# DL0WH_BiTuner_Ctrl_1V1.net
KiCad netlist of a schematic drawn in EAGLE
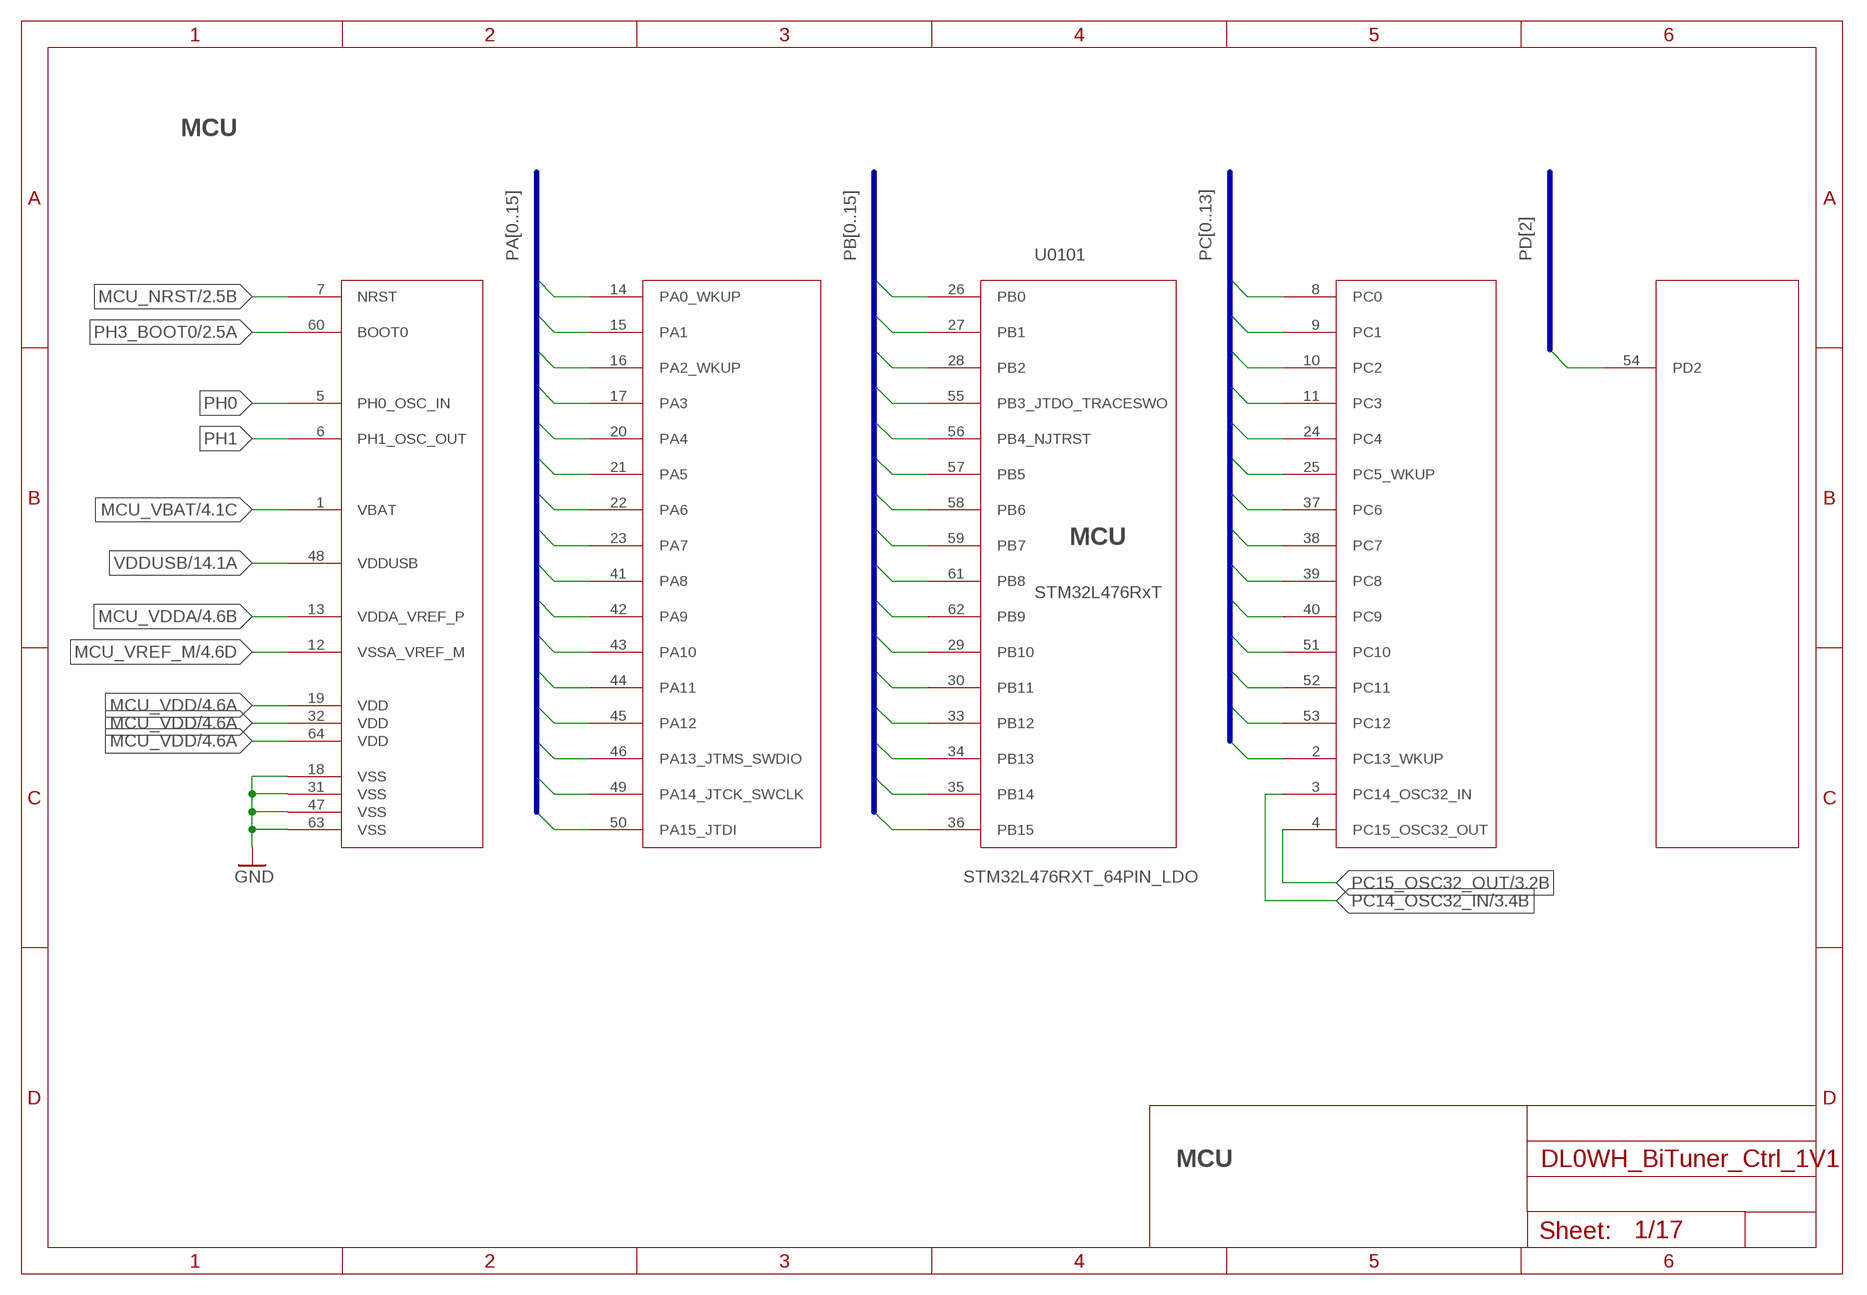
[diagram p0: schematic, sheet 1]
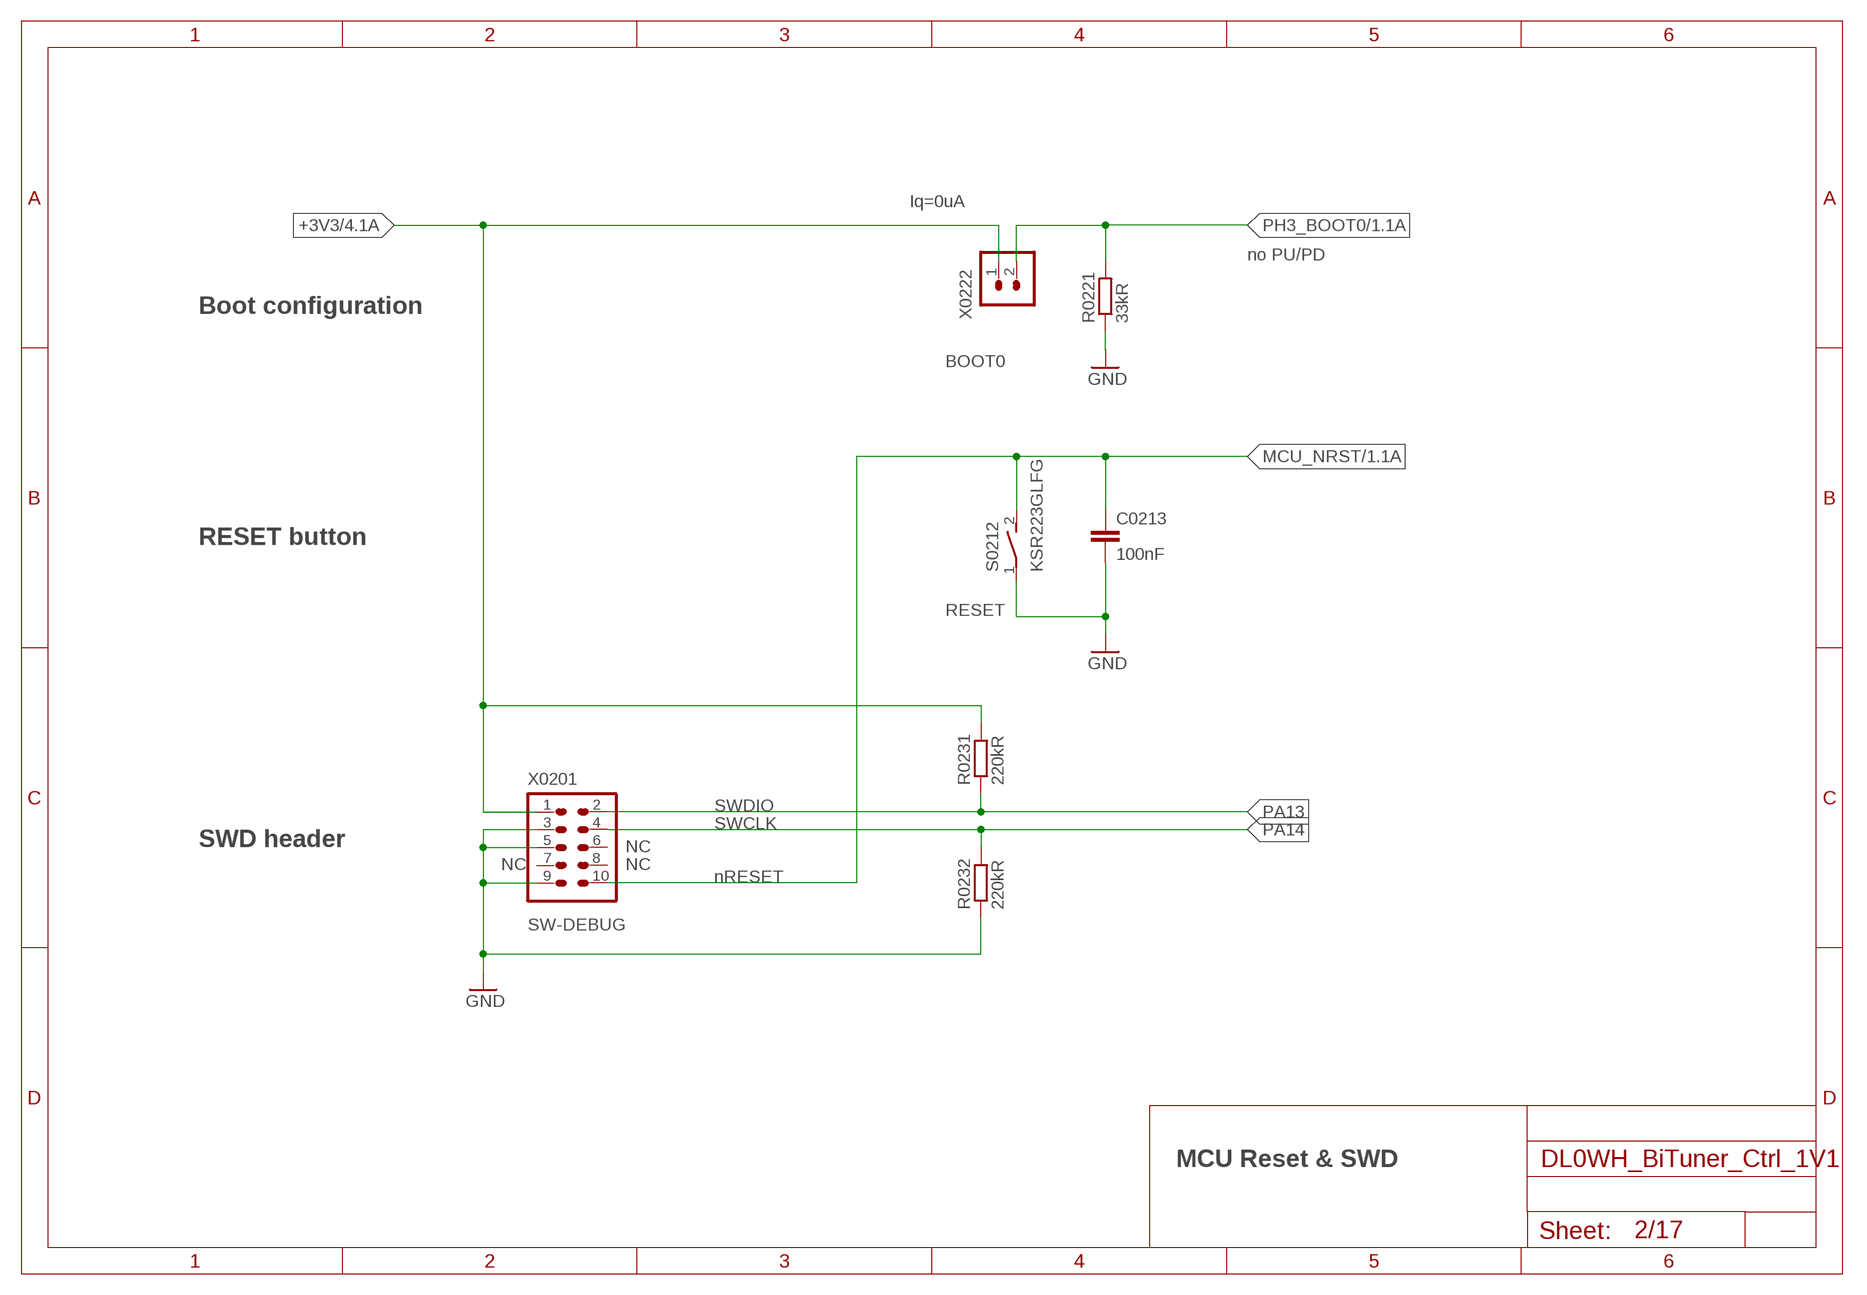
[diagram p1: schematic, sheet 2]
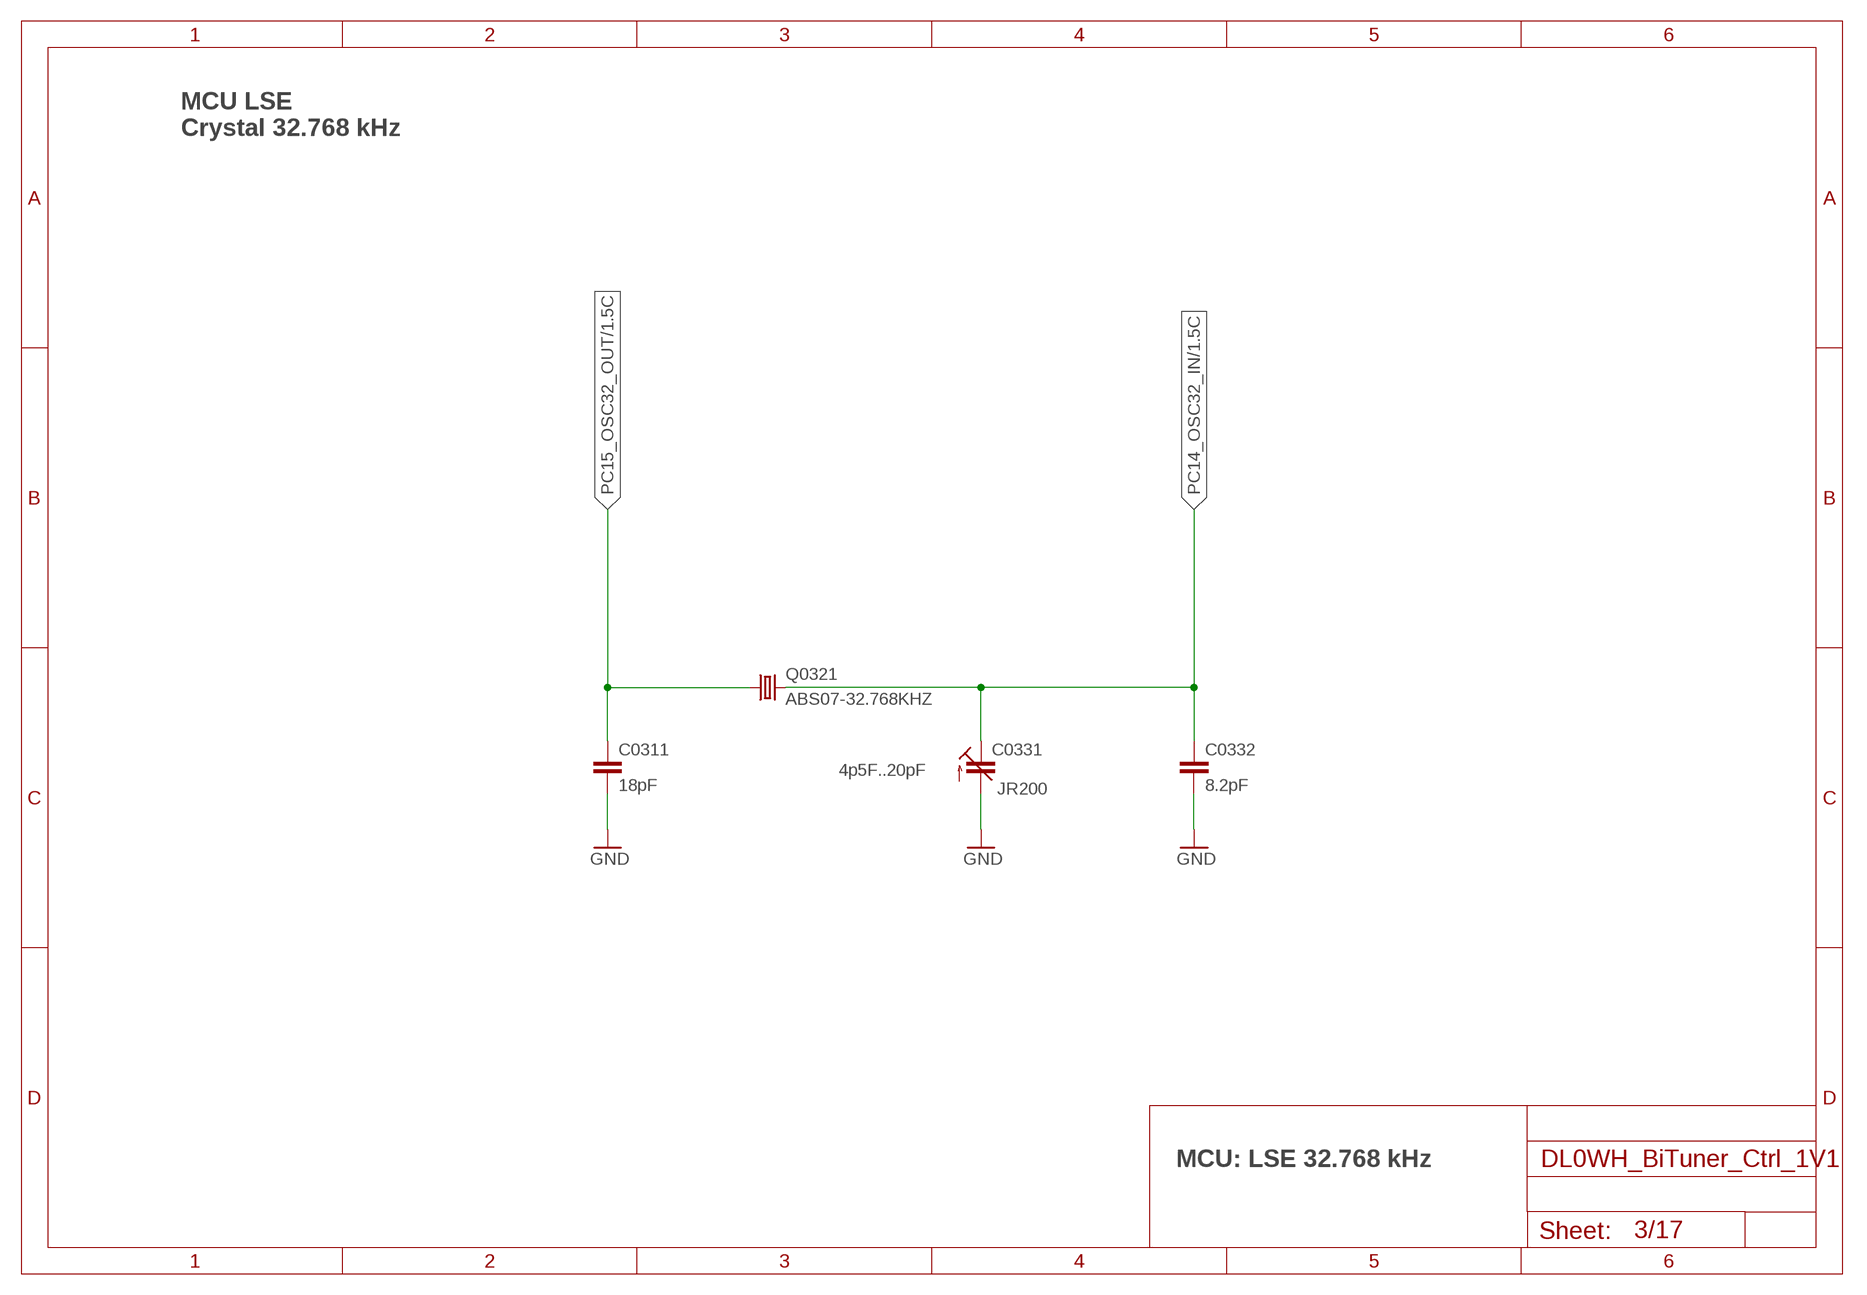
[diagram p2: schematic, sheet 3]
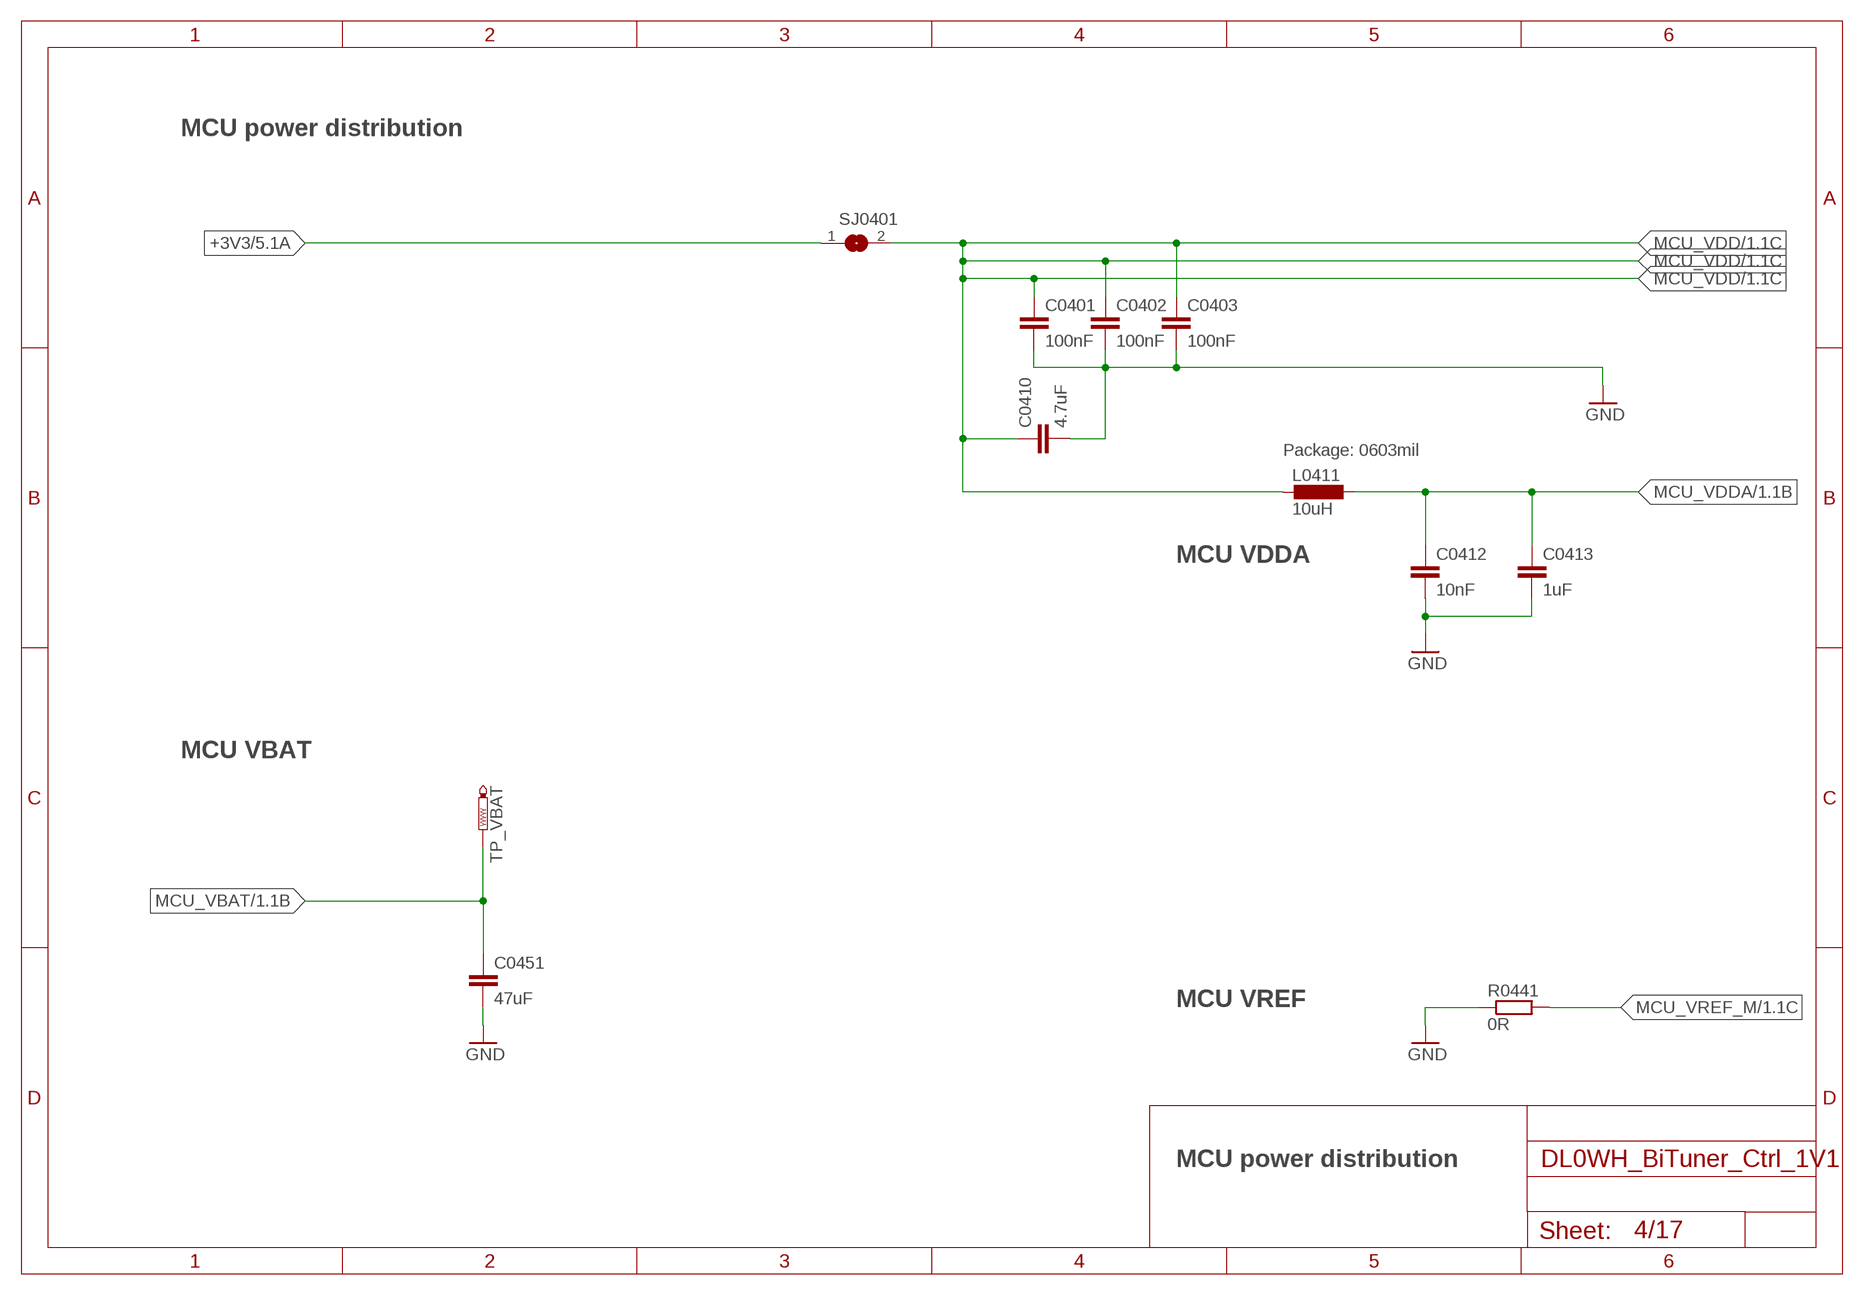
[diagram p3: schematic, sheet 4]
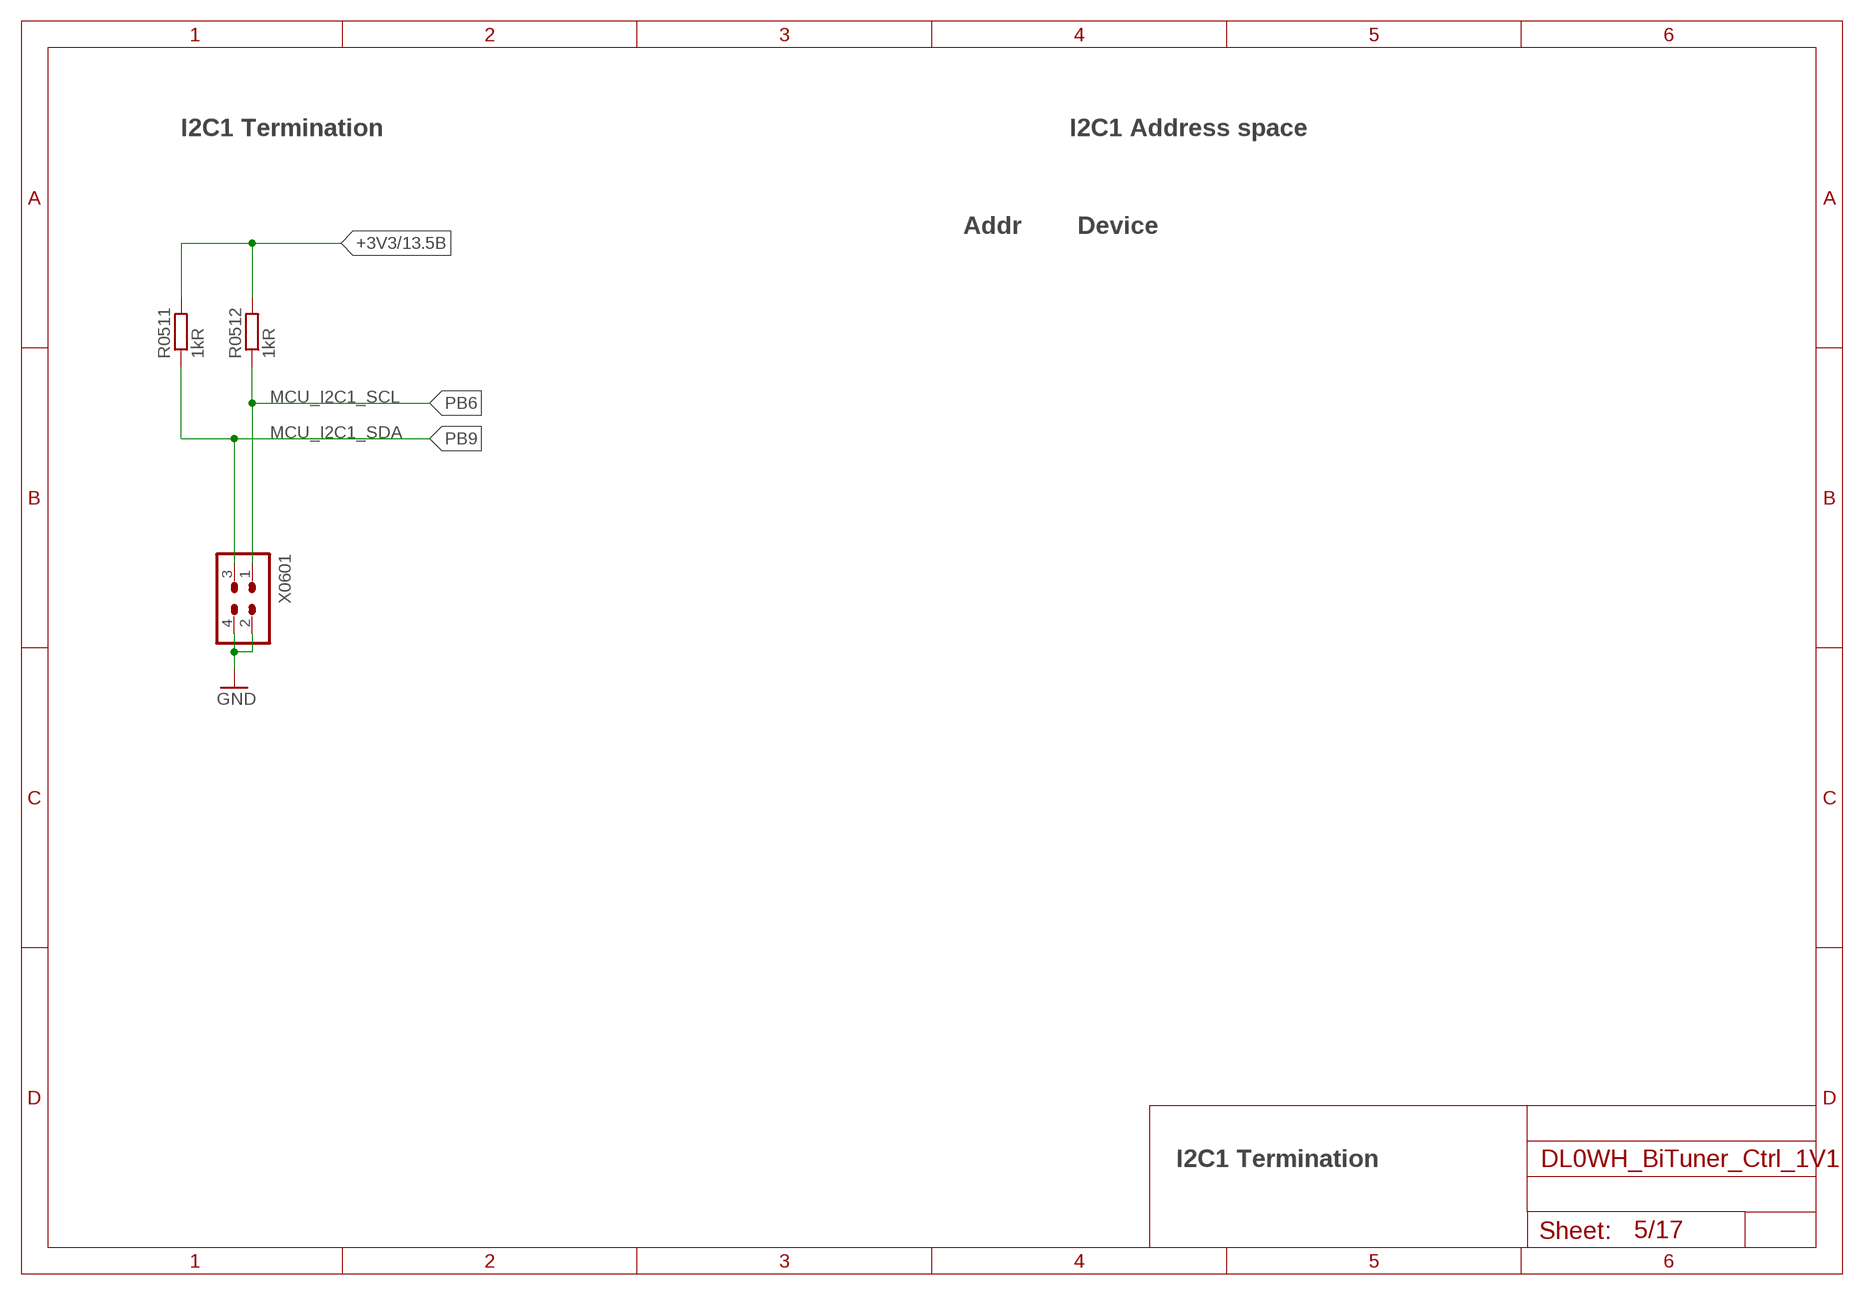
[diagram p4: schematic, sheet 5]
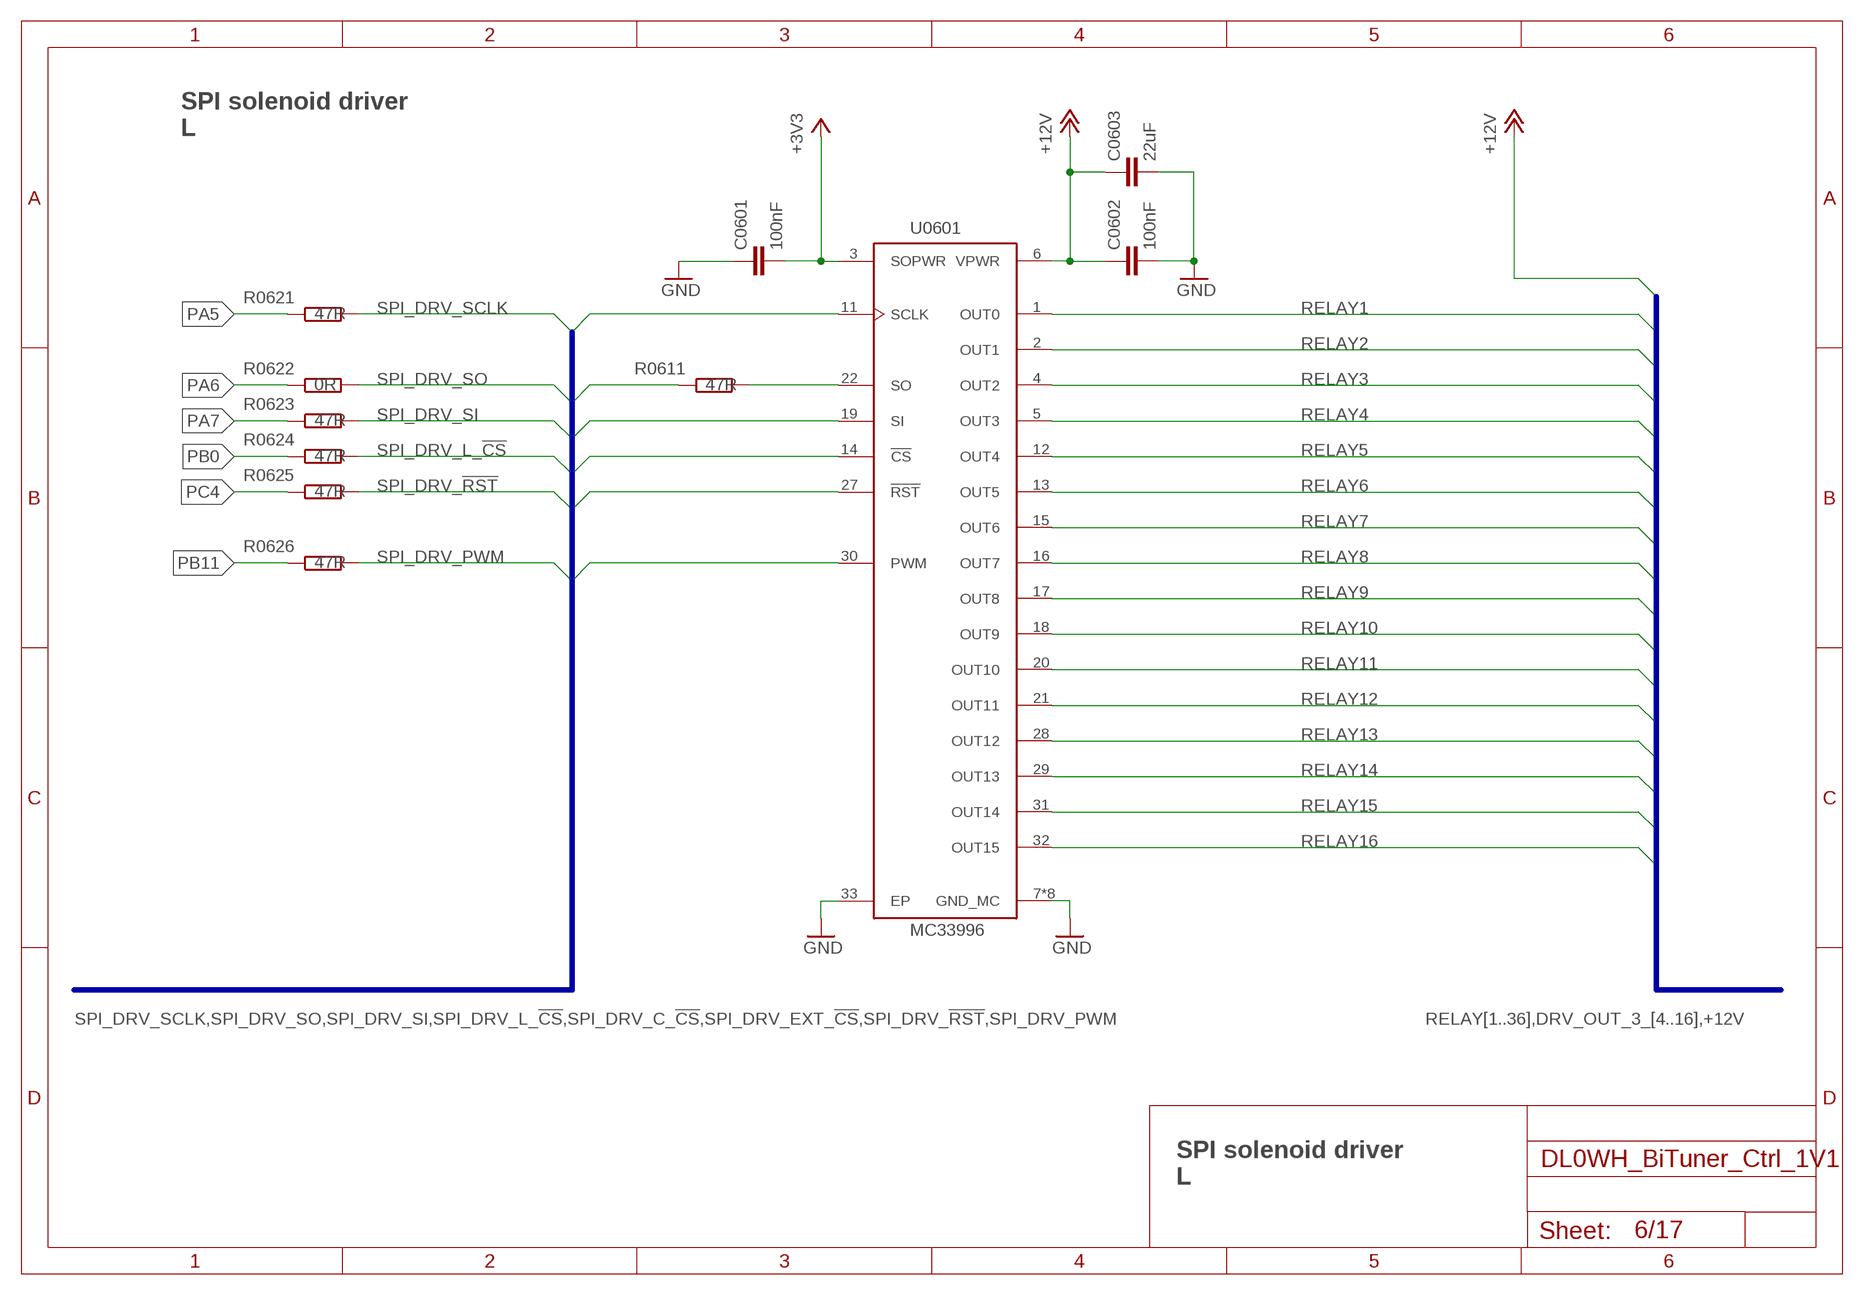
[diagram p5: schematic, sheet 6]
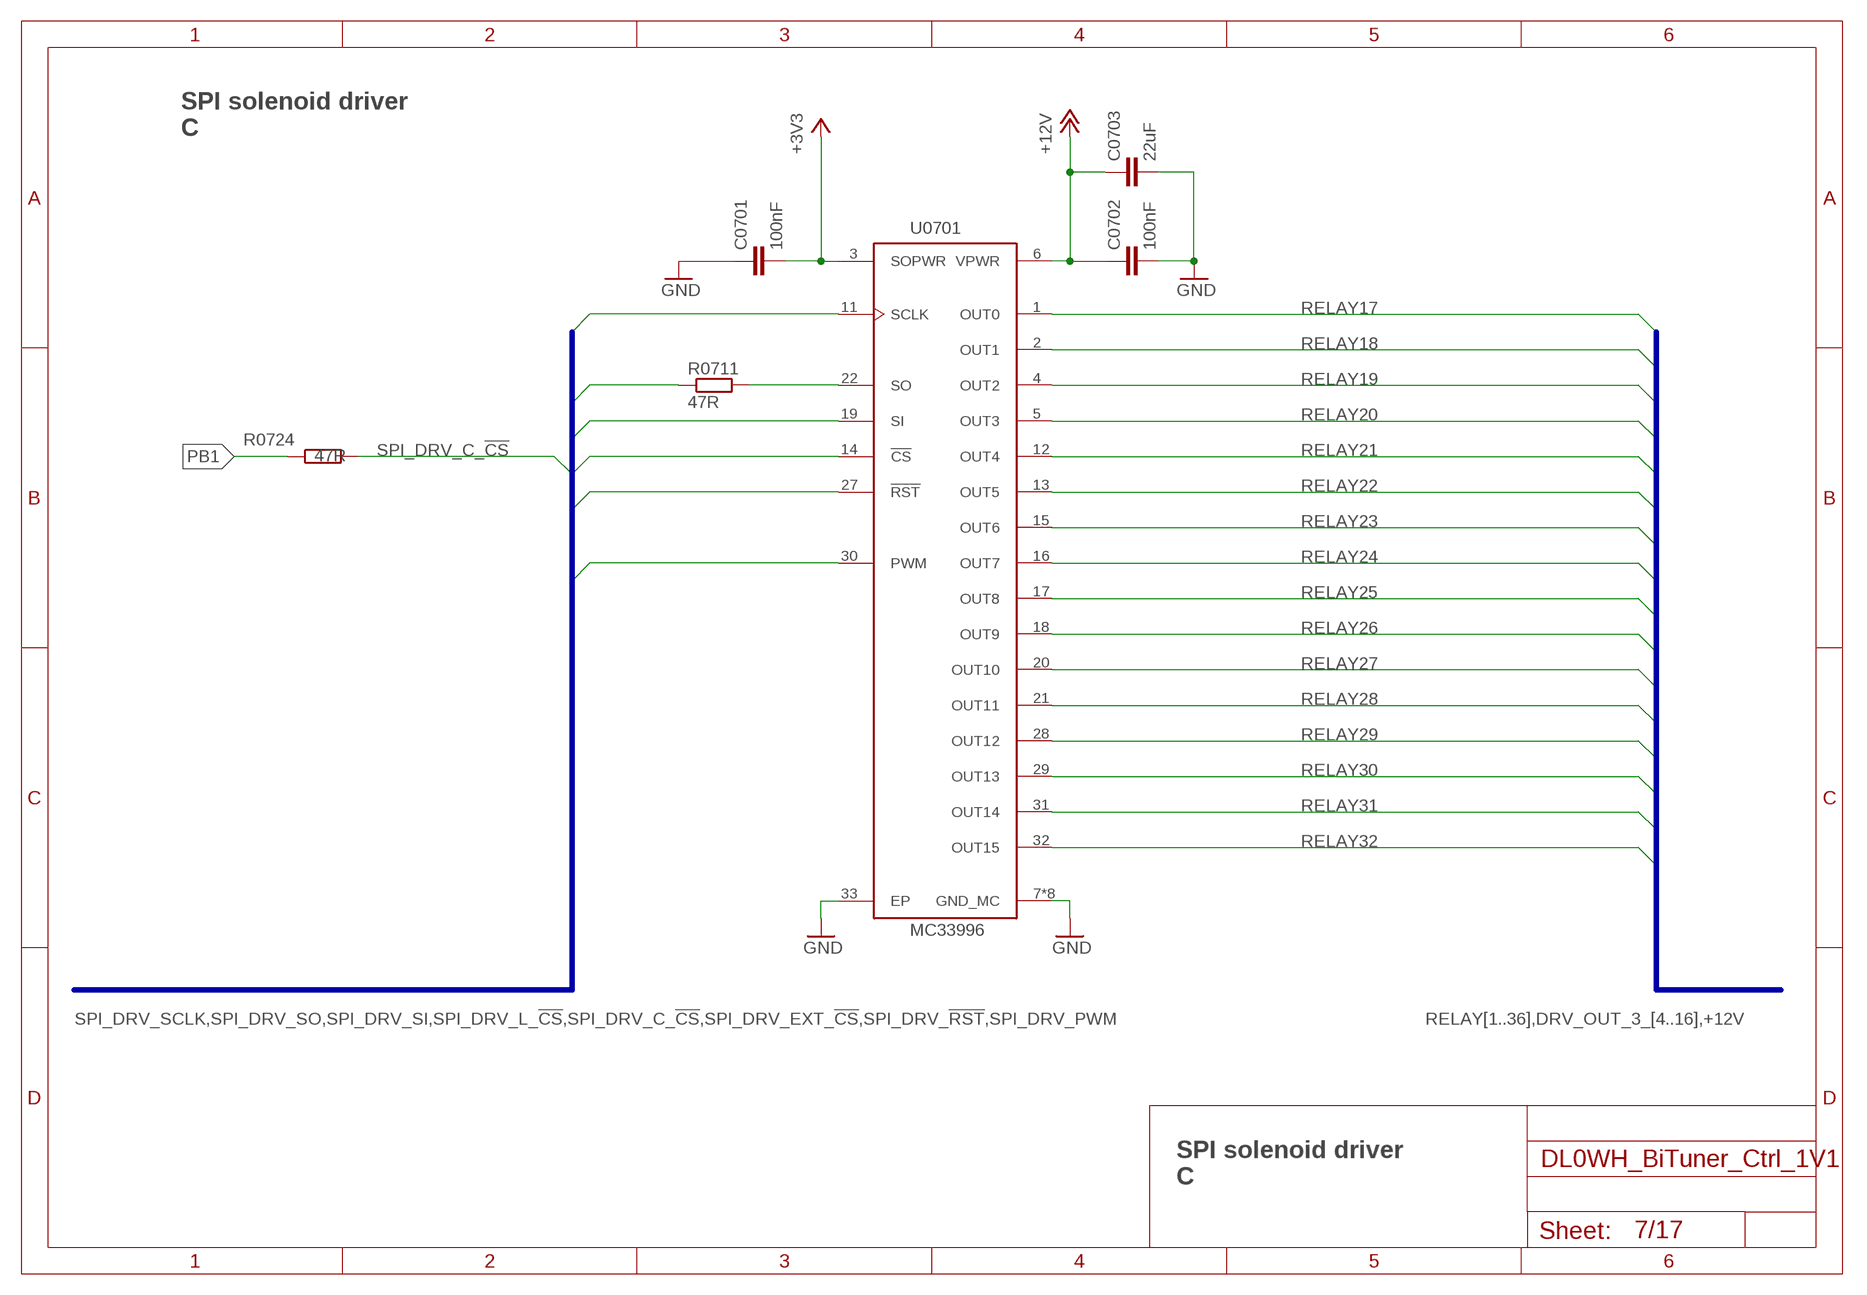
[diagram p6: schematic, sheet 7]
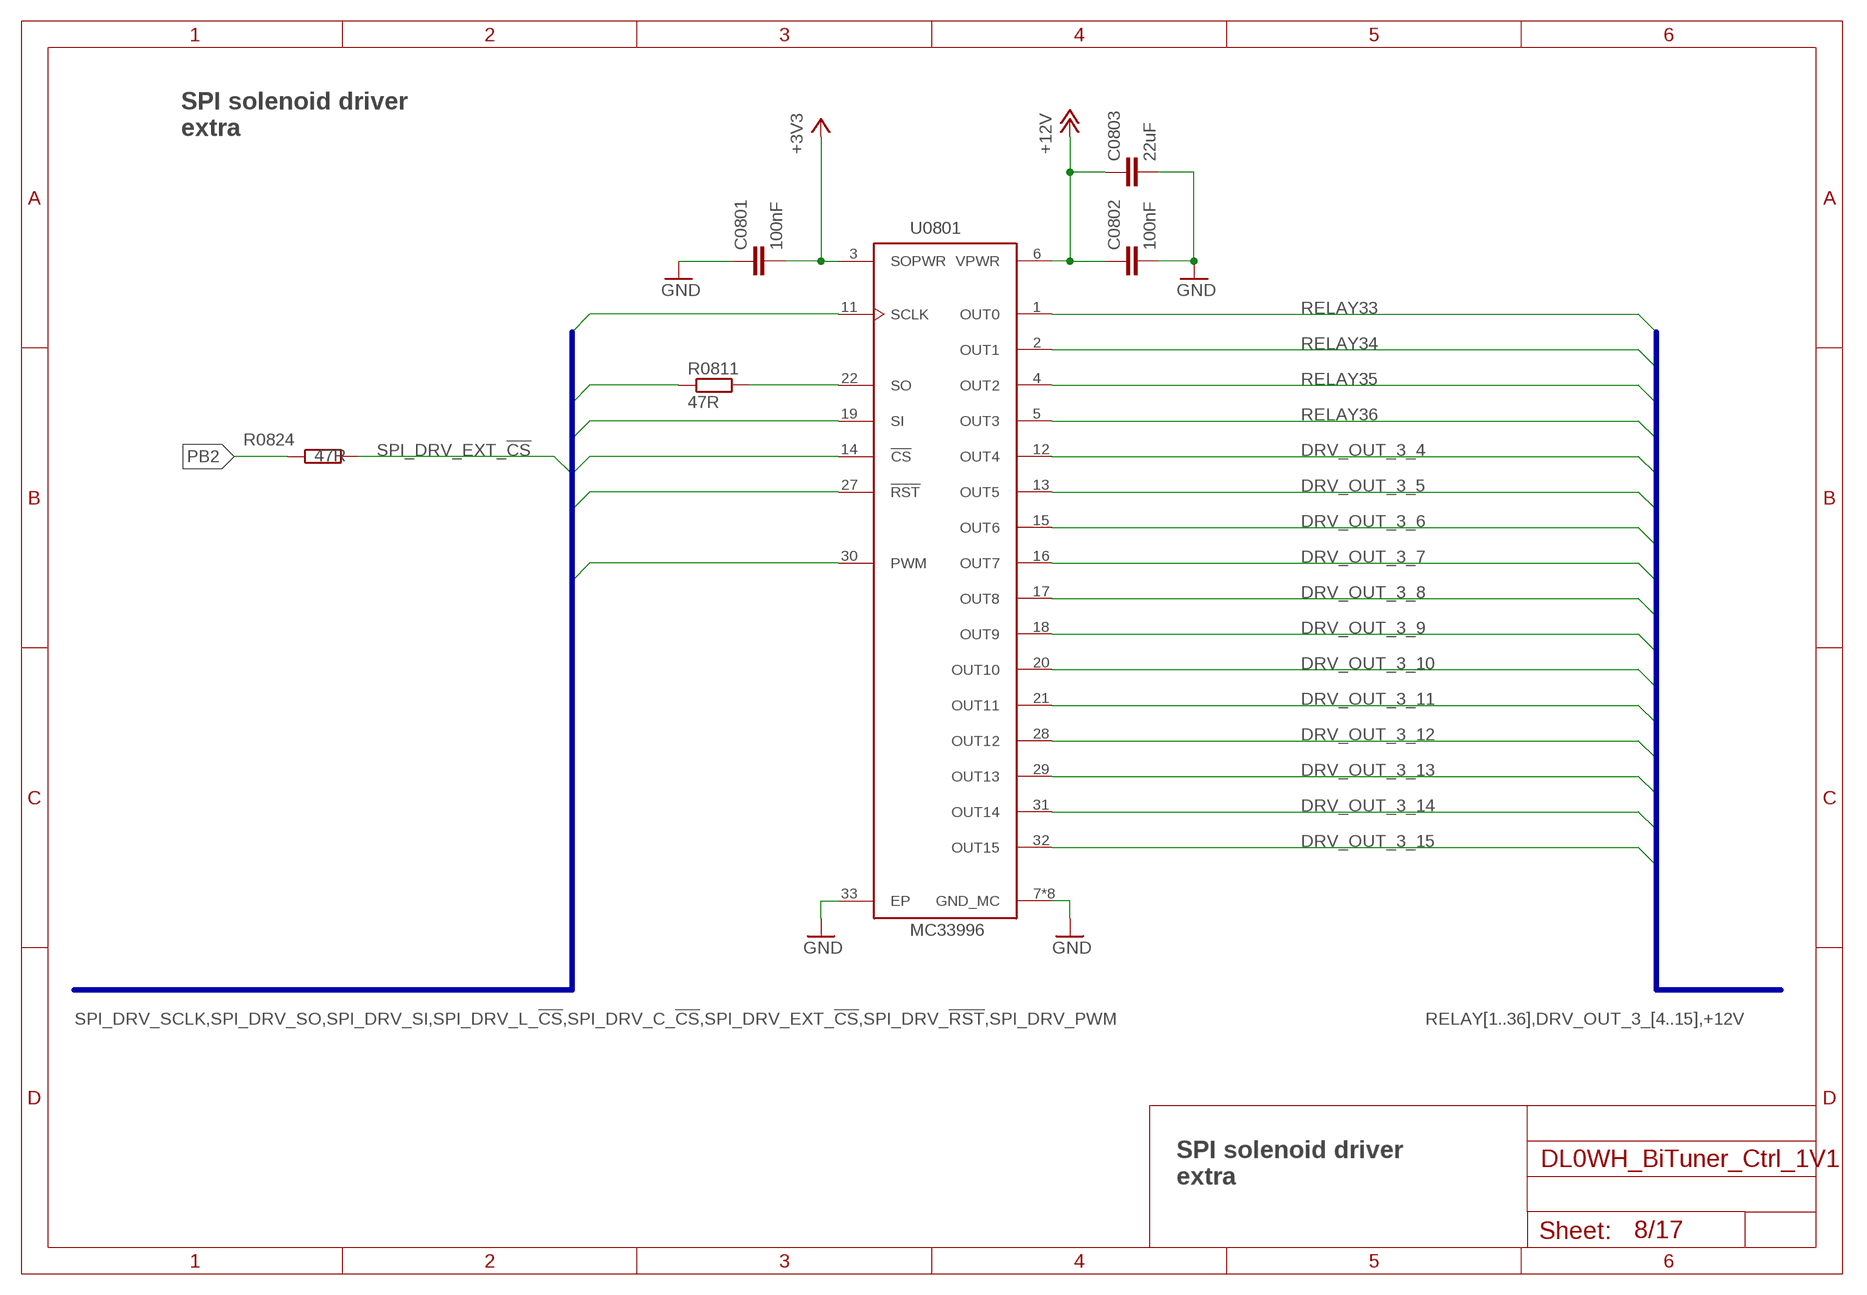
[diagram p7: schematic, sheet 8]
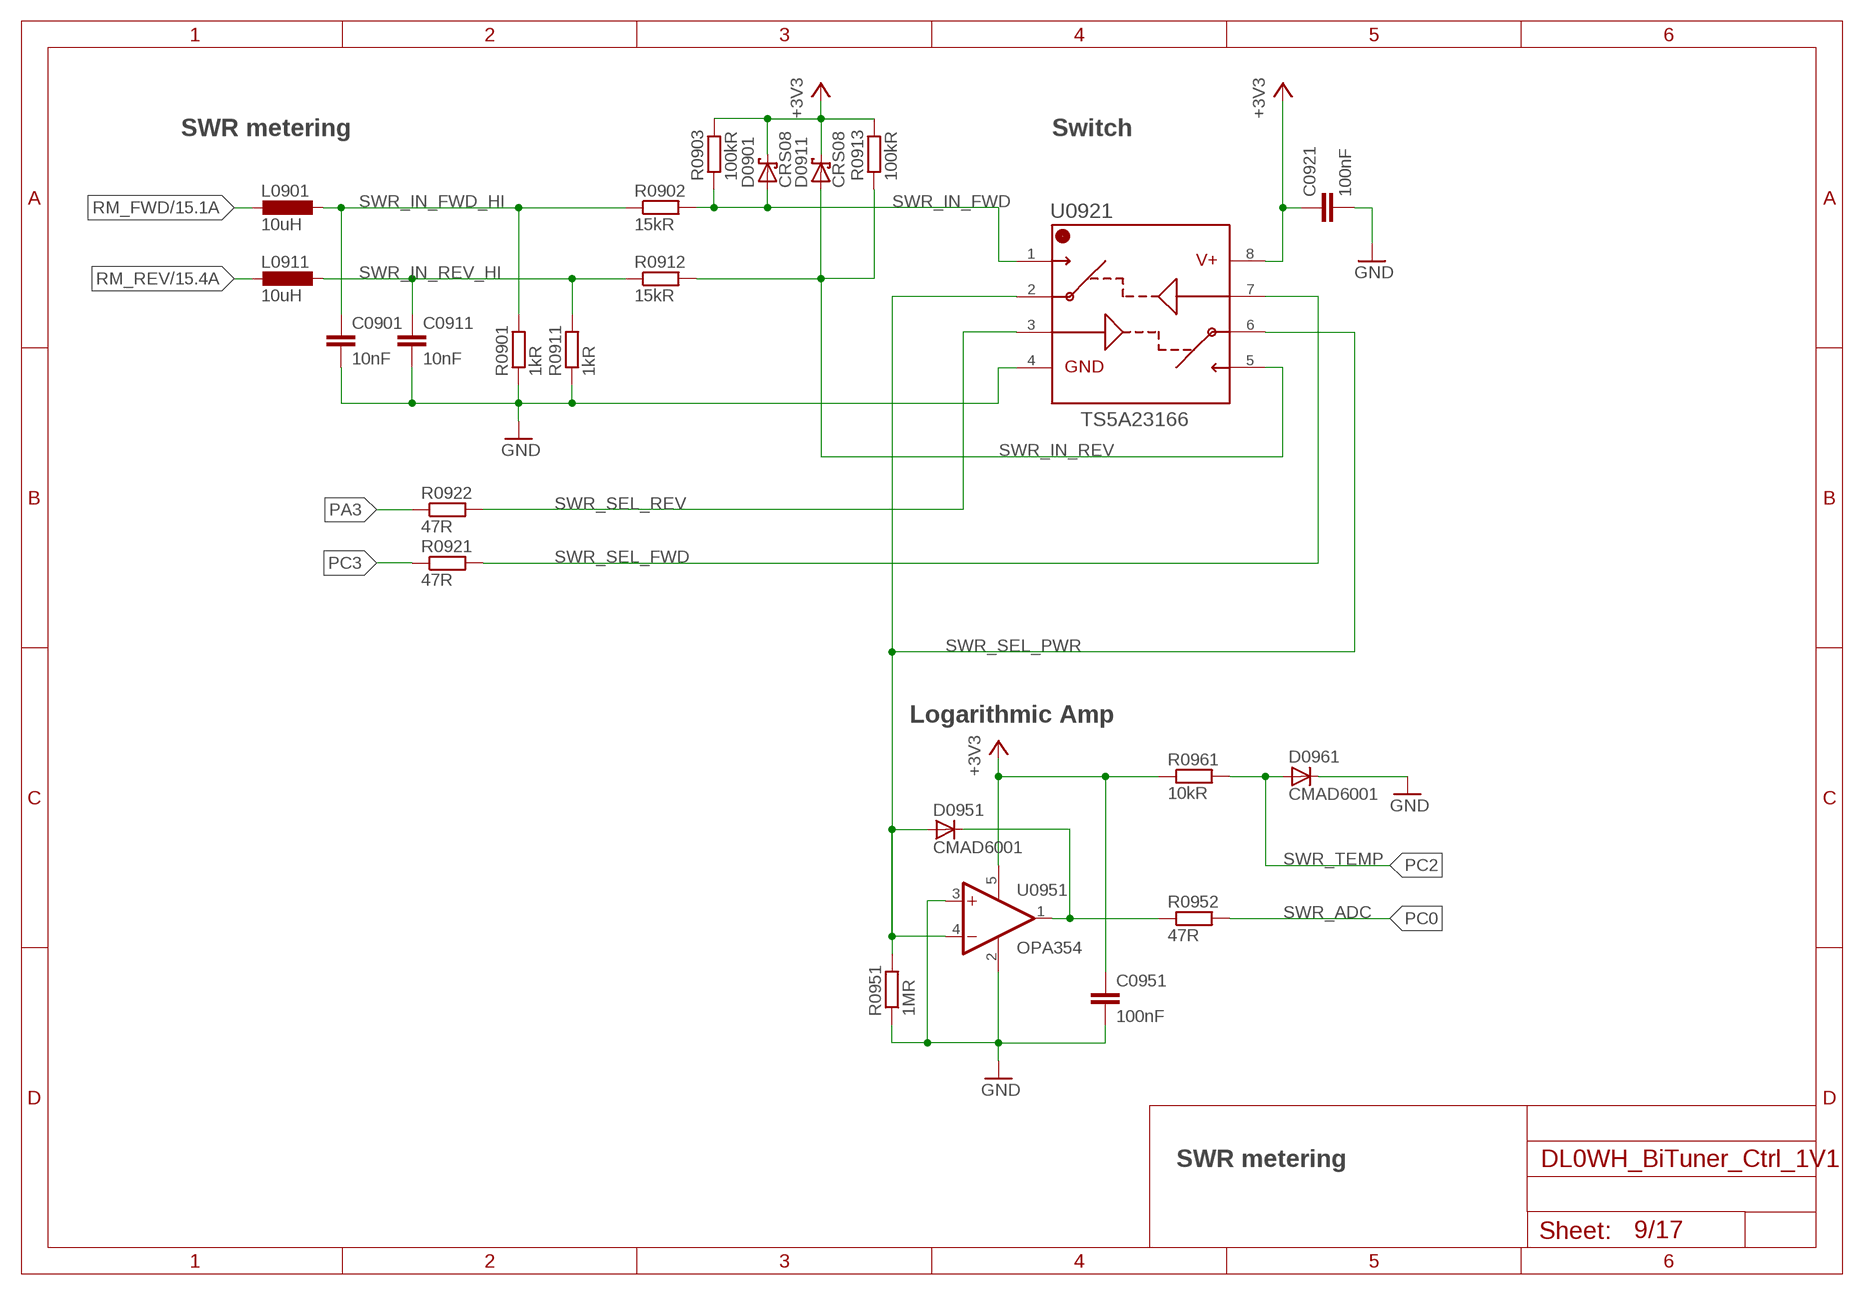
[diagram p8: schematic, sheet 9]
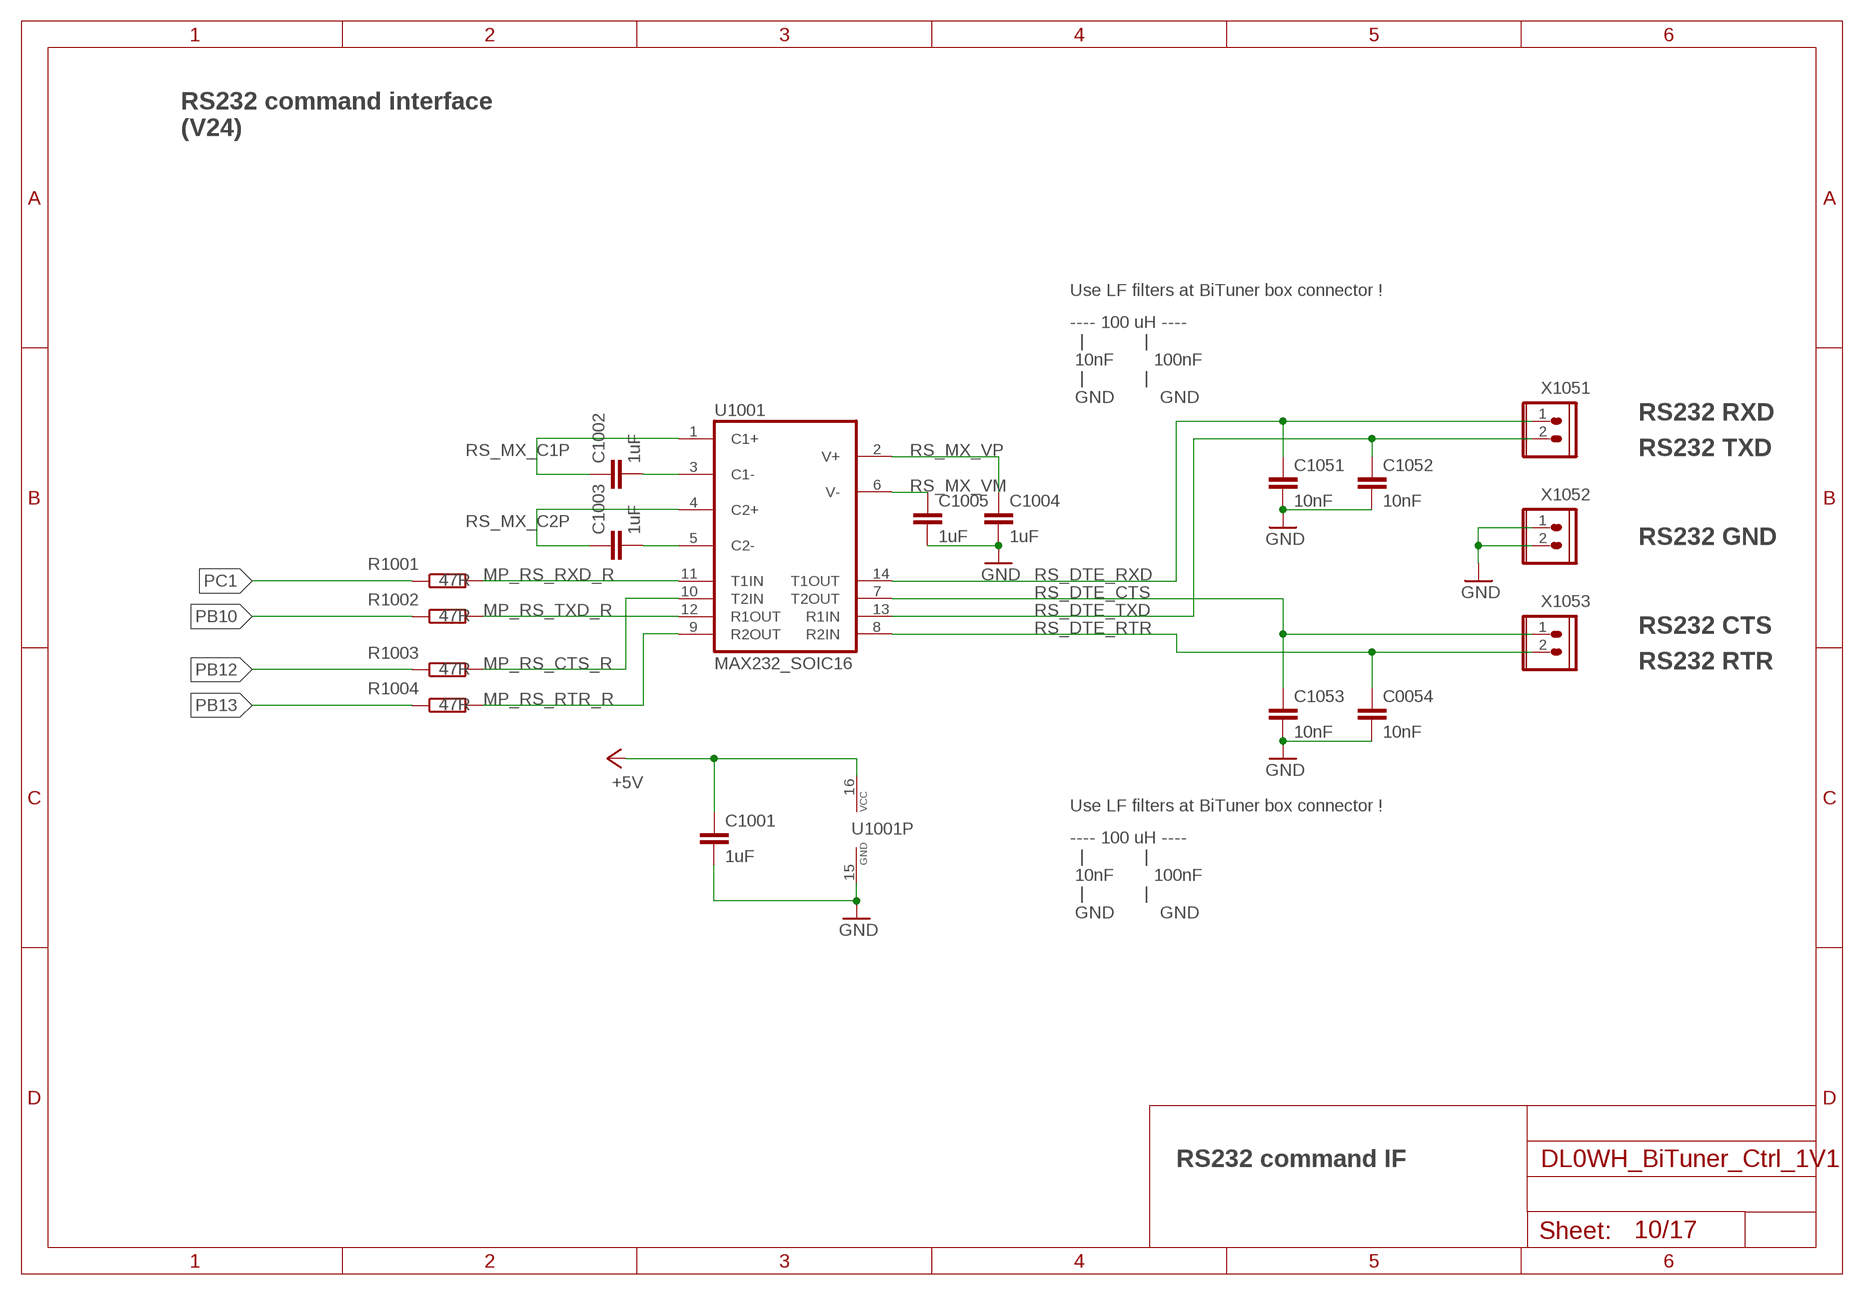
[diagram p9: schematic, sheet 10]
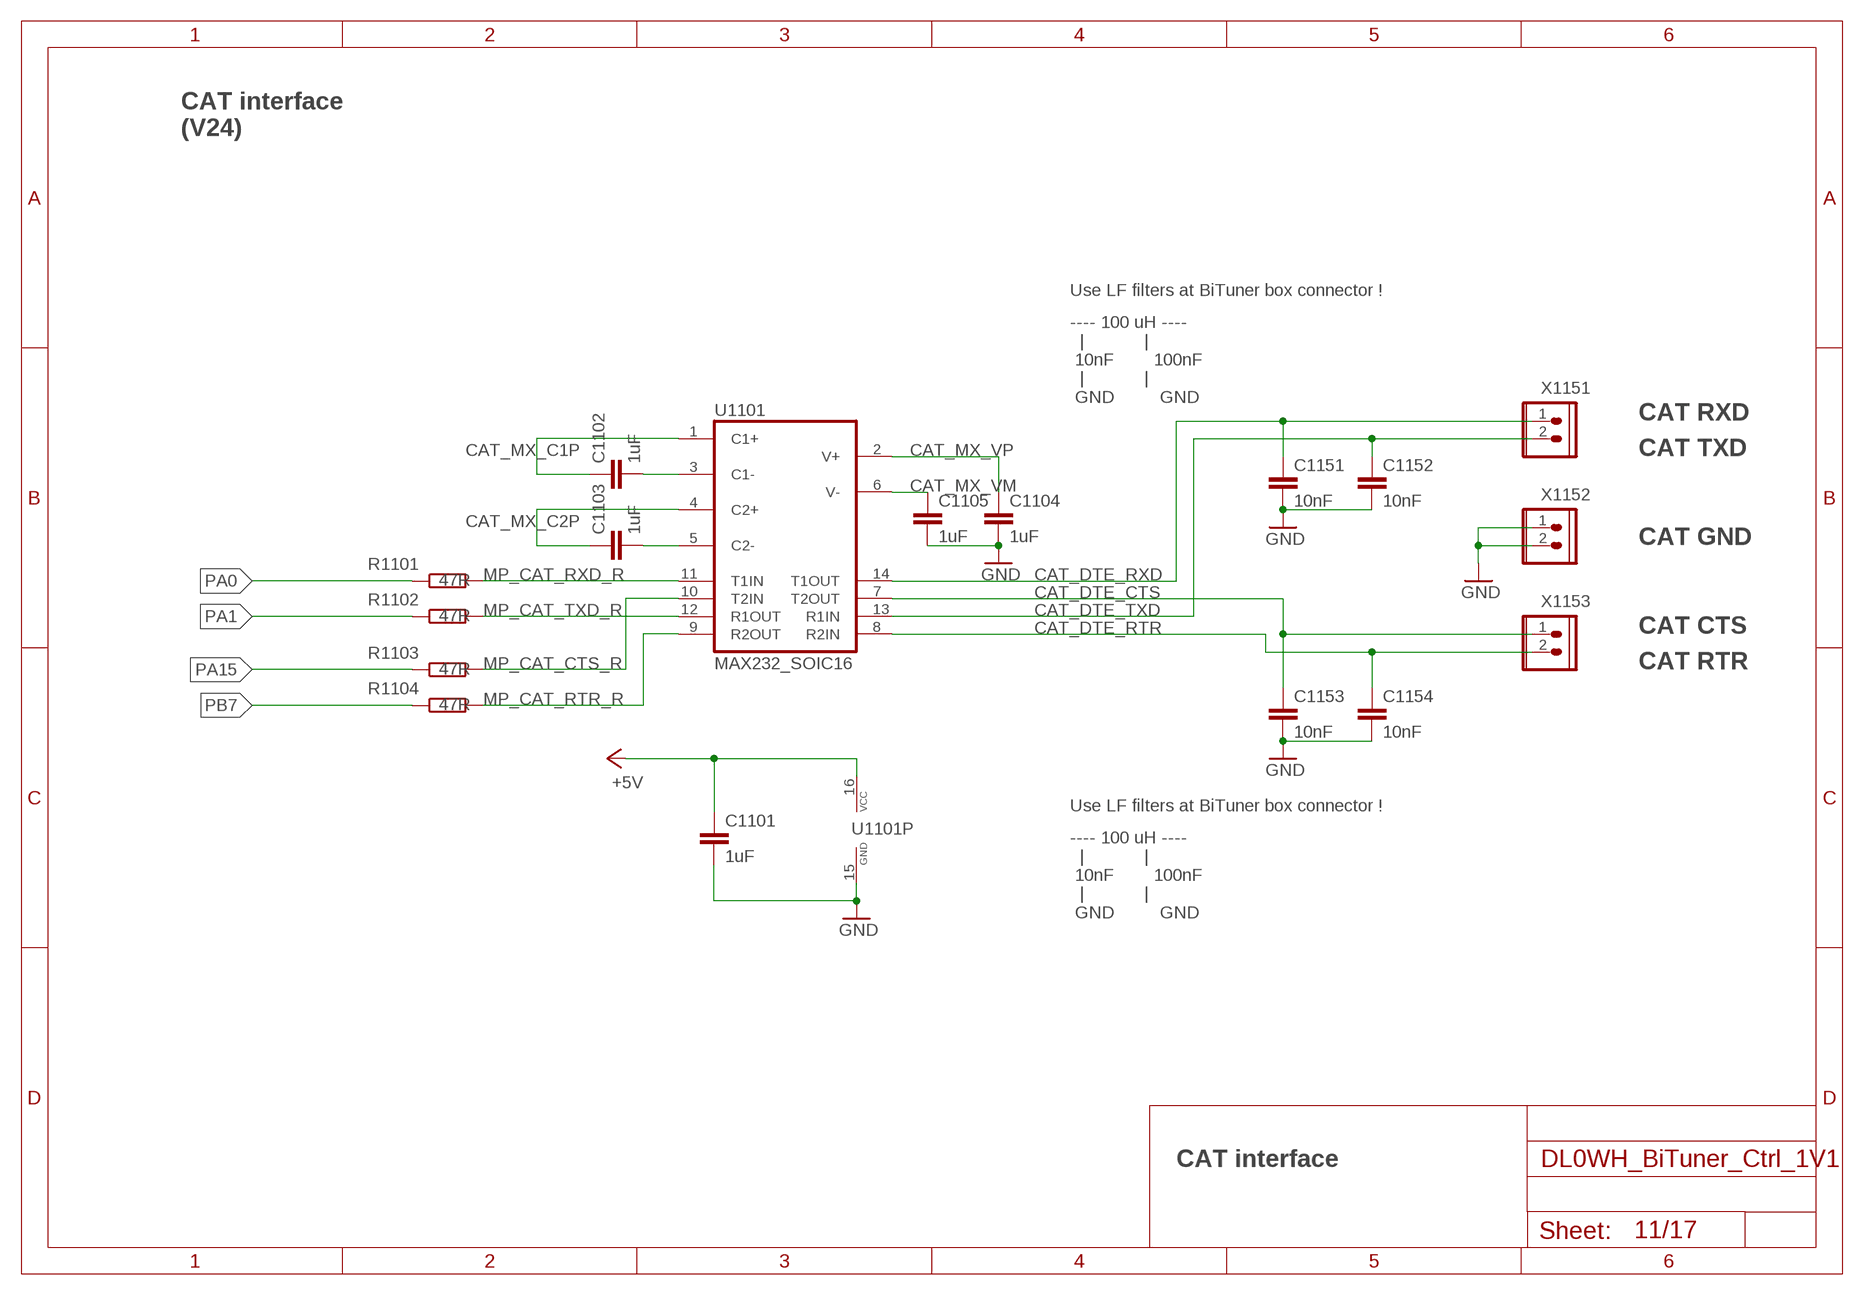
[diagram p10: schematic, sheet 11]
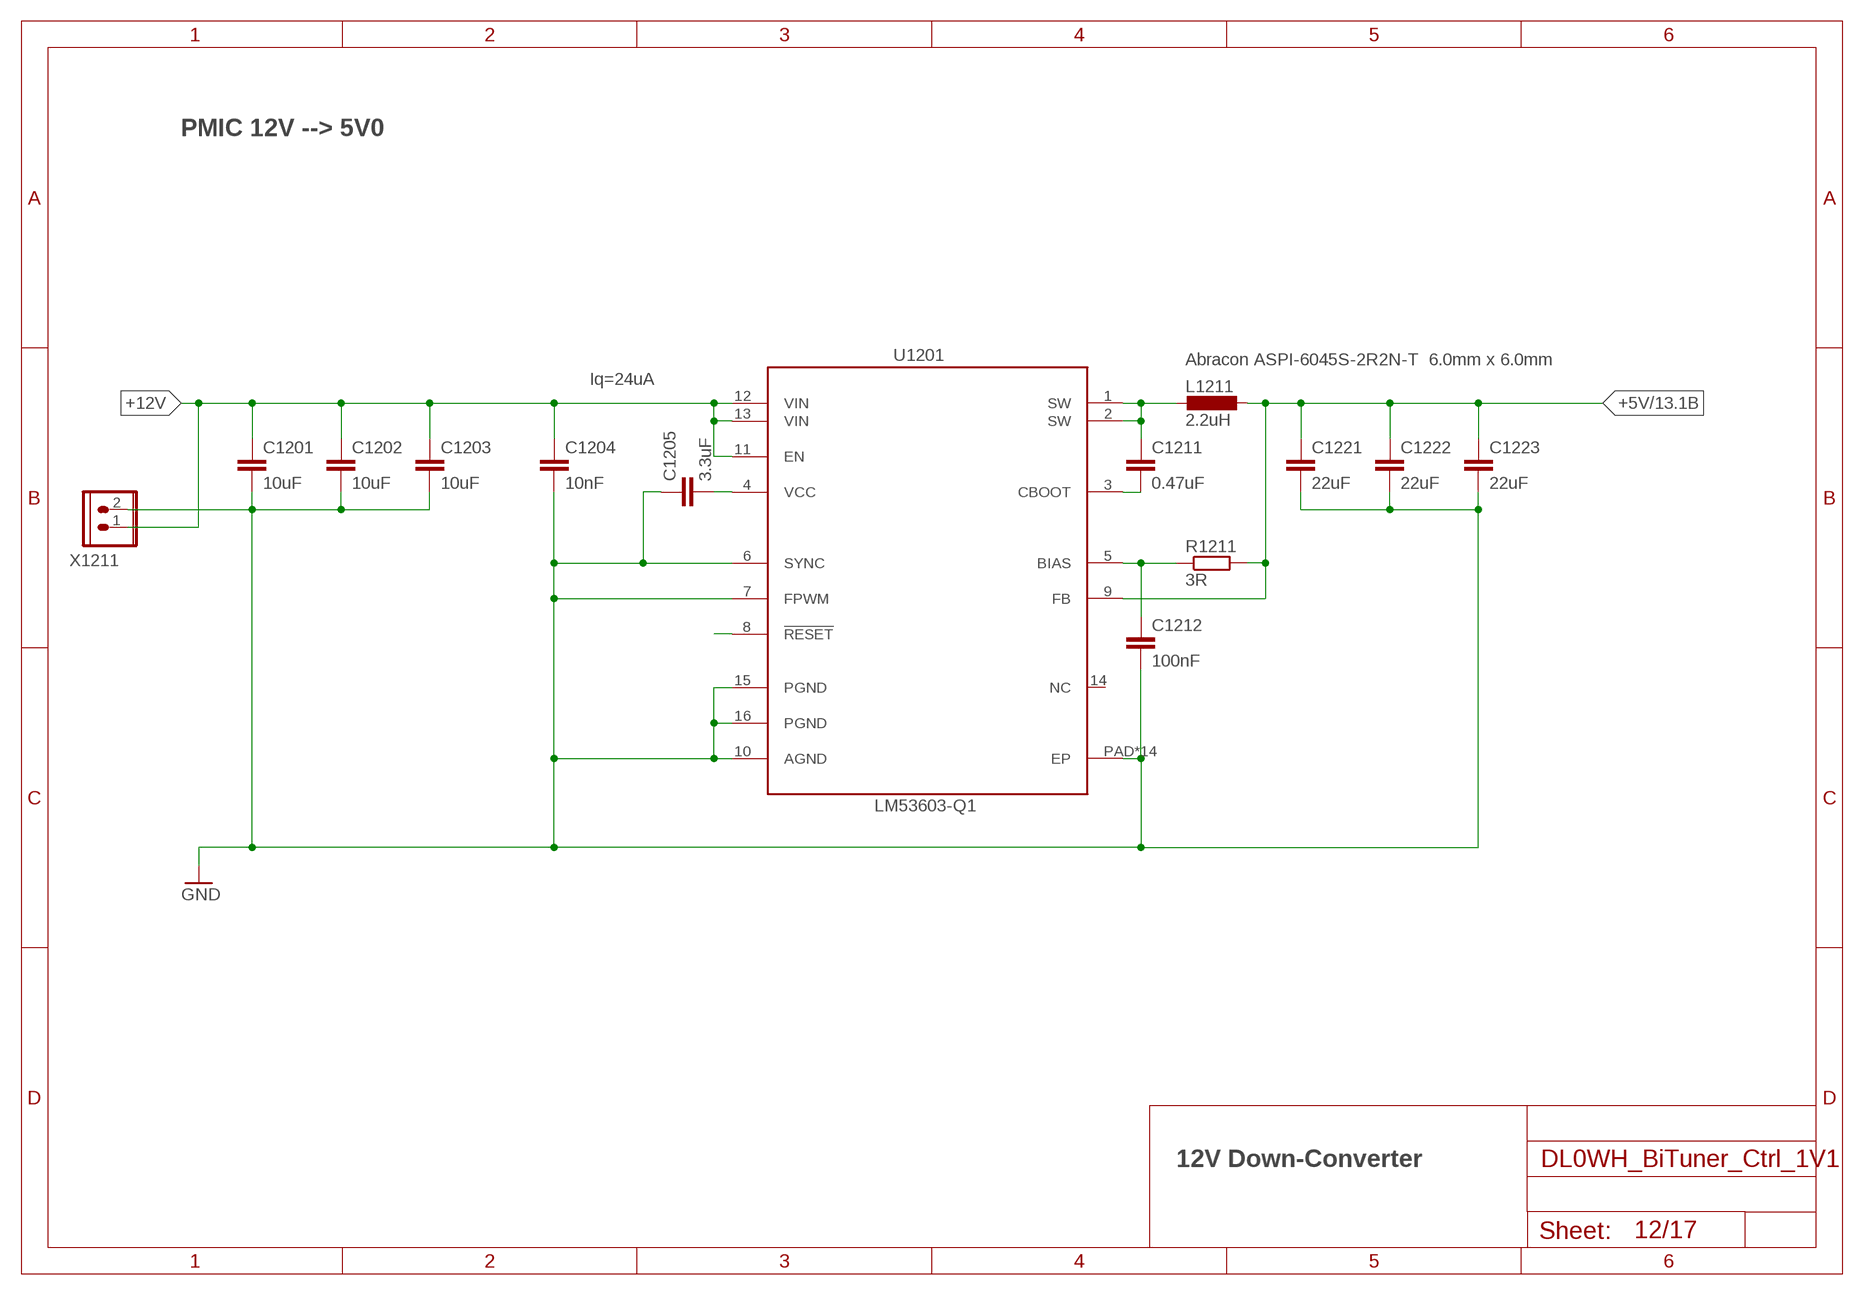
[diagram p11: schematic, sheet 12]
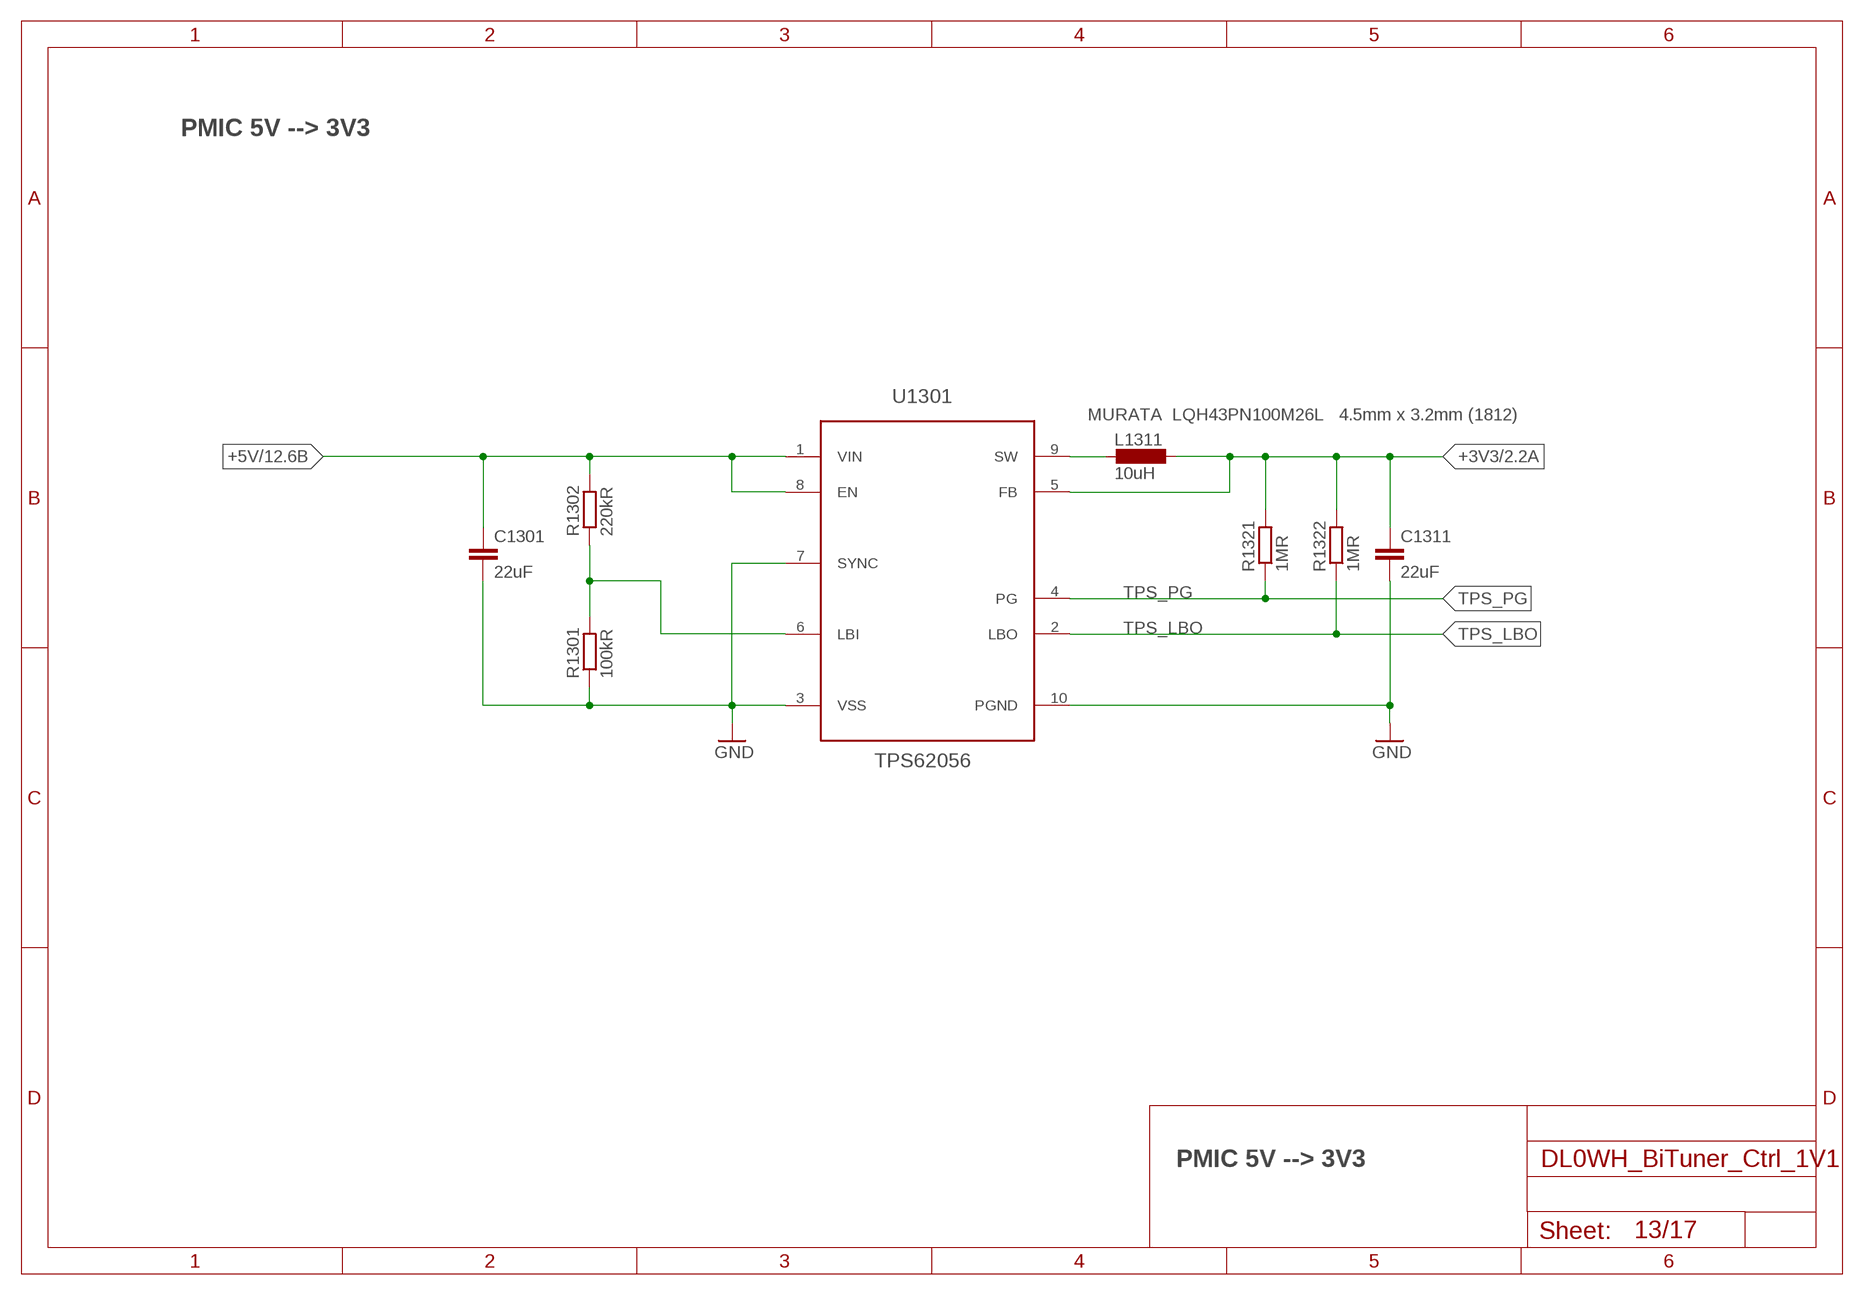
[diagram p12: schematic, sheet 13]
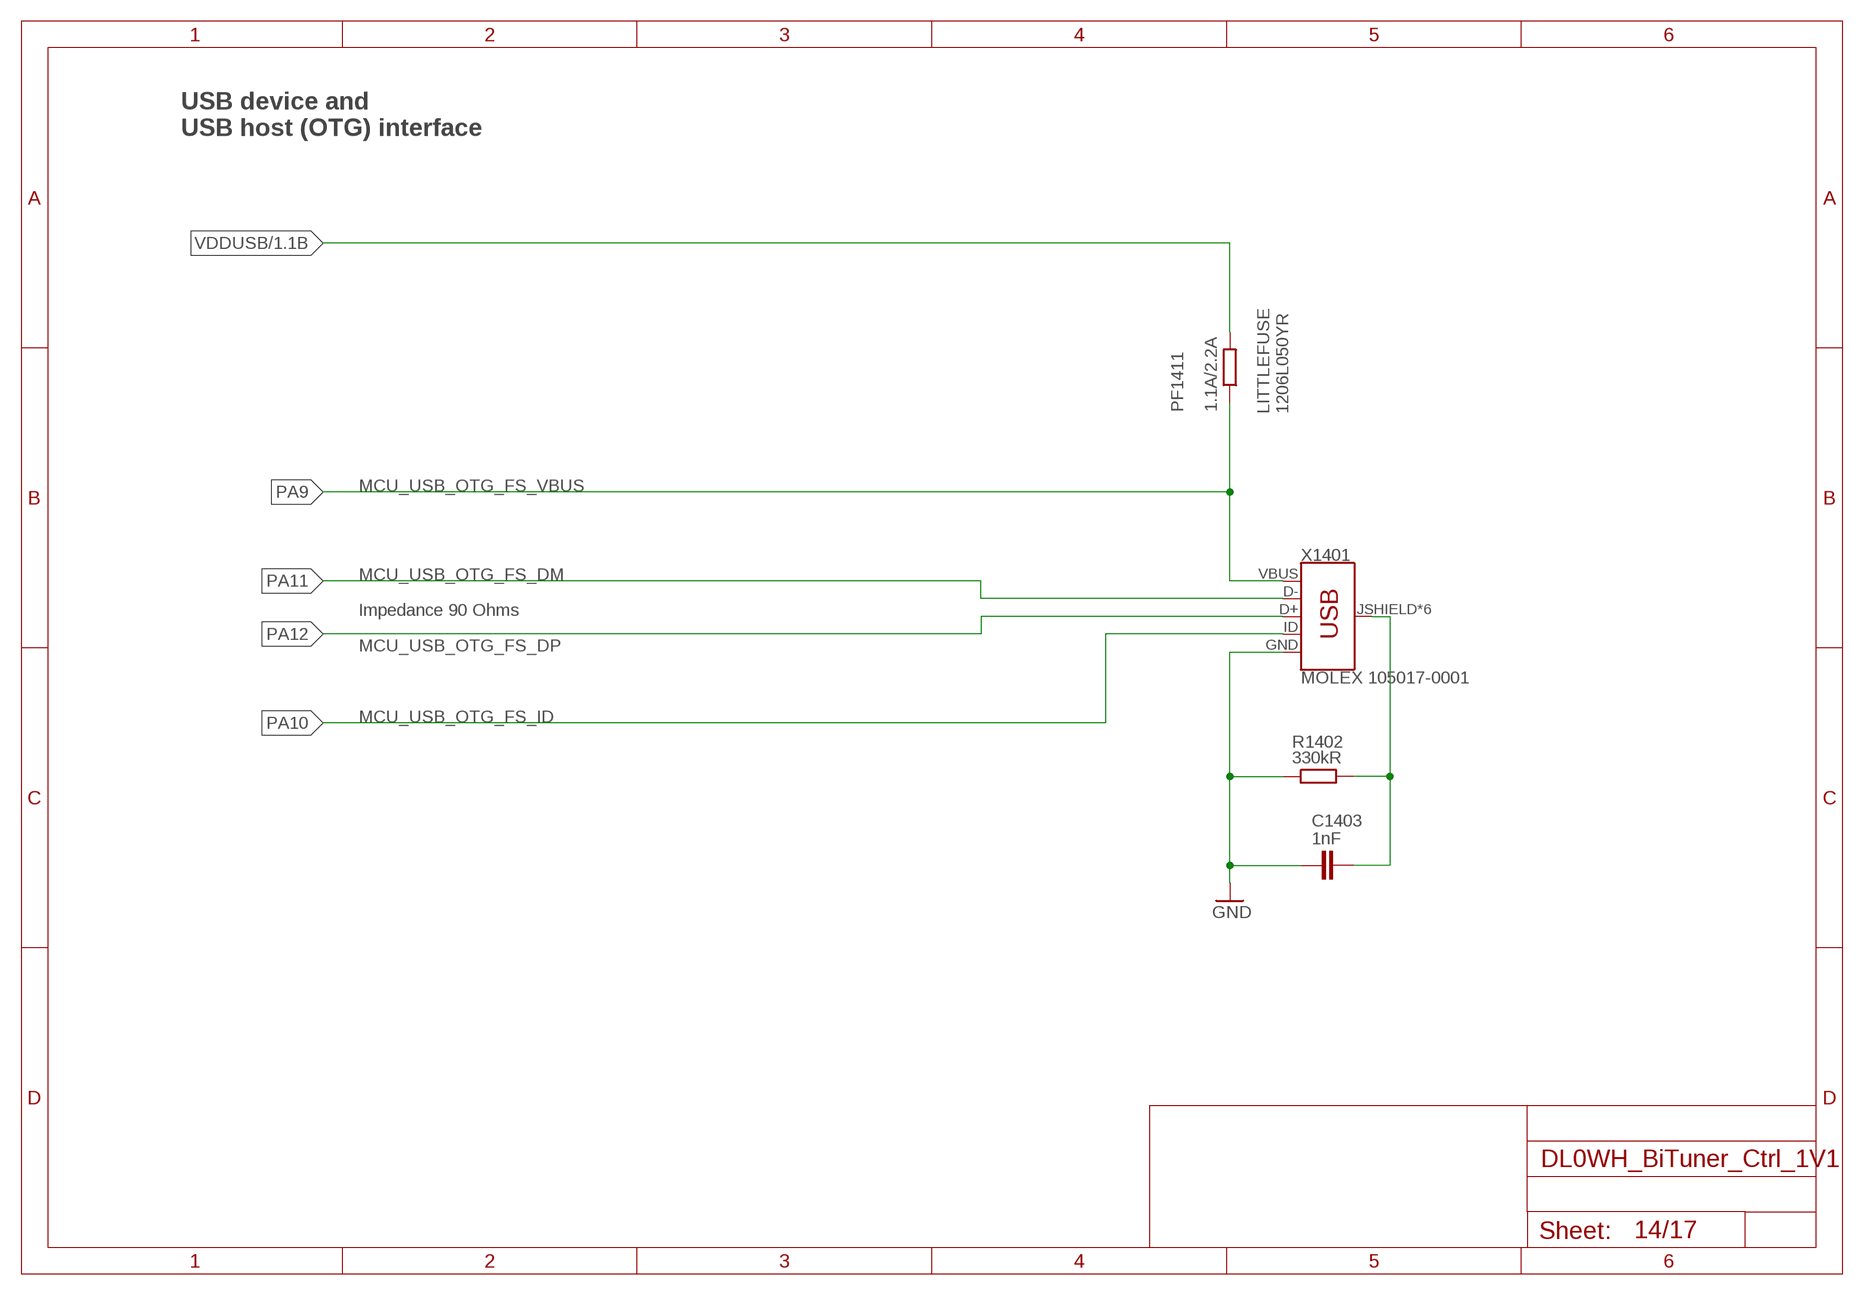
[diagram p13: schematic, sheet 14]
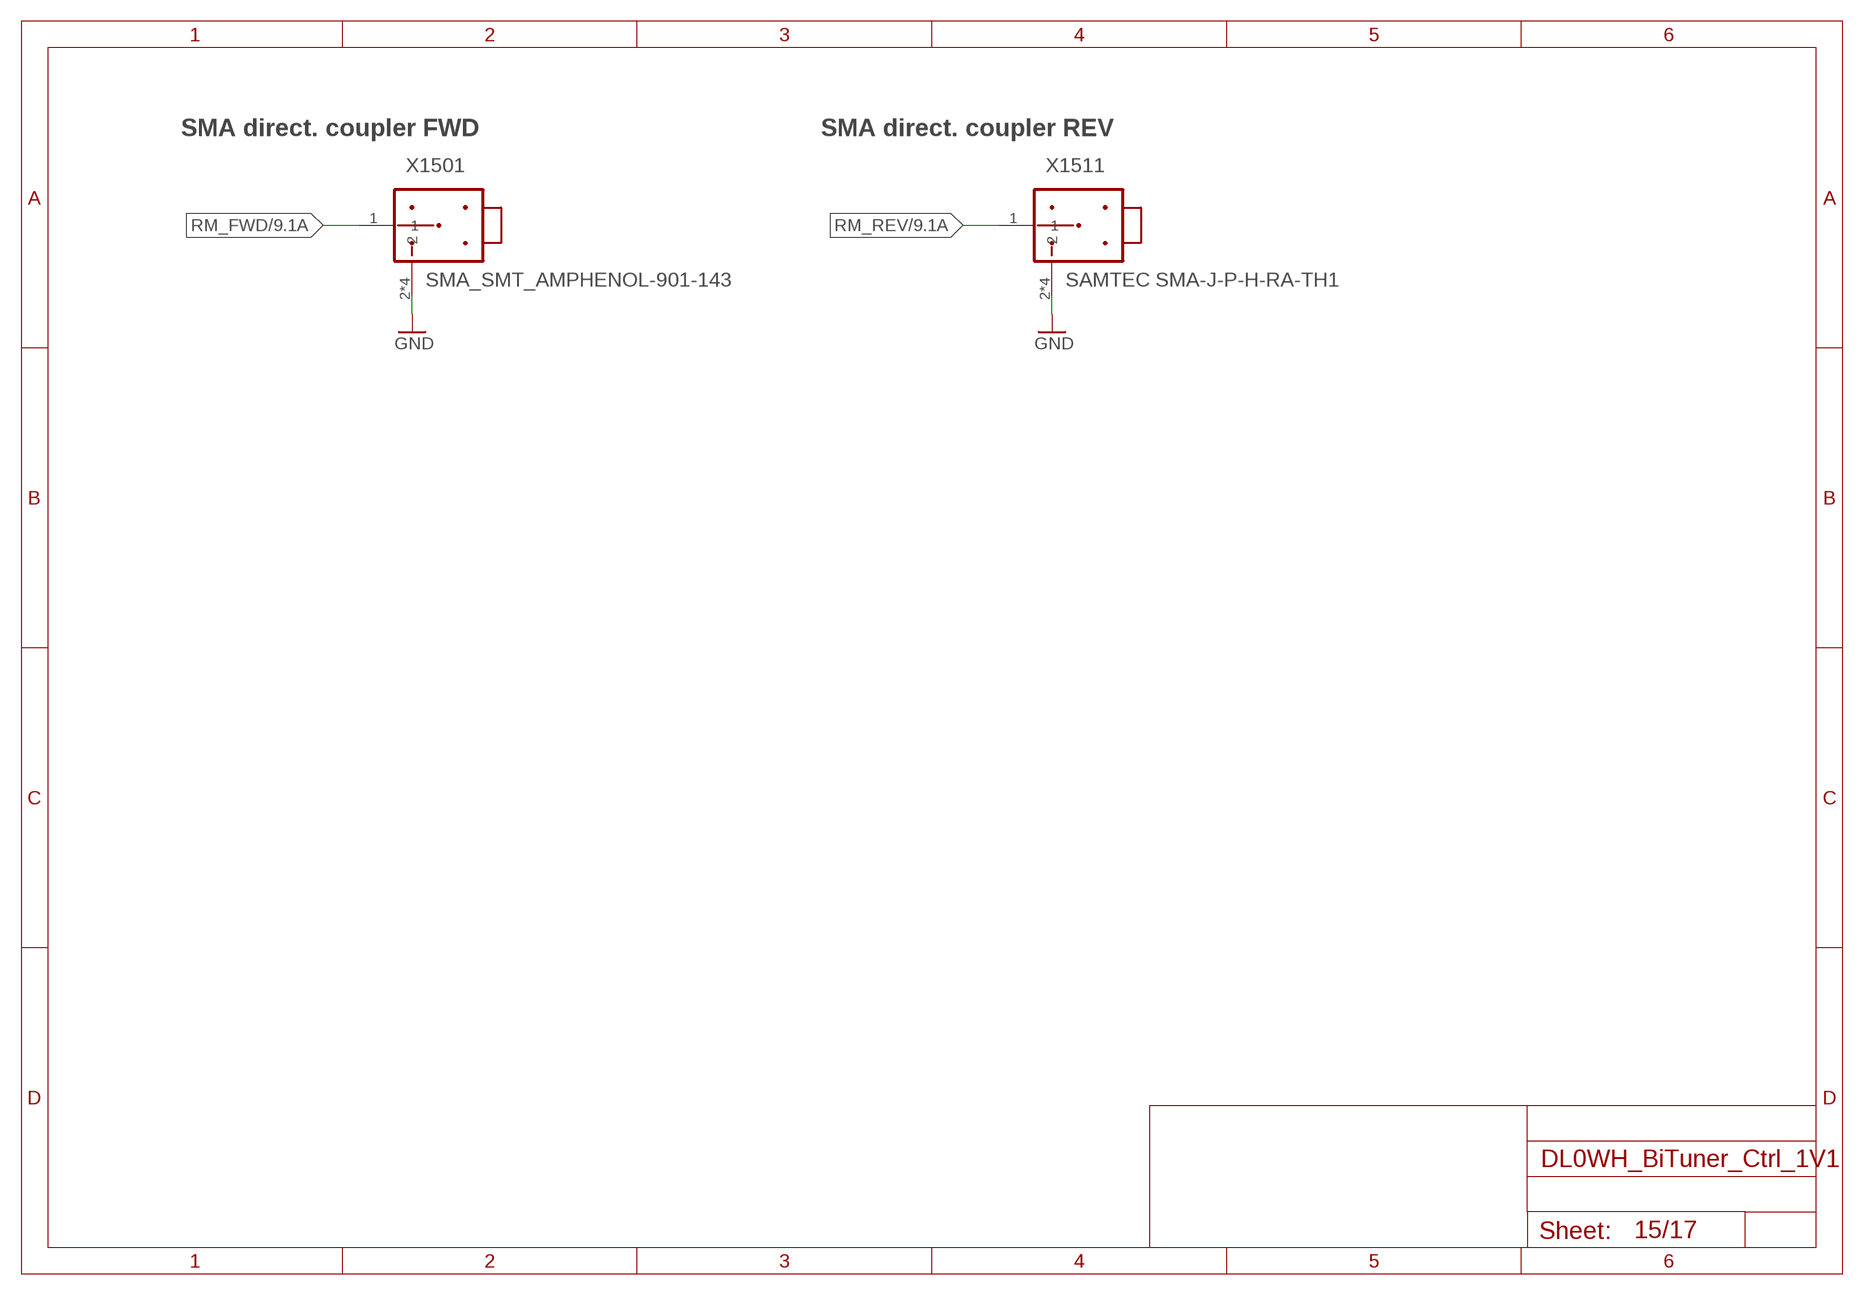
[diagram p14: schematic, sheet 15]
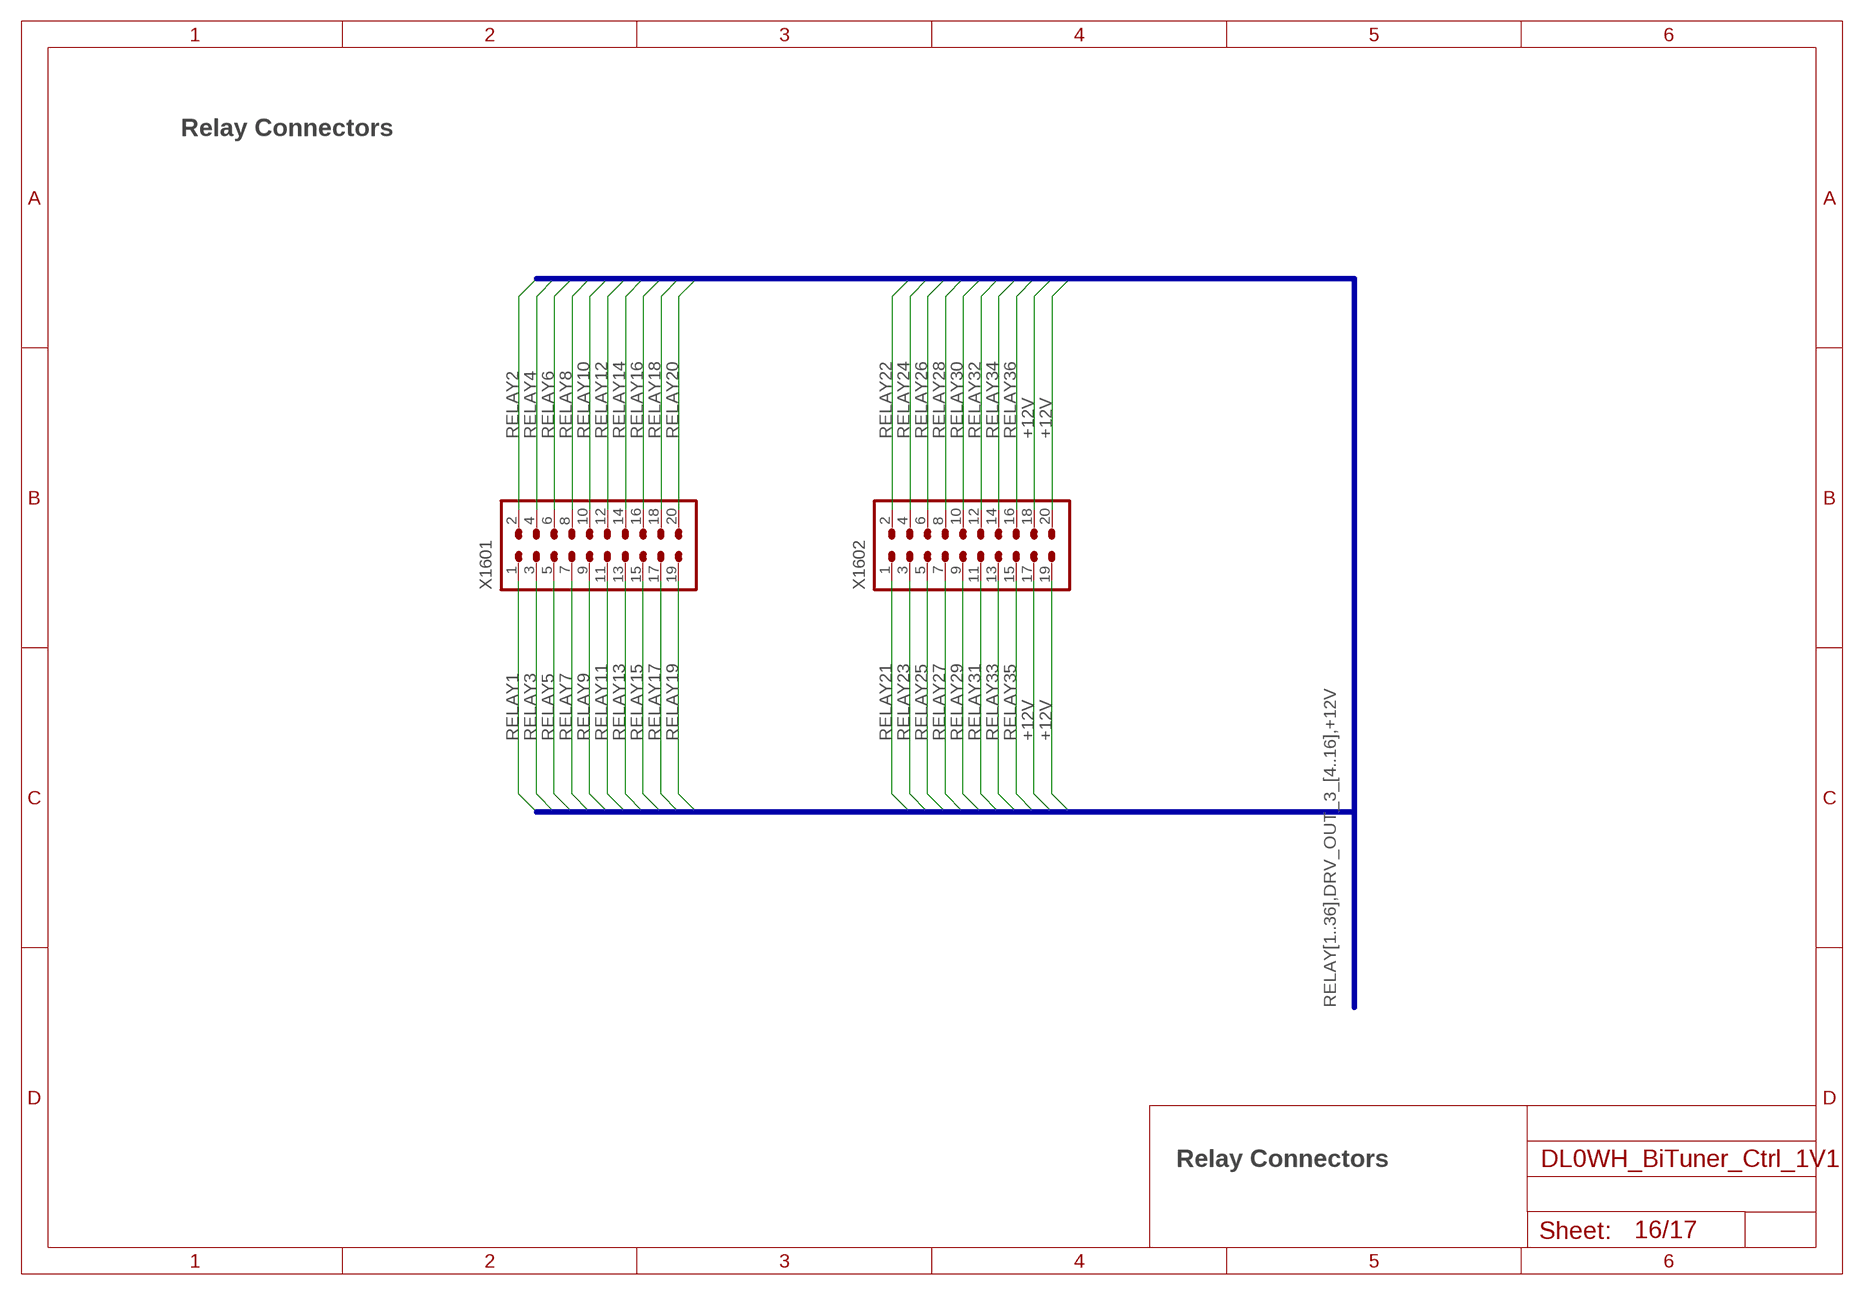
[diagram p15: schematic, sheet 16]
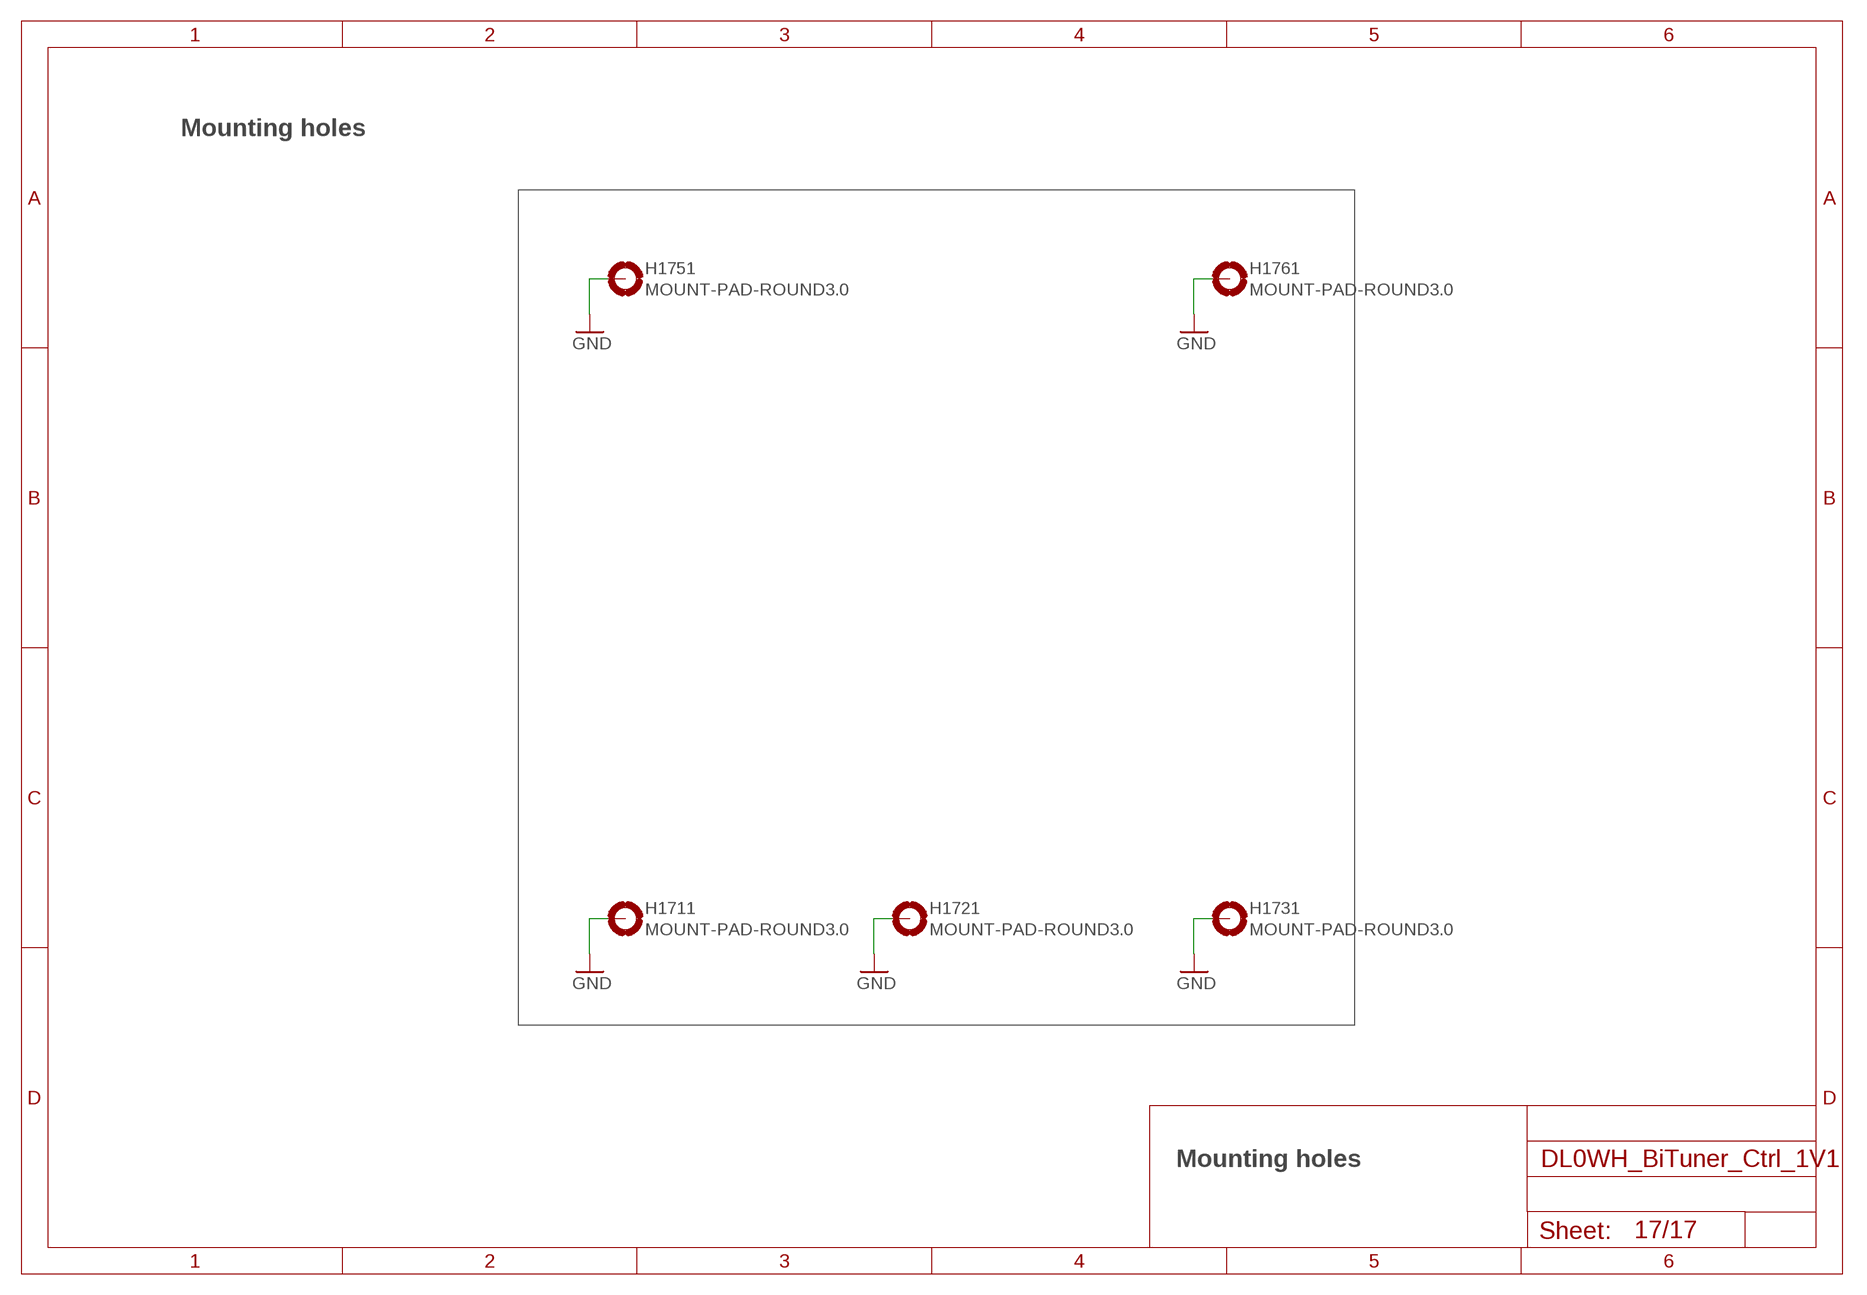
[diagram p16: schematic, sheet 17]

(export (version "E")
  (design (tool "Eeschema 10.0.6"))
  (components
    (comp (ref "U0101")
      (value "STM32L476RXT_64PIN_LDO")
      (footprint "eagle-import:LQFP64")
      (libsource (lib "eagle-import") (part "STM32L476RXT_64PIN_LDO"))
    )
    (comp (ref "C0601")
      (value "100nF")
      (footprint "eagle-import:C0402")
      (libsource (lib "eagle-import") (part "C-EUC0402"))
    )
    (comp (ref "C0602")
      (value "100nF")
      (footprint "eagle-import:C0402")
      (libsource (lib "eagle-import") (part "C-EUC0402"))
    )
    (comp (ref "C0603")
      (value "22uF")
      (footprint "eagle-import:C0603")
      (libsource (lib "eagle-import") (part "C-EUC0603"))
    )
    (comp (ref "R0611")
      (value "47R")
      (footprint "eagle-import:R0402")
      (libsource (lib "eagle-import") (part "R-EU_R0402"))
    )
    (comp (ref "R0621")
      (value "47R")
      (footprint "eagle-import:R0402")
      (libsource (lib "eagle-import") (part "R-EU_R0402"))
    )
    (comp (ref "R0622")
      (value "0R")
      (footprint "eagle-import:R0402")
      (libsource (lib "eagle-import") (part "R-EU_R0402"))
    )
    (comp (ref "R0623")
      (value "47R")
      (footprint "eagle-import:R0402")
      (libsource (lib "eagle-import") (part "R-EU_R0402"))
    )
    (comp (ref "R0624")
      (value "47R")
      (footprint "eagle-import:R0402")
      (libsource (lib "eagle-import") (part "R-EU_R0402"))
    )
    (comp (ref "R0625")
      (value "47R")
      (footprint "eagle-import:R0402")
      (libsource (lib "eagle-import") (part "R-EU_R0402"))
    )
    (comp (ref "R0626")
      (value "47R")
      (footprint "eagle-import:R0402")
      (libsource (lib "eagle-import") (part "R-EU_R0402"))
    )
    (comp (ref "U0601")
      (value "MC33996")
      (footprint "eagle-import:SOICW32")
      (libsource (lib "eagle-import") (part "MC33996"))
    )
    (comp (ref "C0701")
      (value "100nF")
      (footprint "eagle-import:C0402")
      (libsource (lib "eagle-import") (part "C-EUC0402"))
    )
    (comp (ref "C0702")
      (value "100nF")
      (footprint "eagle-import:C0402")
      (libsource (lib "eagle-import") (part "C-EUC0402"))
    )
    (comp (ref "C0703")
      (value "22uF")
      (footprint "eagle-import:C0603")
      (libsource (lib "eagle-import") (part "C-EUC0603"))
    )
    (comp (ref "R0711")
      (value "47R")
      (footprint "eagle-import:R0402")
      (libsource (lib "eagle-import") (part "R-EU_R0402"))
    )
    (comp (ref "R0724")
      (value "47R")
      (footprint "eagle-import:R0402")
      (libsource (lib "eagle-import") (part "R-EU_R0402"))
    )
    (comp (ref "U0701")
      (value "MC33996")
      (footprint "eagle-import:SOICW32")
      (libsource (lib "eagle-import") (part "MC33996"))
    )
    (comp (ref "C0054")
      (value "10nF")
      (footprint "eagle-import:C0603")
      (libsource (lib "eagle-import") (part "C-EUC0603"))
    )
    (comp (ref "C1001")
      (value "1uF")
      (footprint "eagle-import:C0402")
      (libsource (lib "eagle-import") (part "C-EUC0402"))
    )
    (comp (ref "C1002")
      (value "1uF")
      (footprint "eagle-import:C0402")
      (libsource (lib "eagle-import") (part "C-EUC0402"))
    )
    (comp (ref "C1003")
      (value "1uF")
      (footprint "eagle-import:C0402")
      (libsource (lib "eagle-import") (part "C-EUC0402"))
    )
    (comp (ref "C1004")
      (value "1uF")
      (footprint "eagle-import:C0402")
      (libsource (lib "eagle-import") (part "C-EUC0402"))
    )
    (comp (ref "C1005")
      (value "1uF")
      (footprint "eagle-import:C0402")
      (libsource (lib "eagle-import") (part "C-EUC0402"))
    )
    (comp (ref "C1051")
      (value "10nF")
      (footprint "eagle-import:C0603")
      (libsource (lib "eagle-import") (part "C-EUC0603"))
    )
    (comp (ref "C1052")
      (value "10nF")
      (footprint "eagle-import:C0603")
      (libsource (lib "eagle-import") (part "C-EUC0603"))
    )
    (comp (ref "C1053")
      (value "10nF")
      (footprint "eagle-import:C0603")
      (libsource (lib "eagle-import") (part "C-EUC0603"))
    )
    (comp (ref "R1001")
      (value "47R")
      (footprint "eagle-import:R0402")
      (libsource (lib "eagle-import") (part "R-EU_R0402"))
    )
    (comp (ref "R1002")
      (value "47R")
      (footprint "eagle-import:R0402")
      (libsource (lib "eagle-import") (part "R-EU_R0402"))
    )
    (comp (ref "R1003")
      (value "47R")
      (footprint "eagle-import:R0402")
      (libsource (lib "eagle-import") (part "R-EU_R0402"))
    )
    (comp (ref "R1004")
      (value "47R")
      (footprint "eagle-import:R0402")
      (libsource (lib "eagle-import") (part "R-EU_R0402"))
    )
    (comp (ref "U1001")
      (value "MAX232_SOIC16")
      (footprint "eagle-import:SOIC16N")
      (fields (field (name "MF") "MAXIM") (field (name "MPN") "MAX232ECDR"))
      (libsource (lib "eagle-import") (part "MAX232_SOIC16"))
    )
    (comp (ref "X1051")
      (value "WIRE-TO-BOARD_5MM08_1X02")
      (footprint "eagle-import:WIRE-TO-BOARD_5MM08_1X02")
      (libsource (lib "eagle-import") (part "WIRE-TO-BOARD_5MM08_1X02"))
    )
    (comp (ref "X1052")
      (value "WIRE-TO-BOARD_5MM08_1X02")
      (footprint "eagle-import:WIRE-TO-BOARD_5MM08_1X02")
      (libsource (lib "eagle-import") (part "WIRE-TO-BOARD_5MM08_1X02"))
    )
    (comp (ref "X1053")
      (value "WIRE-TO-BOARD_5MM08_1X02")
      (footprint "eagle-import:WIRE-TO-BOARD_5MM08_1X02")
      (libsource (lib "eagle-import") (part "WIRE-TO-BOARD_5MM08_1X02"))
    )
    (comp (ref "C0801")
      (value "100nF")
      (footprint "eagle-import:C0402")
      (libsource (lib "eagle-import") (part "C-EUC0402"))
    )
    (comp (ref "C0802")
      (value "100nF")
      (footprint "eagle-import:C0402")
      (libsource (lib "eagle-import") (part "C-EUC0402"))
    )
    (comp (ref "C0803")
      (value "22uF")
      (footprint "eagle-import:C0603")
      (libsource (lib "eagle-import") (part "C-EUC0603"))
    )
    (comp (ref "R0811")
      (value "47R")
      (footprint "eagle-import:R0402")
      (libsource (lib "eagle-import") (part "R-EU_R0402"))
    )
    (comp (ref "R0824")
      (value "47R")
      (footprint "eagle-import:R0402")
      (libsource (lib "eagle-import") (part "R-EU_R0402"))
    )
    (comp (ref "U0801")
      (value "MC33996")
      (footprint "eagle-import:SOICW32")
      (libsource (lib "eagle-import") (part "MC33996"))
    )
    (comp (ref "C1201")
      (value "10uF")
      (footprint "eagle-import:C0603")
      (libsource (lib "eagle-import") (part "C-EUC0603"))
    )
    (comp (ref "C1202")
      (value "10uF")
      (footprint "eagle-import:C0603")
      (libsource (lib "eagle-import") (part "C-EUC0603"))
    )
    (comp (ref "C1203")
      (value "10uF")
      (footprint "eagle-import:C0603")
      (libsource (lib "eagle-import") (part "C-EUC0603"))
    )
    (comp (ref "C1204")
      (value "10nF")
      (footprint "eagle-import:C0402")
      (libsource (lib "eagle-import") (part "C-EUC0402"))
    )
    (comp (ref "C1205")
      (value "3.3uF")
      (footprint "eagle-import:C0603")
      (libsource (lib "eagle-import") (part "C-EUC0603"))
    )
    (comp (ref "C1211")
      (value "0.47uF")
      (footprint "eagle-import:C0402")
      (libsource (lib "eagle-import") (part "C-EUC0402"))
    )
    (comp (ref "C1212")
      (value "100nF")
      (footprint "eagle-import:C0402")
      (libsource (lib "eagle-import") (part "C-EUC0402"))
    )
    (comp (ref "C1221")
      (value "22uF")
      (footprint "eagle-import:C0603")
      (libsource (lib "eagle-import") (part "C-EUC0603"))
    )
    (comp (ref "C1222")
      (value "22uF")
      (footprint "eagle-import:C0603")
      (libsource (lib "eagle-import") (part "C-EUC0603"))
    )
    (comp (ref "C1223")
      (value "22uF")
      (footprint "eagle-import:C0603")
      (libsource (lib "eagle-import") (part "C-EUC0603"))
    )
    (comp (ref "L1211")
      (value "2.2uH")
      (footprint "eagle-import:L_6.00MM_X_6.00MM")
      (libsource (lib "eagle-import") (part "L-EU6.00X6.00MM"))
    )
    (comp (ref "R1211")
      (value "3R")
      (footprint "eagle-import:R0402")
      (libsource (lib "eagle-import") (part "R-EU_R0402"))
    )
    (comp (ref "U1201")
      (value "LM53603-Q1")
      (footprint "eagle-import:HTSSOP16")
      (libsource (lib "eagle-import") (part "LM53603-Q1"))
    )
    (comp (ref "X1211")
      (value "WIRE-TO-BOARD_5MM08_1X02")
      (footprint "eagle-import:WIRE-TO-BOARD_5MM08_1X02")
      (libsource (lib "eagle-import") (part "WIRE-TO-BOARD_5MM08_1X02"))
    )
    (comp (ref "C1403")
      (value "1nF")
      (footprint "eagle-import:C0402")
      (libsource (lib "eagle-import") (part "C-EUC0402"))
    )
    (comp (ref "PF1411")
      (value "1.1A/2.2A")
      (footprint "eagle-import:M1206")
      (libsource (lib "eagle-import") (part "rcl_R-EU_M1206"))
    )
    (comp (ref "R1402")
      (value "330kR")
      (footprint "eagle-import:R0402")
      (libsource (lib "eagle-import") (part "R-EU_R0402"))
    )
    (comp (ref "X1401")
      (value "MOLEX 105017-0001")
      (footprint "eagle-import:USB-B-MICRO-SMD_MOLEX-105017-0001")
      (libsource (lib "eagle-import") (part "USB_MICRO-B_MOLEX"))
    )
    (comp (ref "H1711")
      (value "MOUNT-PAD-ROUND3.0")
      (footprint "eagle-import:3,0-PAD")
      (libsource (lib "eagle-import") (part "MOUNT-PAD-ROUND3.0"))
    )
    (comp (ref "H1721")
      (value "MOUNT-PAD-ROUND3.0")
      (footprint "eagle-import:3,0-PAD")
      (libsource (lib "eagle-import") (part "MOUNT-PAD-ROUND3.0"))
    )
    (comp (ref "H1731")
      (value "MOUNT-PAD-ROUND3.0")
      (footprint "eagle-import:3,0-PAD")
      (libsource (lib "eagle-import") (part "MOUNT-PAD-ROUND3.0"))
    )
    (comp (ref "H1751")
      (value "MOUNT-PAD-ROUND3.0")
      (footprint "eagle-import:3,0-PAD")
      (libsource (lib "eagle-import") (part "MOUNT-PAD-ROUND3.0"))
    )
    (comp (ref "H1761")
      (value "MOUNT-PAD-ROUND3.0")
      (footprint "eagle-import:3,0-PAD")
      (libsource (lib "eagle-import") (part "MOUNT-PAD-ROUND3.0"))
    )
    (comp (ref "C0311")
      (value "18pF")
      (footprint "eagle-import:C0402")
      (libsource (lib "eagle-import") (part "C-EUC0402"))
    )
    (comp (ref "C0331")
      (value "JR200")
      (footprint "eagle-import:3MM2_X_2MM5")
      (libsource (lib "eagle-import") (part "C-TRIMM3MM2_2MM5"))
    )
    (comp (ref "C0332")
      (value "8.2pF")
      (footprint "eagle-import:C0402")
      (libsource (lib "eagle-import") (part "C-EUC0402"))
    )
    (comp (ref "Q0321")
      (value "ABS07-32.768KHZ")
      (footprint "eagle-import:ABS07")
      (fields (field (name "MANUFACTURER") "ABS07-32.768KHZ-1-T"))
      (libsource (lib "eagle-import") (part "ABS07-32.768KHZ"))
    )
    (comp (ref "C0213")
      (value "100nF")
      (footprint "eagle-import:C0402")
      (libsource (lib "eagle-import") (part "C-EUC0402"))
    )
    (comp (ref "R0221")
      (value "33kR")
      (footprint "eagle-import:R0402")
      (libsource (lib "eagle-import") (part "R-EU_R0402"))
    )
    (comp (ref "R0231")
      (value "220kR")
      (footprint "eagle-import:R0402")
      (libsource (lib "eagle-import") (part "R-EU_R0402"))
    )
    (comp (ref "R0232")
      (value "220kR")
      (footprint "eagle-import:R0402")
      (libsource (lib "eagle-import") (part "R-EU_R0402"))
    )
    (comp (ref "S0212")
      (value "KSR223GLFG")
      (footprint "eagle-import:KSR223G_SMD_1POL")
      (libsource (lib "eagle-import") (part "KSR223G_SMD_1POL"))
    )
    (comp (ref "X0201")
      (value "HEADER-2X5_1MM27CORTEX_10PIN_JTAG-SWD")
      (footprint "eagle-import:2X05_SHROUDED_1MM27")
      (libsource (lib "eagle-import") (part "HEADER-2X5_1MM27CORTEX_10PIN_JTAG-SWD"))
    )
    (comp (ref "X0222")
      (value "HEADER-1X2")
      (footprint "eagle-import:1X02")
      (libsource (lib "eagle-import") (part "HEADER-1X2"))
    )
    (comp (ref "C1301")
      (value "22uF")
      (footprint "eagle-import:C0603")
      (libsource (lib "eagle-import") (part "C-EUC0603"))
    )
    (comp (ref "C1311")
      (value "22uF")
      (footprint "eagle-import:C0603")
      (libsource (lib "eagle-import") (part "C-EUC0603"))
    )
    (comp (ref "L1311")
      (value "10uH")
      (footprint "eagle-import:L_4.50MM_X_3.20MM")
      (libsource (lib "eagle-import") (part "L-EU4.50X3.20MM"))
    )
    (comp (ref "R1301")
      (value "100kR")
      (footprint "eagle-import:R0402")
      (libsource (lib "eagle-import") (part "R-EU_R0402"))
    )
    (comp (ref "R1302")
      (value "220kR")
      (footprint "eagle-import:R0402")
      (libsource (lib "eagle-import") (part "R-EU_R0402"))
    )
    (comp (ref "R1321")
      (value "1MR")
      (footprint "eagle-import:R0402")
      (libsource (lib "eagle-import") (part "R-EU_R0402"))
    )
    (comp (ref "R1322")
      (value "1MR")
      (footprint "eagle-import:R0402")
      (libsource (lib "eagle-import") (part "R-EU_R0402"))
    )
    (comp (ref "U1301")
      (value "TPS62056")
      (footprint "eagle-import:S-PDSO-G10")
      (libsource (lib "eagle-import") (part "TPS62051"))
    )
    (comp (ref "R0511")
      (value "1kR")
      (footprint "eagle-import:R0402")
      (libsource (lib "eagle-import") (part "R-EU_R0402"))
    )
    (comp (ref "R0512")
      (value "1kR")
      (footprint "eagle-import:R0402")
      (libsource (lib "eagle-import") (part "R-EU_R0402"))
    )
    (comp (ref "X0601")
      (value "HEADER-2X2")
      (footprint "eagle-import:2X02")
      (libsource (lib "eagle-import") (part "HEADER-2X2"))
    )
    (comp (ref "C0901")
      (value "10nF")
      (footprint "eagle-import:C0402")
      (libsource (lib "eagle-import") (part "C-EUC0402"))
    )
    (comp (ref "C0911")
      (value "10nF")
      (footprint "eagle-import:C0402")
      (libsource (lib "eagle-import") (part "C-EUC0402"))
    )
    (comp (ref "C0921")
      (value "100nF")
      (footprint "eagle-import:C0402")
      (libsource (lib "eagle-import") (part "C-EUC0402"))
    )
    (comp (ref "C0951")
      (value "100nF")
      (footprint "eagle-import:C0402")
      (libsource (lib "eagle-import") (part "C-EUC0402"))
    )
    (comp (ref "D0901")
      (value "CRS08")
      (footprint "eagle-import:SOD80C")
      (libsource (lib "eagle-import") (part "CRS08"))
    )
    (comp (ref "D0911")
      (value "CRS08")
      (footprint "eagle-import:SOD80C")
      (libsource (lib "eagle-import") (part "CRS08"))
    )
    (comp (ref "D0951")
      (value "CMAD6001")
      (footprint "eagle-import:SOD923")
      (libsource (lib "eagle-import") (part "D_SOD923"))
    )
    (comp (ref "D0961")
      (value "CMAD6001")
      (footprint "eagle-import:SOD923")
      (libsource (lib "eagle-import") (part "D_SOD923"))
    )
    (comp (ref "L0901")
      (value "10uH")
      (footprint "eagle-import:L0603")
      (libsource (lib "eagle-import") (part "L-EUL0603"))
    )
    (comp (ref "L0911")
      (value "10uH")
      (footprint "eagle-import:L0603")
      (libsource (lib "eagle-import") (part "L-EUL0603"))
    )
    (comp (ref "R0901")
      (value "1kR")
      (footprint "eagle-import:R0402")
      (libsource (lib "eagle-import") (part "R-EU_R0402"))
    )
    (comp (ref "R0902")
      (value "15kR")
      (footprint "eagle-import:R0402")
      (libsource (lib "eagle-import") (part "R-EU_R0402"))
    )
    (comp (ref "R0903")
      (value "100kR")
      (footprint "eagle-import:R0402")
      (libsource (lib "eagle-import") (part "R-EU_R0402"))
    )
    (comp (ref "R0911")
      (value "1kR")
      (footprint "eagle-import:R0402")
      (libsource (lib "eagle-import") (part "R-EU_R0402"))
    )
    (comp (ref "R0912")
      (value "15kR")
      (footprint "eagle-import:R0402")
      (libsource (lib "eagle-import") (part "R-EU_R0402"))
    )
    (comp (ref "R0913")
      (value "100kR")
      (footprint "eagle-import:R0402")
      (libsource (lib "eagle-import") (part "R-EU_R0402"))
    )
    (comp (ref "R0921")
      (value "47R")
      (footprint "eagle-import:R0402")
      (libsource (lib "eagle-import") (part "R-EU_R0402"))
    )
    (comp (ref "R0922")
      (value "47R")
      (footprint "eagle-import:R0402")
      (libsource (lib "eagle-import") (part "R-EU_R0402"))
    )
    (comp (ref "R0951")
      (value "1MR")
      (footprint "eagle-import:R0402")
      (libsource (lib "eagle-import") (part "R-EU_R0402"))
    )
    (comp (ref "R0952")
      (value "47R")
      (footprint "eagle-import:R0402")
      (libsource (lib "eagle-import") (part "R-EU_R0402"))
    )
    (comp (ref "R0961")
      (value "10kR")
      (footprint "eagle-import:R0402")
      (libsource (lib "eagle-import") (part "R-EU_R0402"))
    )
    (comp (ref "U0921")
      (value "TS5A23166")
      (footprint "eagle-import:R-PDSO-G8")
      (libsource (lib "eagle-import") (part "TS5A23166"))
    )
    (comp (ref "U0951")
      (value "OPA354")
      (footprint "eagle-import:SOT-23-5")
      (fields (field (name "MPN") "OPA354AIDBVT"))
      (libsource (lib "eagle-import") (part "OPA354"))
    )
    (comp (ref "C1101")
      (value "1uF")
      (footprint "eagle-import:C0402")
      (libsource (lib "eagle-import") (part "C-EUC0402"))
    )
    (comp (ref "C1102")
      (value "1uF")
      (footprint "eagle-import:C0402")
      (libsource (lib "eagle-import") (part "C-EUC0402"))
    )
    (comp (ref "C1103")
      (value "1uF")
      (footprint "eagle-import:C0402")
      (libsource (lib "eagle-import") (part "C-EUC0402"))
    )
    (comp (ref "C1104")
      (value "1uF")
      (footprint "eagle-import:C0402")
      (libsource (lib "eagle-import") (part "C-EUC0402"))
    )
    (comp (ref "C1105")
      (value "1uF")
      (footprint "eagle-import:C0402")
      (libsource (lib "eagle-import") (part "C-EUC0402"))
    )
    (comp (ref "C1151")
      (value "10nF")
      (footprint "eagle-import:C0603")
      (libsource (lib "eagle-import") (part "C-EUC0603"))
    )
    (comp (ref "C1152")
      (value "10nF")
      (footprint "eagle-import:C0603")
      (libsource (lib "eagle-import") (part "C-EUC0603"))
    )
    (comp (ref "C1153")
      (value "10nF")
      (footprint "eagle-import:C0603")
      (libsource (lib "eagle-import") (part "C-EUC0603"))
    )
    (comp (ref "C1154")
      (value "10nF")
      (footprint "eagle-import:C0603")
      (libsource (lib "eagle-import") (part "C-EUC0603"))
    )
    (comp (ref "R1101")
      (value "47R")
      (footprint "eagle-import:R0402")
      (libsource (lib "eagle-import") (part "R-EU_R0402"))
    )
    (comp (ref "R1102")
      (value "47R")
      (footprint "eagle-import:R0402")
      (libsource (lib "eagle-import") (part "R-EU_R0402"))
    )
    (comp (ref "R1103")
      (value "47R")
      (footprint "eagle-import:R0402")
      (libsource (lib "eagle-import") (part "R-EU_R0402"))
    )
    (comp (ref "R1104")
      (value "47R")
      (footprint "eagle-import:R0402")
      (libsource (lib "eagle-import") (part "R-EU_R0402"))
    )
    (comp (ref "U1101")
      (value "MAX232_SOIC16")
      (footprint "eagle-import:SOIC16N")
      (fields (field (name "MF") "MAXIM") (field (name "MPN") "MAX232ECDR"))
      (libsource (lib "eagle-import") (part "MAX232_SOIC16"))
    )
    (comp (ref "X1151")
      (value "WIRE-TO-BOARD_5MM08_1X02")
      (footprint "eagle-import:WIRE-TO-BOARD_5MM08_1X02")
      (libsource (lib "eagle-import") (part "WIRE-TO-BOARD_5MM08_1X02"))
    )
    (comp (ref "X1152")
      (value "WIRE-TO-BOARD_5MM08_1X02")
      (footprint "eagle-import:WIRE-TO-BOARD_5MM08_1X02")
      (libsource (lib "eagle-import") (part "WIRE-TO-BOARD_5MM08_1X02"))
    )
    (comp (ref "X1153")
      (value "WIRE-TO-BOARD_5MM08_1X02")
      (footprint "eagle-import:WIRE-TO-BOARD_5MM08_1X02")
      (libsource (lib "eagle-import") (part "WIRE-TO-BOARD_5MM08_1X02"))
    )
    (comp (ref "X1601")
      (value "2X10_2MM56_SOCKET")
      (footprint "eagle-import:2X10")
      (libsource (lib "eagle-import") (part "2X10_2MM56_SOCKET"))
    )
    (comp (ref "X1602")
      (value "2X10_2MM56_SOCKET")
      (footprint "eagle-import:2X10")
      (libsource (lib "eagle-import") (part "2X10_2MM56_SOCKET"))
    )
    (comp (ref "X1501")
      (value "SMA_SMT_AMPHENOL-901-143")
      (footprint "eagle-import:SMA_SMT_AMPHENOL_901-143")
      (fields (field (name "MPN") "901-143"))
      (libsource (lib "eagle-import") (part "SMA_SMT_AMPHENOL-901-143"))
    )
    (comp (ref "X1511")
      (value "SAMTEC SMA-J-P-H-RA-TH1")
      (footprint "eagle-import:SMA_SMT_AMPHENOL_901-143")
      (fields (field (name "MPN") "901-143"))
      (libsource (lib "eagle-import") (part "SMA_SMT_AMPHENOL-901-143"))
    )
    (comp (ref "C0401")
      (value "100nF")
      (footprint "eagle-import:C0402")
      (libsource (lib "eagle-import") (part "C-EUC0402"))
    )
    (comp (ref "C0402")
      (value "100nF")
      (footprint "eagle-import:C0402")
      (libsource (lib "eagle-import") (part "C-EUC0402"))
    )
    (comp (ref "C0403")
      (value "100nF")
      (footprint "eagle-import:C0402")
      (libsource (lib "eagle-import") (part "C-EUC0402"))
    )
    (comp (ref "C0410")
      (value "4.7uF")
      (footprint "eagle-import:C0603")
      (libsource (lib "eagle-import") (part "C-EUC0603"))
    )
    (comp (ref "C0412")
      (value "10nF")
      (footprint "eagle-import:C0402")
      (libsource (lib "eagle-import") (part "C-EUC0402"))
    )
    (comp (ref "C0413")
      (value "1uF")
      (footprint "eagle-import:C0402")
      (libsource (lib "eagle-import") (part "C-EUC0402"))
    )
    (comp (ref "C0451")
      (value "47uF")
      (footprint "eagle-import:C0805")
      (libsource (lib "eagle-import") (part "C-EUC0805"))
    )
    (comp (ref "L0411")
      (value "10uH")
      (footprint "eagle-import:L0603")
      (libsource (lib "eagle-import") (part "L-EUL0603"))
    )
    (comp (ref "R0441")
      (value "0R")
      (footprint "eagle-import:R0402")
      (libsource (lib "eagle-import") (part "R-EU_R0402"))
    )
    (comp (ref "SJ0401")
      (value "SJ")
      (footprint "eagle-import:SJ")
      (libsource (lib "eagle-import") (part "SJ"))
    )
    (comp (ref "TP_VBAT")
      (value "PTR1B1,27")
      (footprint "eagle-import:B1,27")
      (libsource (lib "eagle-import") (part "PTR1B1,27"))
    )
  )
  (nets
    (net (code "26") (name "+3V3") (class "Default")
      (node (ref "C0601") (pin "2") (pinfunction "2_2") (pintype "passive"))
      (node (ref "C0701") (pin "2") (pinfunction "2_2") (pintype "passive"))
      (node (ref "C0801") (pin "2") (pinfunction "2_2") (pintype "passive"))
      (node (ref "C0921") (pin "1") (pinfunction "1_1") (pintype "passive"))
      (node (ref "C0951") (pin "1") (pinfunction "1_1") (pintype "passive"))
      (node (ref "C1311") (pin "1") (pinfunction "1_1") (pintype "passive"))
      (node (ref "D0901") (pin "C") (pinfunction "C_C") (pintype "passive"))
      (node (ref "D0911") (pin "C") (pinfunction "C_C") (pintype "passive"))
      (node (ref "L1311") (pin "1") (pinfunction "1_1") (pintype "passive"))
      (node (ref "L1311") (pin "3") (pinfunction "1_3") (pintype "passive"))
      (node (ref "R0231") (pin "2") (pinfunction "2_2") (pintype "passive"))
      (node (ref "R0511") (pin "2") (pinfunction "2_2") (pintype "passive"))
      (node (ref "R0512") (pin "2") (pinfunction "2_2") (pintype "passive"))
      (node (ref "R0903") (pin "2") (pinfunction "2_2") (pintype "passive"))
      (node (ref "R0913") (pin "2") (pinfunction "2_2") (pintype "passive"))
      (node (ref "R0961") (pin "1") (pinfunction "1_1") (pintype "passive"))
      (node (ref "R1321") (pin "2") (pinfunction "2_2") (pintype "passive"))
      (node (ref "R1322") (pin "2") (pinfunction "2_2") (pintype "passive"))
      (node (ref "SJ0401") (pin "1") (pinfunction "1_1") (pintype "passive"))
      (node (ref "U0601") (pin "3") (pinfunction "SOPWR_3") (pintype "power_in"))
      (node (ref "U0701") (pin "3") (pinfunction "SOPWR_3") (pintype "power_in"))
      (node (ref "U0801") (pin "3") (pinfunction "SOPWR_3") (pintype "power_in"))
      (node (ref "U0921") (pin "8") (pinfunction "8_8") (pintype "power_in"))
      (node (ref "U0951") (pin "5") (pinfunction "V+_5") (pintype "power_in"))
      (node (ref "U1301") (pin "5") (pinfunction "FB_5") (pintype "passive"))
      (node (ref "X0201") (pin "1") (pinfunction "1_1") (pintype "passive"))
      (node (ref "X0222") (pin "1") (pinfunction "1_1") (pintype "passive"))
    )
    (net (code "27") (name "+5V") (class "Default")
      (node (ref "C1001") (pin "1") (pinfunction "1_1") (pintype "passive"))
      (node (ref "C1101") (pin "1") (pinfunction "1_1") (pintype "passive"))
      (node (ref "C1221") (pin "1") (pinfunction "1_1") (pintype "passive"))
      (node (ref "C1222") (pin "1") (pinfunction "1_1") (pintype "passive"))
      (node (ref "C1223") (pin "1") (pinfunction "1_1") (pintype "passive"))
      (node (ref "C1301") (pin "1") (pinfunction "1_1") (pintype "passive"))
      (node (ref "L1211") (pin "1") (pinfunction "1_1") (pintype "passive"))
      (node (ref "R1211") (pin "2") (pinfunction "2_2") (pintype "passive"))
      (node (ref "R1302") (pin "2") (pinfunction "2_2") (pintype "passive"))
      (node (ref "U1001") (pin "16") (pinfunction "VCC_16") (pintype "power_in"))
      (node (ref "U1101") (pin "16") (pinfunction "VCC_16") (pintype "power_in"))
      (node (ref "U1201") (pin "9") (pinfunction "FB_9") (pintype "passive"))
      (node (ref "U1301") (pin "1") (pinfunction "VIN_1") (pintype "power_in"))
      (node (ref "U1301") (pin "8") (pinfunction "EN_8") (pintype "input"))
    )
    (net (code "28") (name "+12V") (class "Default")
      (node (ref "C0602") (pin "1") (pinfunction "1_1") (pintype "passive"))
      (node (ref "C0603") (pin "1") (pinfunction "1_1") (pintype "passive"))
      (node (ref "C0702") (pin "1") (pinfunction "1_1") (pintype "passive"))
      (node (ref "C0703") (pin "1") (pinfunction "1_1") (pintype "passive"))
      (node (ref "C0802") (pin "1") (pinfunction "1_1") (pintype "passive"))
      (node (ref "C0803") (pin "1") (pinfunction "1_1") (pintype "passive"))
      (node (ref "C1201") (pin "1") (pinfunction "1_1") (pintype "passive"))
      (node (ref "C1202") (pin "1") (pinfunction "1_1") (pintype "passive"))
      (node (ref "C1203") (pin "1") (pinfunction "1_1") (pintype "passive"))
      (node (ref "C1204") (pin "1") (pinfunction "1_1") (pintype "passive"))
      (node (ref "U0601") (pin "6") (pinfunction "VPWR_6") (pintype "power_in"))
      (node (ref "U0701") (pin "6") (pinfunction "VPWR_6") (pintype "power_in"))
      (node (ref "U0801") (pin "6") (pinfunction "VPWR_6") (pintype "power_in"))
      (node (ref "U1201") (pin "11") (pinfunction "EN_11") (pintype "input"))
      (node (ref "U1201") (pin "12") (pinfunction "VIN_12") (pintype "power_in"))
      (node (ref "U1201") (pin "13") (pinfunction "VIN_13") (pintype "power_in"))
      (node (ref "X1211") (pin "1") (pinfunction "1_1") (pintype "passive"))
      (node (ref "X1602") (pin "17") (pinfunction "17_17") (pintype "passive"))
      (node (ref "X1602") (pin "18") (pinfunction "18_18") (pintype "passive"))
      (node (ref "X1602") (pin "19") (pinfunction "19_19") (pintype "passive"))
      (node (ref "X1602") (pin "20") (pinfunction "20_20") (pintype "passive"))
    )
    (net (code "40") (name "CAT_DTE_CTS") (class "Default")
      (node (ref "C1153") (pin "1") (pinfunction "1_1") (pintype "passive"))
      (node (ref "U1101") (pin "7") (pinfunction "T2OUT_7") (pintype "output"))
      (node (ref "X1153") (pin "1") (pinfunction "1_1") (pintype "passive"))
    )
    (net (code "41") (name "CAT_DTE_RTR") (class "Default")
      (node (ref "C1154") (pin "1") (pinfunction "1_1") (pintype "passive"))
      (node (ref "U1101") (pin "8") (pinfunction "R2IN_8") (pintype "input"))
      (node (ref "X1153") (pin "2") (pinfunction "2_2") (pintype "passive"))
    )
    (net (code "42") (name "CAT_DTE_RXD") (class "Default")
      (node (ref "C1151") (pin "1") (pinfunction "1_1") (pintype "passive"))
      (node (ref "U1101") (pin "14") (pinfunction "T1OUT_14") (pintype "output"))
      (node (ref "X1151") (pin "1") (pinfunction "1_1") (pintype "passive"))
    )
    (net (code "43") (name "CAT_DTE_TXD") (class "Default")
      (node (ref "C1152") (pin "1") (pinfunction "1_1") (pintype "passive"))
      (node (ref "U1101") (pin "13") (pinfunction "R1IN_13") (pintype "input"))
      (node (ref "X1151") (pin "2") (pinfunction "2_2") (pintype "passive"))
    )
    (net (code "44") (name "CAT_MX_C1P") (class "Default")
      (node (ref "C1102") (pin "1") (pinfunction "1_1") (pintype "passive"))
      (node (ref "U1101") (pin "1") (pinfunction "C1+_1") (pintype "bidirectional"))
    )
    (net (code "45") (name "CAT_MX_C2P") (class "Default")
      (node (ref "C1103") (pin "1") (pinfunction "1_1") (pintype "passive"))
      (node (ref "U1101") (pin "4") (pinfunction "C2+_4") (pintype "bidirectional"))
    )
    (net (code "46") (name "CAT_MX_VM") (class "Default")
      (node (ref "C1105") (pin "1") (pinfunction "1_1") (pintype "passive"))
      (node (ref "U1101") (pin "6") (pinfunction "V-_6") (pintype "bidirectional"))
    )
    (net (code "47") (name "CAT_MX_VP") (class "Default")
      (node (ref "C1104") (pin "1") (pinfunction "1_1") (pintype "passive"))
      (node (ref "U1101") (pin "2") (pinfunction "V+_2") (pintype "bidirectional"))
    )
    (net (code "48") (name "DRV_OUT_3_4") (class "Default")
      (node (ref "U0801") (pin "12") (pinfunction "OUT4_12") (pintype "passive"))
    )
    (net (code "49") (name "DRV_OUT_3_5") (class "Default")
      (node (ref "U0801") (pin "13") (pinfunction "OUT5_13") (pintype "passive"))
    )
    (net (code "50") (name "DRV_OUT_3_6") (class "Default")
      (node (ref "U0801") (pin "15") (pinfunction "OUT6_15") (pintype "passive"))
    )
    (net (code "51") (name "DRV_OUT_3_7") (class "Default")
      (node (ref "U0801") (pin "16") (pinfunction "OUT7_16") (pintype "passive"))
    )
    (net (code "52") (name "DRV_OUT_3_8") (class "Default")
      (node (ref "U0801") (pin "17") (pinfunction "OUT8_17") (pintype "passive"))
    )
    (net (code "53") (name "DRV_OUT_3_9") (class "Default")
      (node (ref "U0801") (pin "18") (pinfunction "OUT9_18") (pintype "passive"))
    )
    (net (code "54") (name "DRV_OUT_3_10") (class "Default")
      (node (ref "U0801") (pin "20") (pinfunction "OUT10_20") (pintype "passive"))
    )
    (net (code "55") (name "DRV_OUT_3_11") (class "Default")
      (node (ref "U0801") (pin "21") (pinfunction "OUT11_21") (pintype "passive"))
    )
    (net (code "56") (name "DRV_OUT_3_12") (class "Default")
      (node (ref "U0801") (pin "28") (pinfunction "OUT12_28") (pintype "passive"))
    )
    (net (code "57") (name "DRV_OUT_3_13") (class "Default")
      (node (ref "U0801") (pin "29") (pinfunction "OUT13_29") (pintype "passive"))
    )
    (net (code "58") (name "DRV_OUT_3_14") (class "Default")
      (node (ref "U0801") (pin "31") (pinfunction "OUT14_31") (pintype "passive"))
    )
    (net (code "59") (name "DRV_OUT_3_15") (class "Default")
      (node (ref "U0801") (pin "32") (pinfunction "OUT15_32") (pintype "passive"))
    )
    (net (code "60") (name "GND") (class "Default")
      (node (ref "C0054") (pin "2") (pinfunction "2_2") (pintype "passive"))
      (node (ref "C0213") (pin "2") (pinfunction "2_2") (pintype "passive"))
      (node (ref "C0311") (pin "2") (pinfunction "2_2") (pintype "passive"))
      (node (ref "C0331") (pin "+") (pinfunction "A_+") (pintype "passive"))
      (node (ref "C0332") (pin "2") (pinfunction "2_2") (pintype "passive"))
      (node (ref "C0401") (pin "2") (pinfunction "2_2") (pintype "passive"))
      (node (ref "C0402") (pin "2") (pinfunction "2_2") (pintype "passive"))
      (node (ref "C0403") (pin "2") (pinfunction "2_2") (pintype "passive"))
      (node (ref "C0410") (pin "2") (pinfunction "2_2") (pintype "passive"))
      (node (ref "C0412") (pin "2") (pinfunction "2_2") (pintype "passive"))
      (node (ref "C0413") (pin "2") (pinfunction "2_2") (pintype "passive"))
      (node (ref "C0451") (pin "2") (pinfunction "2_2") (pintype "passive"))
      (node (ref "C0601") (pin "1") (pinfunction "1_1") (pintype "passive"))
      (node (ref "C0602") (pin "2") (pinfunction "2_2") (pintype "passive"))
      (node (ref "C0603") (pin "2") (pinfunction "2_2") (pintype "passive"))
      (node (ref "C0701") (pin "1") (pinfunction "1_1") (pintype "passive"))
      (node (ref "C0702") (pin "2") (pinfunction "2_2") (pintype "passive"))
      (node (ref "C0703") (pin "2") (pinfunction "2_2") (pintype "passive"))
      (node (ref "C0801") (pin "1") (pinfunction "1_1") (pintype "passive"))
      (node (ref "C0802") (pin "2") (pinfunction "2_2") (pintype "passive"))
      (node (ref "C0803") (pin "2") (pinfunction "2_2") (pintype "passive"))
      (node (ref "C0901") (pin "2") (pinfunction "2_2") (pintype "passive"))
      (node (ref "C0911") (pin "2") (pinfunction "2_2") (pintype "passive"))
      (node (ref "C0921") (pin "2") (pinfunction "2_2") (pintype "passive"))
      (node (ref "C0951") (pin "2") (pinfunction "2_2") (pintype "passive"))
      (node (ref "C1001") (pin "2") (pinfunction "2_2") (pintype "passive"))
      (node (ref "C1004") (pin "2") (pinfunction "2_2") (pintype "passive"))
      (node (ref "C1005") (pin "2") (pinfunction "2_2") (pintype "passive"))
      (node (ref "C1051") (pin "2") (pinfunction "2_2") (pintype "passive"))
      (node (ref "C1052") (pin "2") (pinfunction "2_2") (pintype "passive"))
      (node (ref "C1053") (pin "2") (pinfunction "2_2") (pintype "passive"))
      (node (ref "C1101") (pin "2") (pinfunction "2_2") (pintype "passive"))
      (node (ref "C1104") (pin "2") (pinfunction "2_2") (pintype "passive"))
      (node (ref "C1105") (pin "2") (pinfunction "2_2") (pintype "passive"))
      (node (ref "C1151") (pin "2") (pinfunction "2_2") (pintype "passive"))
      (node (ref "C1152") (pin "2") (pinfunction "2_2") (pintype "passive"))
      (node (ref "C1153") (pin "2") (pinfunction "2_2") (pintype "passive"))
      (node (ref "C1154") (pin "2") (pinfunction "2_2") (pintype "passive"))
      (node (ref "C1201") (pin "2") (pinfunction "2_2") (pintype "passive"))
      (node (ref "C1202") (pin "2") (pinfunction "2_2") (pintype "passive"))
      (node (ref "C1203") (pin "2") (pinfunction "2_2") (pintype "passive"))
      (node (ref "C1204") (pin "2") (pinfunction "2_2") (pintype "passive"))
      (node (ref "C1205") (pin "1") (pinfunction "1_1") (pintype "passive"))
      (node (ref "C1212") (pin "2") (pinfunction "2_2") (pintype "passive"))
      (node (ref "C1221") (pin "2") (pinfunction "2_2") (pintype "passive"))
      (node (ref "C1222") (pin "2") (pinfunction "2_2") (pintype "passive"))
      (node (ref "C1223") (pin "2") (pinfunction "2_2") (pintype "passive"))
      (node (ref "C1301") (pin "2") (pinfunction "2_2") (pintype "passive"))
      (node (ref "C1311") (pin "2") (pinfunction "2_2") (pintype "passive"))
      (node (ref "C1403") (pin "1") (pinfunction "1_1") (pintype "passive"))
      (node (ref "D0961") (pin "C") (pinfunction "C_C") (pintype "passive"))
      (node (ref "H1711") (pin "B3,0") (pinfunction "MOUNT_B3,0") (pintype "passive"))
      (node (ref "H1721") (pin "B3,0") (pinfunction "MOUNT_B3,0") (pintype "passive"))
      (node (ref "H1731") (pin "B3,0") (pinfunction "MOUNT_B3,0") (pintype "passive"))
      (node (ref "H1751") (pin "B3,0") (pinfunction "MOUNT_B3,0") (pintype "passive"))
      (node (ref "H1761") (pin "B3,0") (pinfunction "MOUNT_B3,0") (pintype "passive"))
      (node (ref "R0221") (pin "1") (pinfunction "1_1") (pintype "passive"))
      (node (ref "R0232") (pin "1") (pinfunction "1_1") (pintype "passive"))
      (node (ref "R0441") (pin "1") (pinfunction "1_1") (pintype "passive"))
      (node (ref "R0901") (pin "1") (pinfunction "1_1") (pintype "passive"))
      (node (ref "R0911") (pin "1") (pinfunction "1_1") (pintype "passive"))
      (node (ref "R0951") (pin "1") (pinfunction "1_1") (pintype "passive"))
      (node (ref "R1301") (pin "1") (pinfunction "1_1") (pintype "passive"))
      (node (ref "R1402") (pin "1") (pinfunction "1_1") (pintype "passive"))
      (node (ref "S0212") (pin "1") (pinfunction "P_1") (pintype "passive"))
      (node (ref "U0101") (pin "18") (pinfunction "VSS_18") (pintype "passive"))
      (node (ref "U0101") (pin "31") (pinfunction "VSS_31") (pintype "passive"))
      (node (ref "U0101") (pin "47") (pinfunction "VSS_47") (pintype "passive"))
      (node (ref "U0101") (pin "63") (pinfunction "VSS_63") (pintype "passive"))
      (node (ref "U0601") (pin "10") (pinfunction "GND_MC_10") (pintype "passive"))
      (node (ref "U0601") (pin "23") (pinfunction "GND_MC_23") (pintype "passive"))
      (node (ref "U0601") (pin "24") (pinfunction "GND_MC_24") (pintype "passive"))
      (node (ref "U0601") (pin "25") (pinfunction "GND_MC_25") (pintype "passive"))
      (node (ref "U0601") (pin "26") (pinfunction "GND_MC_26") (pintype "passive"))
      (node (ref "U0601") (pin "33") (pinfunction "EP_33") (pintype "passive"))
      (node (ref "U0601") (pin "7") (pinfunction "GND_MC_7") (pintype "passive"))
      (node (ref "U0601") (pin "8") (pinfunction "GND_MC_8") (pintype "passive"))
      (node (ref "U0601") (pin "9") (pinfunction "GND_MC_9") (pintype "passive"))
      (node (ref "U0701") (pin "10") (pinfunction "GND_MC_10") (pintype "passive"))
      (node (ref "U0701") (pin "23") (pinfunction "GND_MC_23") (pintype "passive"))
      (node (ref "U0701") (pin "24") (pinfunction "GND_MC_24") (pintype "passive"))
      (node (ref "U0701") (pin "25") (pinfunction "GND_MC_25") (pintype "passive"))
      (node (ref "U0701") (pin "26") (pinfunction "GND_MC_26") (pintype "passive"))
      (node (ref "U0701") (pin "33") (pinfunction "EP_33") (pintype "passive"))
      (node (ref "U0701") (pin "7") (pinfunction "GND_MC_7") (pintype "passive"))
      (node (ref "U0701") (pin "8") (pinfunction "GND_MC_8") (pintype "passive"))
      (node (ref "U0701") (pin "9") (pinfunction "GND_MC_9") (pintype "passive"))
      (node (ref "U0801") (pin "10") (pinfunction "GND_MC_10") (pintype "passive"))
      (node (ref "U0801") (pin "23") (pinfunction "GND_MC_23") (pintype "passive"))
      (node (ref "U0801") (pin "24") (pinfunction "GND_MC_24") (pintype "passive"))
      (node (ref "U0801") (pin "25") (pinfunction "GND_MC_25") (pintype "passive"))
      (node (ref "U0801") (pin "26") (pinfunction "GND_MC_26") (pintype "passive"))
      (node (ref "U0801") (pin "33") (pinfunction "EP_33") (pintype "passive"))
      (node (ref "U0801") (pin "7") (pinfunction "GND_MC_7") (pintype "passive"))
      (node (ref "U0801") (pin "8") (pinfunction "GND_MC_8") (pintype "passive"))
      (node (ref "U0801") (pin "9") (pinfunction "GND_MC_9") (pintype "passive"))
      (node (ref "U0921") (pin "4") (pinfunction "4_4") (pintype "passive"))
      (node (ref "U0951") (pin "2") (pinfunction "V-_2") (pintype "power_in"))
      (node (ref "U0951") (pin "3") (pinfunction "+IN_3") (pintype "input"))
      (node (ref "U1001") (pin "15") (pinfunction "GND_15") (pintype "power_in"))
      (node (ref "U1101") (pin "15") (pinfunction "GND_15") (pintype "power_in"))
      (node (ref "U1201") (pin "10") (pinfunction "AGND_10") (pintype "passive"))
      (node (ref "U1201") (pin "15") (pinfunction "PGND_15") (pintype "passive"))
      (node (ref "U1201") (pin "16") (pinfunction "PGND_16") (pintype "passive"))
      (node (ref "U1201") (pin "6") (pinfunction "SYNC_6") (pintype "input"))
      (node (ref "U1201") (pin "7") (pinfunction "FPWM_7") (pintype "input"))
      (node (ref "U1201") (pin "PAD") (pinfunction "EP_PAD") (pintype "passive"))
      (node (ref "U1201") (pin "PAD1") (pinfunction "EP_PAD1") (pintype "passive"))
      (node (ref "U1201") (pin "PAD10") (pinfunction "EP_PAD10") (pintype "passive"))
      (node (ref "U1201") (pin "PAD11") (pinfunction "EP_PAD11") (pintype "passive"))
      (node (ref "U1201") (pin "PAD12") (pinfunction "EP_PAD12") (pintype "passive"))
      (node (ref "U1201") (pin "PAD13") (pinfunction "EP_PAD13") (pintype "passive"))
      (node (ref "U1201") (pin "PAD2") (pinfunction "EP_PAD2") (pintype "passive"))
      (node (ref "U1201") (pin "PAD3") (pinfunction "EP_PAD3") (pintype "passive"))
      (node (ref "U1201") (pin "PAD4") (pinfunction "EP_PAD4") (pintype "passive"))
      (node (ref "U1201") (pin "PAD5") (pinfunction "EP_PAD5") (pintype "passive"))
      (node (ref "U1201") (pin "PAD6") (pinfunction "EP_PAD6") (pintype "passive"))
      (node (ref "U1201") (pin "PAD7") (pinfunction "EP_PAD7") (pintype "passive"))
      (node (ref "U1201") (pin "PAD8") (pinfunction "EP_PAD8") (pintype "passive"))
      (node (ref "U1201") (pin "PAD9") (pinfunction "EP_PAD9") (pintype "passive"))
      (node (ref "U1301") (pin "10") (pinfunction "PGND_10") (pintype "passive"))
      (node (ref "U1301") (pin "3") (pinfunction "VSS_3") (pintype "passive"))
      (node (ref "U1301") (pin "7") (pinfunction "SYNC_7") (pintype "input"))
      (node (ref "X0201") (pin "3") (pinfunction "3_3") (pintype "passive"))
      (node (ref "X0201") (pin "5") (pinfunction "5_5") (pintype "passive"))
      (node (ref "X0201") (pin "9") (pinfunction "9_9") (pintype "passive"))
      (node (ref "X0601") (pin "2") (pinfunction "2_2") (pintype "passive"))
      (node (ref "X0601") (pin "4") (pinfunction "4_4") (pintype "passive"))
      (node (ref "X1052") (pin "1") (pinfunction "1_1") (pintype "passive"))
      (node (ref "X1052") (pin "2") (pinfunction "2_2") (pintype "passive"))
      (node (ref "X1152") (pin "1") (pinfunction "1_1") (pintype "passive"))
      (node (ref "X1152") (pin "2") (pinfunction "2_2") (pintype "passive"))
      (node (ref "X1211") (pin "2") (pinfunction "2_2") (pintype "passive"))
      (node (ref "X1401") (pin "GND") (pinfunction "GND_GND") (pintype "passive"))
      (node (ref "X1501") (pin "2") (pinfunction "2_2") (pintype "passive"))
      (node (ref "X1501") (pin "3") (pinfunction "2_3") (pintype "passive"))
      (node (ref "X1501") (pin "4") (pinfunction "2_4") (pintype "passive"))
      (node (ref "X1501") (pin "5") (pinfunction "2_5") (pintype "passive"))
      (node (ref "X1511") (pin "2") (pinfunction "2_2") (pintype "passive"))
      (node (ref "X1511") (pin "3") (pinfunction "2_3") (pintype "passive"))
      (node (ref "X1511") (pin "4") (pinfunction "2_4") (pintype "passive"))
      (node (ref "X1511") (pin "5") (pinfunction "2_5") (pintype "passive"))
    )
    (net (code "61") (name "MCU_NRST") (class "Default")
      (node (ref "C0213") (pin "1") (pinfunction "1_1") (pintype "passive"))
      (node (ref "S0212") (pin "2") (pinfunction "S_2") (pintype "passive"))
      (node (ref "U0101") (pin "7") (pinfunction "NRST_7") (pintype "bidirectional"))
      (node (ref "X0201") (pin "10") (pinfunction "10_10") (pintype "passive"))
    )
    (net (code "62") (name "MCU_VBAT") (class "Default")
      (node (ref "C0451") (pin "1") (pinfunction "1_1") (pintype "passive"))
      (node (ref "TP_VBAT") (pin "TP") (pinfunction "TP_TP") (pintype "input"))
      (node (ref "U0101") (pin "1") (pinfunction "VBAT_1") (pintype "power_in"))
    )
    (net (code "63") (name "MCU_VDD") (class "Default")
      (node (ref "C0401") (pin "1") (pinfunction "1_1") (pintype "passive"))
      (node (ref "C0402") (pin "1") (pinfunction "1_1") (pintype "passive"))
      (node (ref "C0403") (pin "1") (pinfunction "1_1") (pintype "passive"))
      (node (ref "C0410") (pin "1") (pinfunction "1_1") (pintype "passive"))
      (node (ref "L0411") (pin "1") (pinfunction "1_1") (pintype "passive"))
      (node (ref "SJ0401") (pin "2") (pinfunction "2_2") (pintype "passive"))
      (node (ref "U0101") (pin "19") (pinfunction "VDD_19") (pintype "power_in"))
      (node (ref "U0101") (pin "32") (pinfunction "VDD_32") (pintype "power_in"))
      (node (ref "U0101") (pin "64") (pinfunction "VDD_64") (pintype "power_in"))
    )
    (net (code "64") (name "MCU_VDDA") (class "Default")
      (node (ref "C0412") (pin "1") (pinfunction "1_1") (pintype "passive"))
      (node (ref "C0413") (pin "1") (pinfunction "1_1") (pintype "passive"))
      (node (ref "L0411") (pin "2") (pinfunction "2_2") (pintype "passive"))
      (node (ref "U0101") (pin "13") (pinfunction "VDDA_VREF_P_13") (pintype "power_in"))
    )
    (net (code "65") (name "MCU_VREF_M") (class "Default")
      (node (ref "R0441") (pin "2") (pinfunction "2_2") (pintype "passive"))
      (node (ref "U0101") (pin "12") (pinfunction "VSSA_VREF_M_12") (pintype "passive"))
    )
    (net (code "66") (name "MP_CAT_CTS_R") (class "Default")
      (node (ref "R1103") (pin "2") (pinfunction "2_2") (pintype "passive"))
      (node (ref "U1101") (pin "10") (pinfunction "T2IN_10") (pintype "input"))
    )
    (net (code "67") (name "MP_CAT_RTR_R") (class "Default")
      (node (ref "R1104") (pin "2") (pinfunction "2_2") (pintype "passive"))
      (node (ref "U1101") (pin "9") (pinfunction "R2OUT_9") (pintype "output"))
    )
    (net (code "68") (name "MP_CAT_RXD_R") (class "Default")
      (node (ref "R1101") (pin "2") (pinfunction "2_2") (pintype "passive"))
      (node (ref "U1101") (pin "11") (pinfunction "T1IN_11") (pintype "input"))
    )
    (net (code "69") (name "MP_CAT_TXD_R") (class "Default")
      (node (ref "R1102") (pin "2") (pinfunction "2_2") (pintype "passive"))
      (node (ref "U1101") (pin "12") (pinfunction "R1OUT_12") (pintype "output"))
    )
    (net (code "70") (name "MP_RS_CTS_R") (class "Default")
      (node (ref "R1003") (pin "2") (pinfunction "2_2") (pintype "passive"))
      (node (ref "U1001") (pin "10") (pinfunction "T2IN_10") (pintype "input"))
    )
    (net (code "71") (name "MP_RS_RTR_R") (class "Default")
      (node (ref "R1004") (pin "2") (pinfunction "2_2") (pintype "passive"))
      (node (ref "U1001") (pin "9") (pinfunction "R2OUT_9") (pintype "output"))
    )
    (net (code "72") (name "MP_RS_RXD_R") (class "Default")
      (node (ref "R1001") (pin "2") (pinfunction "2_2") (pintype "passive"))
      (node (ref "U1001") (pin "11") (pinfunction "T1IN_11") (pintype "input"))
    )
    (net (code "73") (name "MP_RS_TXD_R") (class "Default")
      (node (ref "R1002") (pin "2") (pinfunction "2_2") (pintype "passive"))
      (node (ref "U1001") (pin "12") (pinfunction "R1OUT_12") (pintype "output"))
    )
    (net (code "74") (name "Net-(C1211-Pad1)") (class "Default")
      (node (ref "C1211") (pin "1") (pinfunction "1_1") (pintype "passive"))
      (node (ref "L1211") (pin "2") (pinfunction "2_2") (pintype "passive"))
      (node (ref "U1201") (pin "1") (pinfunction "SW_1") (pintype "passive"))
      (node (ref "U1201") (pin "2") (pinfunction "SW_2") (pintype "passive"))
    )
    (net (code "75") (name "Net-(C1403-Pad2)") (class "Default")
      (node (ref "C1403") (pin "2") (pinfunction "2_2") (pintype "passive"))
      (node (ref "R1402") (pin "2") (pinfunction "2_2") (pintype "passive"))
      (node (ref "X1401") (pin "JSHIELD") (pinfunction "SHIELD_JSHIELD") (pintype "passive"))
      (node (ref "X1401") (pin "JSHIELD@2") (pinfunction "SHIELD_JSHIELD@2") (pintype "passive"))
      (node (ref "X1401") (pin "JSHIELD@3") (pinfunction "SHIELD_JSHIELD@3") (pintype "passive"))
      (node (ref "X1401") (pin "JSHIELD@4") (pinfunction "SHIELD_JSHIELD@4") (pintype "passive"))
      (node (ref "X1401") (pin "JSHIELD@5") (pinfunction "SHIELD_JSHIELD@5") (pintype "passive"))
      (node (ref "X1401") (pin "JSHIELD@6") (pinfunction "SHIELD_JSHIELD@6") (pintype "passive"))
    )
    (net (code "76") (name "Net-(U0601-SO)") (class "Default")
      (node (ref "R0611") (pin "2") (pinfunction "2_2") (pintype "passive"))
      (node (ref "U0601") (pin "22") (pinfunction "SO_22") (pintype "output"))
    )
    (net (code "77") (name "Net-(U0701-SO)") (class "Default")
      (node (ref "R0711") (pin "2") (pinfunction "2_2") (pintype "passive"))
      (node (ref "U0701") (pin "22") (pinfunction "SO_22") (pintype "output"))
    )
    (net (code "78") (name "Net-(U0801-SO)") (class "Default")
      (node (ref "R0811") (pin "2") (pinfunction "2_2") (pintype "passive"))
      (node (ref "U0801") (pin "22") (pinfunction "SO_22") (pintype "output"))
    )
    (net (code "79") (name "Net-(U0951-OUT)") (class "Default")
      (node (ref "D0951") (pin "C") (pinfunction "C_C") (pintype "passive"))
      (node (ref "R0952") (pin "1") (pinfunction "1_1") (pintype "passive"))
      (node (ref "U0951") (pin "1") (pinfunction "OUT_1") (pintype "output"))
    )
    (net (code "80") (name "Net-(U1001A-C1-)") (class "Default")
      (node (ref "C1002") (pin "2") (pinfunction "2_2") (pintype "passive"))
      (node (ref "U1001") (pin "3") (pinfunction "C1-_3") (pintype "bidirectional"))
    )
    (net (code "81") (name "Net-(U1001A-C2-)") (class "Default")
      (node (ref "C1003") (pin "2") (pinfunction "2_2") (pintype "passive"))
      (node (ref "U1001") (pin "5") (pinfunction "C2-_5") (pintype "bidirectional"))
    )
    (net (code "82") (name "Net-(U1101A-C1-)") (class "Default")
      (node (ref "C1102") (pin "2") (pinfunction "2_2") (pintype "passive"))
      (node (ref "U1101") (pin "3") (pinfunction "C1-_3") (pintype "bidirectional"))
    )
    (net (code "83") (name "Net-(U1101A-C2-)") (class "Default")
      (node (ref "C1103") (pin "2") (pinfunction "2_2") (pintype "passive"))
      (node (ref "U1101") (pin "5") (pinfunction "C2-_5") (pintype "bidirectional"))
    )
    (net (code "84") (name "Net-(U1201-BIAS)") (class "Default")
      (node (ref "C1212") (pin "1") (pinfunction "1_1") (pintype "passive"))
      (node (ref "R1211") (pin "1") (pinfunction "1_1") (pintype "passive"))
      (node (ref "U1201") (pin "5") (pinfunction "BIAS_5") (pintype "power_in"))
    )
    (net (code "85") (name "Net-(U1201-CBOOT)") (class "Default")
      (node (ref "C1211") (pin "2") (pinfunction "2_2") (pintype "passive"))
      (node (ref "U1201") (pin "3") (pinfunction "CBOOT_3") (pintype "passive"))
    )
    (net (code "86") (name "Net-(U1201-VCC)") (class "Default")
      (node (ref "C1205") (pin "2") (pinfunction "2_2") (pintype "passive"))
      (node (ref "U1201") (pin "4") (pinfunction "VCC_4") (pintype "passive"))
    )
    (net (code "87") (name "Net-(U1301-LBI)") (class "Default")
      (node (ref "R1301") (pin "2") (pinfunction "2_2") (pintype "passive"))
      (node (ref "R1302") (pin "1") (pinfunction "1_1") (pintype "passive"))
      (node (ref "U1301") (pin "6") (pinfunction "LBI_6") (pintype "input"))
    )
    (net (code "88") (name "Net-(U1301-SW)") (class "Default")
      (node (ref "L1311") (pin "2") (pinfunction "2_2") (pintype "passive"))
      (node (ref "L1311") (pin "4") (pinfunction "2_4") (pintype "passive"))
      (node (ref "U1301") (pin "9") (pinfunction "SW_9") (pintype "passive"))
    )
    (net (code "89") (name "PA0") (class "Default")
      (node (ref "R1101") (pin "1") (pinfunction "1_1") (pintype "passive"))
      (node (ref "U0101") (pin "14") (pinfunction "PA0_WKUP_14") (pintype "bidirectional"))
    )
    (net (code "90") (name "PA1") (class "Default")
      (node (ref "R1102") (pin "1") (pinfunction "1_1") (pintype "passive"))
      (node (ref "U0101") (pin "15") (pinfunction "PA1_15") (pintype "bidirectional"))
    )
    (net (code "91") (name "PA3") (class "Default")
      (node (ref "R0922") (pin "1") (pinfunction "1_1") (pintype "passive"))
      (node (ref "U0101") (pin "17") (pinfunction "PA3_17") (pintype "bidirectional"))
    )
    (net (code "92") (name "PA5") (class "Default")
      (node (ref "R0621") (pin "1") (pinfunction "1_1") (pintype "passive"))
      (node (ref "U0101") (pin "21") (pinfunction "PA5_21") (pintype "bidirectional"))
    )
    (net (code "93") (name "PA6") (class "Default")
      (node (ref "R0622") (pin "1") (pinfunction "1_1") (pintype "passive"))
      (node (ref "U0101") (pin "22") (pinfunction "PA6_22") (pintype "bidirectional"))
    )
    (net (code "94") (name "PA7") (class "Default")
      (node (ref "R0623") (pin "1") (pinfunction "1_1") (pintype "passive"))
      (node (ref "U0101") (pin "23") (pinfunction "PA7_23") (pintype "bidirectional"))
    )
    (net (code "95") (name "PA9") (class "Default")
      (node (ref "PF1411") (pin "1") (pinfunction "1_1") (pintype "passive"))
      (node (ref "U0101") (pin "42") (pinfunction "PA9_42") (pintype "bidirectional"))
      (node (ref "X1401") (pin "VBUS") (pinfunction "J_VUSB_VBUS") (pintype "power_in"))
    )
    (net (code "96") (name "PA10") (class "Default")
      (node (ref "U0101") (pin "43") (pinfunction "PA10_43") (pintype "bidirectional"))
      (node (ref "X1401") (pin "ID") (pinfunction "J_ID_ID") (pintype "bidirectional"))
    )
    (net (code "97") (name "PA11") (class "Default")
      (node (ref "U0101") (pin "44") (pinfunction "PA11_44") (pintype "bidirectional"))
      (node (ref "X1401") (pin "D-") (pinfunction "J_D-_D-") (pintype "bidirectional"))
    )
    (net (code "98") (name "PA12") (class "Default")
      (node (ref "U0101") (pin "45") (pinfunction "PA12_45") (pintype "bidirectional"))
      (node (ref "X1401") (pin "D+") (pinfunction "J_D+_D+") (pintype "bidirectional"))
    )
    (net (code "99") (name "PA13") (class "Default")
      (node (ref "R0231") (pin "1") (pinfunction "1_1") (pintype "passive"))
      (node (ref "U0101") (pin "46") (pinfunction "PA13_JTMS_SWDIO_46") (pintype "bidirectional"))
      (node (ref "X0201") (pin "2") (pinfunction "2_2") (pintype "passive"))
    )
    (net (code "100") (name "PA14") (class "Default")
      (node (ref "R0232") (pin "2") (pinfunction "2_2") (pintype "passive"))
      (node (ref "U0101") (pin "49") (pinfunction "PA14_JTCK_SWCLK_49") (pintype "bidirectional"))
      (node (ref "X0201") (pin "4") (pinfunction "4_4") (pintype "passive"))
    )
    (net (code "101") (name "PA15") (class "Default")
      (node (ref "R1103") (pin "1") (pinfunction "1_1") (pintype "passive"))
      (node (ref "U0101") (pin "50") (pinfunction "PA15_JTDI_50") (pintype "bidirectional"))
    )
    (net (code "102") (name "PB0") (class "Default")
      (node (ref "R0624") (pin "1") (pinfunction "1_1") (pintype "passive"))
      (node (ref "U0101") (pin "26") (pinfunction "PB0_26") (pintype "bidirectional"))
    )
    (net (code "103") (name "PB1") (class "Default")
      (node (ref "R0724") (pin "1") (pinfunction "1_1") (pintype "passive"))
      (node (ref "U0101") (pin "27") (pinfunction "PB1_27") (pintype "bidirectional"))
    )
    (net (code "104") (name "PB2") (class "Default")
      (node (ref "R0824") (pin "1") (pinfunction "1_1") (pintype "passive"))
      (node (ref "U0101") (pin "28") (pinfunction "PB2_28") (pintype "bidirectional"))
    )
    (net (code "105") (name "PB6") (class "Default")
      (node (ref "R0512") (pin "1") (pinfunction "1_1") (pintype "passive"))
      (node (ref "U0101") (pin "58") (pinfunction "PB6_58") (pintype "bidirectional"))
      (node (ref "X0601") (pin "1") (pinfunction "1_1") (pintype "passive"))
    )
    (net (code "106") (name "PB7") (class "Default")
      (node (ref "R1104") (pin "1") (pinfunction "1_1") (pintype "passive"))
      (node (ref "U0101") (pin "59") (pinfunction "PB7_59") (pintype "bidirectional"))
    )
    (net (code "107") (name "PB9") (class "Default")
      (node (ref "R0511") (pin "1") (pinfunction "1_1") (pintype "passive"))
      (node (ref "U0101") (pin "62") (pinfunction "PB9_62") (pintype "bidirectional"))
      (node (ref "X0601") (pin "3") (pinfunction "3_3") (pintype "passive"))
    )
    (net (code "108") (name "PB10") (class "Default")
      (node (ref "R1002") (pin "1") (pinfunction "1_1") (pintype "passive"))
      (node (ref "U0101") (pin "29") (pinfunction "PB10_29") (pintype "bidirectional"))
    )
    (net (code "109") (name "PB11") (class "Default")
      (node (ref "R0626") (pin "1") (pinfunction "1_1") (pintype "passive"))
      (node (ref "U0101") (pin "30") (pinfunction "PB11_30") (pintype "bidirectional"))
    )
    (net (code "110") (name "PB12") (class "Default")
      (node (ref "R1003") (pin "1") (pinfunction "1_1") (pintype "passive"))
      (node (ref "U0101") (pin "33") (pinfunction "PB12_33") (pintype "bidirectional"))
    )
    (net (code "111") (name "PB13") (class "Default")
      (node (ref "R1004") (pin "1") (pinfunction "1_1") (pintype "passive"))
      (node (ref "U0101") (pin "34") (pinfunction "PB13_34") (pintype "bidirectional"))
    )
    (net (code "112") (name "PC0") (class "Default")
      (node (ref "R0952") (pin "2") (pinfunction "2_2") (pintype "passive"))
      (node (ref "U0101") (pin "8") (pinfunction "PC0_8") (pintype "bidirectional"))
    )
    (net (code "113") (name "PC1") (class "Default")
      (node (ref "R1001") (pin "1") (pinfunction "1_1") (pintype "passive"))
      (node (ref "U0101") (pin "9") (pinfunction "PC1_9") (pintype "bidirectional"))
    )
    (net (code "114") (name "PC2") (class "Default")
      (node (ref "D0961") (pin "A") (pinfunction "A_A") (pintype "passive"))
      (node (ref "R0961") (pin "2") (pinfunction "2_2") (pintype "passive"))
      (node (ref "U0101") (pin "10") (pinfunction "PC2_10") (pintype "bidirectional"))
    )
    (net (code "115") (name "PC3") (class "Default")
      (node (ref "R0921") (pin "1") (pinfunction "1_1") (pintype "passive"))
      (node (ref "U0101") (pin "11") (pinfunction "PC3_11") (pintype "bidirectional"))
    )
    (net (code "116") (name "PC4") (class "Default")
      (node (ref "R0625") (pin "1") (pinfunction "1_1") (pintype "passive"))
      (node (ref "U0101") (pin "24") (pinfunction "PC4_24") (pintype "bidirectional"))
    )
    (net (code "117") (name "PC14_OSC32_IN") (class "Default")
      (node (ref "C0331") (pin "-") (pinfunction "E_-") (pintype "passive"))
      (node (ref "C0332") (pin "1") (pinfunction "1_1") (pintype "passive"))
      (node (ref "Q0321") (pin "2") (pinfunction "2_2") (pintype "passive"))
      (node (ref "U0101") (pin "3") (pinfunction "PC14_OSC32_IN_3") (pintype "bidirectional"))
    )
    (net (code "118") (name "PC15_OSC32_OUT") (class "Default")
      (node (ref "C0311") (pin "1") (pinfunction "1_1") (pintype "passive"))
      (node (ref "Q0321") (pin "1") (pinfunction "1_1") (pintype "passive"))
      (node (ref "U0101") (pin "4") (pinfunction "PC15_OSC32_OUT_4") (pintype "bidirectional"))
    )
    (net (code "119") (name "PH0") (class "Default")
      (node (ref "U0101") (pin "5") (pinfunction "PH0_OSC_IN_5") (pintype "bidirectional"))
    )
    (net (code "120") (name "PH1") (class "Default")
      (node (ref "U0101") (pin "6") (pinfunction "PH1_OSC_OUT_6") (pintype "bidirectional"))
    )
    (net (code "121") (name "PH3_BOOT0") (class "Default")
      (node (ref "R0221") (pin "2") (pinfunction "2_2") (pintype "passive"))
      (node (ref "U0101") (pin "60") (pinfunction "BOOT0_60") (pintype "output"))
      (node (ref "X0222") (pin "2") (pinfunction "2_2") (pintype "passive"))
    )
    (net (code "122") (name "RELAY1") (class "Default")
      (node (ref "U0601") (pin "1") (pinfunction "OUT0_1") (pintype "passive"))
      (node (ref "X1601") (pin "1") (pinfunction "1_1") (pintype "passive"))
    )
    (net (code "123") (name "RELAY2") (class "Default")
      (node (ref "U0601") (pin "2") (pinfunction "OUT1_2") (pintype "passive"))
      (node (ref "X1601") (pin "2") (pinfunction "2_2") (pintype "passive"))
    )
    (net (code "124") (name "RELAY3") (class "Default")
      (node (ref "U0601") (pin "4") (pinfunction "OUT2_4") (pintype "passive"))
      (node (ref "X1601") (pin "3") (pinfunction "3_3") (pintype "passive"))
    )
    (net (code "125") (name "RELAY4") (class "Default")
      (node (ref "U0601") (pin "5") (pinfunction "OUT3_5") (pintype "passive"))
      (node (ref "X1601") (pin "4") (pinfunction "4_4") (pintype "passive"))
    )
    (net (code "126") (name "RELAY5") (class "Default")
      (node (ref "U0601") (pin "12") (pinfunction "OUT4_12") (pintype "passive"))
      (node (ref "X1601") (pin "5") (pinfunction "5_5") (pintype "passive"))
    )
    (net (code "127") (name "RELAY6") (class "Default")
      (node (ref "U0601") (pin "13") (pinfunction "OUT5_13") (pintype "passive"))
      (node (ref "X1601") (pin "6") (pinfunction "6_6") (pintype "passive"))
    )
    (net (code "128") (name "RELAY7") (class "Default")
      (node (ref "U0601") (pin "15") (pinfunction "OUT6_15") (pintype "passive"))
      (node (ref "X1601") (pin "7") (pinfunction "7_7") (pintype "passive"))
    )
    (net (code "129") (name "RELAY8") (class "Default")
      (node (ref "U0601") (pin "16") (pinfunction "OUT7_16") (pintype "passive"))
      (node (ref "X1601") (pin "8") (pinfunction "8_8") (pintype "passive"))
    )
    (net (code "130") (name "RELAY9") (class "Default")
      (node (ref "U0601") (pin "17") (pinfunction "OUT8_17") (pintype "passive"))
      (node (ref "X1601") (pin "9") (pinfunction "9_9") (pintype "passive"))
    )
    (net (code "131") (name "RELAY10") (class "Default")
      (node (ref "U0601") (pin "18") (pinfunction "OUT9_18") (pintype "passive"))
      (node (ref "X1601") (pin "10") (pinfunction "10_10") (pintype "passive"))
    )
    (net (code "132") (name "RELAY11") (class "Default")
      (node (ref "U0601") (pin "20") (pinfunction "OUT10_20") (pintype "passive"))
      (node (ref "X1601") (pin "11") (pinfunction "11_11") (pintype "passive"))
    )
    (net (code "133") (name "RELAY12") (class "Default")
      (node (ref "U0601") (pin "21") (pinfunction "OUT11_21") (pintype "passive"))
      (node (ref "X1601") (pin "12") (pinfunction "12_12") (pintype "passive"))
    )
    (net (code "134") (name "RELAY13") (class "Default")
      (node (ref "U0601") (pin "28") (pinfunction "OUT12_28") (pintype "passive"))
      (node (ref "X1601") (pin "13") (pinfunction "13_13") (pintype "passive"))
    )
    (net (code "135") (name "RELAY14") (class "Default")
      (node (ref "U0601") (pin "29") (pinfunction "OUT13_29") (pintype "passive"))
      (node (ref "X1601") (pin "14") (pinfunction "14_14") (pintype "passive"))
    )
    (net (code "136") (name "RELAY15") (class "Default")
      (node (ref "U0601") (pin "31") (pinfunction "OUT14_31") (pintype "passive"))
      (node (ref "X1601") (pin "15") (pinfunction "15_15") (pintype "passive"))
    )
    (net (code "137") (name "RELAY16") (class "Default")
      (node (ref "U0601") (pin "32") (pinfunction "OUT15_32") (pintype "passive"))
      (node (ref "X1601") (pin "16") (pinfunction "16_16") (pintype "passive"))
    )
    (net (code "138") (name "RELAY17") (class "Default")
      (node (ref "U0701") (pin "1") (pinfunction "OUT0_1") (pintype "passive"))
      (node (ref "X1601") (pin "17") (pinfunction "17_17") (pintype "passive"))
    )
    (net (code "139") (name "RELAY18") (class "Default")
      (node (ref "U0701") (pin "2") (pinfunction "OUT1_2") (pintype "passive"))
      (node (ref "X1601") (pin "18") (pinfunction "18_18") (pintype "passive"))
    )
    (net (code "140") (name "RELAY19") (class "Default")
      (node (ref "U0701") (pin "4") (pinfunction "OUT2_4") (pintype "passive"))
      (node (ref "X1601") (pin "19") (pinfunction "19_19") (pintype "passive"))
    )
    (net (code "141") (name "RELAY20") (class "Default")
      (node (ref "U0701") (pin "5") (pinfunction "OUT3_5") (pintype "passive"))
      (node (ref "X1601") (pin "20") (pinfunction "20_20") (pintype "passive"))
    )
    (net (code "142") (name "RELAY21") (class "Default")
      (node (ref "U0701") (pin "12") (pinfunction "OUT4_12") (pintype "passive"))
      (node (ref "X1602") (pin "1") (pinfunction "1_1") (pintype "passive"))
    )
    (net (code "143") (name "RELAY22") (class "Default")
      (node (ref "U0701") (pin "13") (pinfunction "OUT5_13") (pintype "passive"))
      (node (ref "X1602") (pin "2") (pinfunction "2_2") (pintype "passive"))
    )
    (net (code "144") (name "RELAY23") (class "Default")
      (node (ref "U0701") (pin "15") (pinfunction "OUT6_15") (pintype "passive"))
      (node (ref "X1602") (pin "3") (pinfunction "3_3") (pintype "passive"))
    )
    (net (code "145") (name "RELAY24") (class "Default")
      (node (ref "U0701") (pin "16") (pinfunction "OUT7_16") (pintype "passive"))
      (node (ref "X1602") (pin "4") (pinfunction "4_4") (pintype "passive"))
    )
    (net (code "146") (name "RELAY25") (class "Default")
      (node (ref "U0701") (pin "17") (pinfunction "OUT8_17") (pintype "passive"))
      (node (ref "X1602") (pin "5") (pinfunction "5_5") (pintype "passive"))
    )
    (net (code "147") (name "RELAY26") (class "Default")
      (node (ref "U0701") (pin "18") (pinfunction "OUT9_18") (pintype "passive"))
      (node (ref "X1602") (pin "6") (pinfunction "6_6") (pintype "passive"))
    )
    (net (code "148") (name "RELAY27") (class "Default")
      (node (ref "U0701") (pin "20") (pinfunction "OUT10_20") (pintype "passive"))
      (node (ref "X1602") (pin "7") (pinfunction "7_7") (pintype "passive"))
    )
    (net (code "149") (name "RELAY28") (class "Default")
      (node (ref "U0701") (pin "21") (pinfunction "OUT11_21") (pintype "passive"))
      (node (ref "X1602") (pin "8") (pinfunction "8_8") (pintype "passive"))
    )
    (net (code "150") (name "RELAY29") (class "Default")
      (node (ref "U0701") (pin "28") (pinfunction "OUT12_28") (pintype "passive"))
      (node (ref "X1602") (pin "9") (pinfunction "9_9") (pintype "passive"))
    )
    (net (code "151") (name "RELAY30") (class "Default")
      (node (ref "U0701") (pin "29") (pinfunction "OUT13_29") (pintype "passive"))
      (node (ref "X1602") (pin "10") (pinfunction "10_10") (pintype "passive"))
    )
    (net (code "152") (name "RELAY31") (class "Default")
      (node (ref "U0701") (pin "31") (pinfunction "OUT14_31") (pintype "passive"))
      (node (ref "X1602") (pin "11") (pinfunction "11_11") (pintype "passive"))
    )
    (net (code "153") (name "RELAY32") (class "Default")
      (node (ref "U0701") (pin "32") (pinfunction "OUT15_32") (pintype "passive"))
      (node (ref "X1602") (pin "12") (pinfunction "12_12") (pintype "passive"))
    )
    (net (code "154") (name "RELAY33") (class "Default")
      (node (ref "U0801") (pin "1") (pinfunction "OUT0_1") (pintype "passive"))
      (node (ref "X1602") (pin "13") (pinfunction "13_13") (pintype "passive"))
    )
    (net (code "155") (name "RELAY34") (class "Default")
      (node (ref "U0801") (pin "2") (pinfunction "OUT1_2") (pintype "passive"))
      (node (ref "X1602") (pin "14") (pinfunction "14_14") (pintype "passive"))
    )
    (net (code "156") (name "RELAY35") (class "Default")
      (node (ref "U0801") (pin "4") (pinfunction "OUT2_4") (pintype "passive"))
      (node (ref "X1602") (pin "15") (pinfunction "15_15") (pintype "passive"))
    )
    (net (code "157") (name "RELAY36") (class "Default")
      (node (ref "U0801") (pin "5") (pinfunction "OUT3_5") (pintype "passive"))
      (node (ref "X1602") (pin "16") (pinfunction "16_16") (pintype "passive"))
    )
    (net (code "158") (name "RM_FWD") (class "Default")
      (node (ref "L0901") (pin "2") (pinfunction "2_2") (pintype "passive"))
      (node (ref "X1501") (pin "1") (pinfunction "1_1") (pintype "passive"))
    )
    (net (code "159") (name "RM_REV") (class "Default")
      (node (ref "L0911") (pin "2") (pinfunction "2_2") (pintype "passive"))
      (node (ref "X1511") (pin "1") (pinfunction "1_1") (pintype "passive"))
    )
    (net (code "160") (name "RS_DTE_CTS") (class "Default")
      (node (ref "C1053") (pin "1") (pinfunction "1_1") (pintype "passive"))
      (node (ref "U1001") (pin "7") (pinfunction "T2OUT_7") (pintype "output"))
      (node (ref "X1053") (pin "1") (pinfunction "1_1") (pintype "passive"))
    )
    (net (code "161") (name "RS_DTE_RTR") (class "Default")
      (node (ref "C0054") (pin "1") (pinfunction "1_1") (pintype "passive"))
      (node (ref "U1001") (pin "8") (pinfunction "R2IN_8") (pintype "input"))
      (node (ref "X1053") (pin "2") (pinfunction "2_2") (pintype "passive"))
    )
    (net (code "162") (name "RS_DTE_RXD") (class "Default")
      (node (ref "C1051") (pin "1") (pinfunction "1_1") (pintype "passive"))
      (node (ref "U1001") (pin "14") (pinfunction "T1OUT_14") (pintype "output"))
      (node (ref "X1051") (pin "1") (pinfunction "1_1") (pintype "passive"))
    )
    (net (code "163") (name "RS_DTE_TXD") (class "Default")
      (node (ref "C1052") (pin "1") (pinfunction "1_1") (pintype "passive"))
      (node (ref "U1001") (pin "13") (pinfunction "R1IN_13") (pintype "input"))
      (node (ref "X1051") (pin "2") (pinfunction "2_2") (pintype "passive"))
    )
    (net (code "164") (name "RS_MX_C1P") (class "Default")
      (node (ref "C1002") (pin "1") (pinfunction "1_1") (pintype "passive"))
      (node (ref "U1001") (pin "1") (pinfunction "C1+_1") (pintype "bidirectional"))
    )
    (net (code "165") (name "RS_MX_C2P") (class "Default")
      (node (ref "C1003") (pin "1") (pinfunction "1_1") (pintype "passive"))
      (node (ref "U1001") (pin "4") (pinfunction "C2+_4") (pintype "bidirectional"))
    )
    (net (code "166") (name "RS_MX_VM") (class "Default")
      (node (ref "C1005") (pin "1") (pinfunction "1_1") (pintype "passive"))
      (node (ref "U1001") (pin "6") (pinfunction "V-_6") (pintype "bidirectional"))
    )
    (net (code "167") (name "RS_MX_VP") (class "Default")
      (node (ref "C1004") (pin "1") (pinfunction "1_1") (pintype "passive"))
      (node (ref "U1001") (pin "2") (pinfunction "V+_2") (pintype "bidirectional"))
    )
    (net (code "168") (name "SPI_DRV_C_~{CS}") (class "Default")
      (node (ref "R0724") (pin "2") (pinfunction "2_2") (pintype "passive"))
      (node (ref "U0701") (pin "14") (pinfunction "~{CS}_14") (pintype "input"))
    )
    (net (code "169") (name "SPI_DRV_EXT_~{CS}") (class "Default")
      (node (ref "R0824") (pin "2") (pinfunction "2_2") (pintype "passive"))
      (node (ref "U0801") (pin "14") (pinfunction "~{CS}_14") (pintype "input"))
    )
    (net (code "170") (name "SPI_DRV_L_~{CS}") (class "Default")
      (node (ref "R0624") (pin "2") (pinfunction "2_2") (pintype "passive"))
      (node (ref "U0601") (pin "14") (pinfunction "~{CS}_14") (pintype "input"))
    )
    (net (code "171") (name "SPI_DRV_PWM") (class "Default")
      (node (ref "R0626") (pin "2") (pinfunction "2_2") (pintype "passive"))
      (node (ref "U0601") (pin "30") (pinfunction "PWM_30") (pintype "input"))
      (node (ref "U0701") (pin "30") (pinfunction "PWM_30") (pintype "input"))
      (node (ref "U0801") (pin "30") (pinfunction "PWM_30") (pintype "input"))
    )
    (net (code "172") (name "SPI_DRV_SCLK") (class "Default")
      (node (ref "R0621") (pin "2") (pinfunction "2_2") (pintype "passive"))
      (node (ref "U0601") (pin "11") (pinfunction "SCLK_11") (pintype "input"))
      (node (ref "U0701") (pin "11") (pinfunction "SCLK_11") (pintype "input"))
      (node (ref "U0801") (pin "11") (pinfunction "SCLK_11") (pintype "input"))
    )
    (net (code "173") (name "SPI_DRV_SI") (class "Default")
      (node (ref "R0623") (pin "2") (pinfunction "2_2") (pintype "passive"))
      (node (ref "U0601") (pin "19") (pinfunction "SI_19") (pintype "input"))
      (node (ref "U0701") (pin "19") (pinfunction "SI_19") (pintype "input"))
      (node (ref "U0801") (pin "19") (pinfunction "SI_19") (pintype "input"))
    )
    (net (code "174") (name "SPI_DRV_SO") (class "Default")
      (node (ref "R0611") (pin "1") (pinfunction "1_1") (pintype "passive"))
      (node (ref "R0622") (pin "2") (pinfunction "2_2") (pintype "passive"))
      (node (ref "R0711") (pin "1") (pinfunction "1_1") (pintype "passive"))
      (node (ref "R0811") (pin "1") (pinfunction "1_1") (pintype "passive"))
    )
    (net (code "175") (name "SPI_DRV_~{RST}") (class "Default")
      (node (ref "R0625") (pin "2") (pinfunction "2_2") (pintype "passive"))
      (node (ref "U0601") (pin "27") (pinfunction "~{RST}_27") (pintype "input"))
      (node (ref "U0701") (pin "27") (pinfunction "~{RST}_27") (pintype "input"))
      (node (ref "U0801") (pin "27") (pinfunction "~{RST}_27") (pintype "input"))
    )
    (net (code "176") (name "SWR_IN_FWD") (class "Default")
      (node (ref "D0901") (pin "A") (pinfunction "A_A") (pintype "passive"))
      (node (ref "R0902") (pin "2") (pinfunction "2_2") (pintype "passive"))
      (node (ref "R0903") (pin "1") (pinfunction "1_1") (pintype "passive"))
      (node (ref "U0921") (pin "1") (pinfunction "1_1") (pintype "passive"))
    )
    (net (code "177") (name "SWR_IN_FWD_HI") (class "Default")
      (node (ref "C0901") (pin "1") (pinfunction "1_1") (pintype "passive"))
      (node (ref "L0901") (pin "1") (pinfunction "1_1") (pintype "passive"))
      (node (ref "R0901") (pin "2") (pinfunction "2_2") (pintype "passive"))
      (node (ref "R0902") (pin "1") (pinfunction "1_1") (pintype "passive"))
    )
    (net (code "178") (name "SWR_IN_REV") (class "Default")
      (node (ref "D0911") (pin "A") (pinfunction "A_A") (pintype "passive"))
      (node (ref "R0912") (pin "2") (pinfunction "2_2") (pintype "passive"))
      (node (ref "R0913") (pin "1") (pinfunction "1_1") (pintype "passive"))
      (node (ref "U0921") (pin "5") (pinfunction "5_5") (pintype "passive"))
    )
    (net (code "179") (name "SWR_IN_REV_HI") (class "Default")
      (node (ref "C0911") (pin "1") (pinfunction "1_1") (pintype "passive"))
      (node (ref "L0911") (pin "1") (pinfunction "1_1") (pintype "passive"))
      (node (ref "R0911") (pin "2") (pinfunction "2_2") (pintype "passive"))
      (node (ref "R0912") (pin "1") (pinfunction "1_1") (pintype "passive"))
    )
    (net (code "180") (name "SWR_SEL_FWD") (class "Default")
      (node (ref "R0921") (pin "2") (pinfunction "2_2") (pintype "passive"))
      (node (ref "U0921") (pin "7") (pinfunction "7_7") (pintype "input"))
    )
    (net (code "181") (name "SWR_SEL_PWR") (class "Default")
      (node (ref "D0951") (pin "A") (pinfunction "A_A") (pintype "passive"))
      (node (ref "R0951") (pin "2") (pinfunction "2_2") (pintype "passive"))
      (node (ref "U0921") (pin "2") (pinfunction "2_2") (pintype "passive"))
      (node (ref "U0921") (pin "6") (pinfunction "6_6") (pintype "passive"))
      (node (ref "U0951") (pin "4") (pinfunction "-IN_4") (pintype "input"))
    )
    (net (code "182") (name "SWR_SEL_REV") (class "Default")
      (node (ref "R0922") (pin "2") (pinfunction "2_2") (pintype "passive"))
      (node (ref "U0921") (pin "3") (pinfunction "3_3") (pintype "input"))
    )
    (net (code "183") (name "TPS_LBO") (class "Default")
      (node (ref "R1322") (pin "1") (pinfunction "1_1") (pintype "passive"))
      (node (ref "U1301") (pin "2") (pinfunction "LBO_2") (pintype "output"))
    )
    (net (code "184") (name "TPS_PG") (class "Default")
      (node (ref "R1321") (pin "1") (pinfunction "1_1") (pintype "passive"))
      (node (ref "U1301") (pin "4") (pinfunction "PG_4") (pintype "output"))
    )
    (net (code "185") (name "VDDUSB") (class "Default")
      (node (ref "PF1411") (pin "2") (pinfunction "2_2") (pintype "passive"))
      (node (ref "U0101") (pin "48") (pinfunction "VDDUSB_48") (pintype "power_in"))
    )
    (net (code "186") (name "unconnected-(U0101-PA2_WKUP-Pad16)") (class "Default")
      (node (ref "U0101") (pin "16") (pinfunction "PA2_WKUP_16") (pintype "bidirectional"))
    )
    (net (code "187") (name "unconnected-(U0101-PA4-Pad20)") (class "Default")
      (node (ref "U0101") (pin "20") (pinfunction "PA4_20") (pintype "bidirectional"))
    )
    (net (code "188") (name "unconnected-(U0101-PA8-Pad41)") (class "Default")
      (node (ref "U0101") (pin "41") (pinfunction "PA8_41") (pintype "bidirectional"))
    )
    (net (code "189") (name "unconnected-(U0101-PB3_JTDO_TRACESWO-Pad55)") (class "Default")
      (node (ref "U0101") (pin "55") (pinfunction "PB3_JTDO_TRACESWO_55") (pintype "bidirectional"))
    )
    (net (code "190") (name "unconnected-(U0101-PB4_NJTRST-Pad56)") (class "Default")
      (node (ref "U0101") (pin "56") (pinfunction "PB4_NJTRST_56") (pintype "bidirectional"))
    )
    (net (code "191") (name "unconnected-(U0101-PB5-Pad57)") (class "Default")
      (node (ref "U0101") (pin "57") (pinfunction "PB5_57") (pintype "bidirectional"))
    )
    (net (code "192") (name "unconnected-(U0101-PB8-Pad61)") (class "Default")
      (node (ref "U0101") (pin "61") (pinfunction "PB8_61") (pintype "bidirectional"))
    )
    (net (code "193") (name "unconnected-(U0101-PB14-Pad35)") (class "Default")
      (node (ref "U0101") (pin "35") (pinfunction "PB14_35") (pintype "bidirectional"))
    )
    (net (code "194") (name "unconnected-(U0101-PB15-Pad36)") (class "Default")
      (node (ref "U0101") (pin "36") (pinfunction "PB15_36") (pintype "bidirectional"))
    )
    (net (code "195") (name "unconnected-(U0101-PC5_WKUP-Pad25)") (class "Default")
      (node (ref "U0101") (pin "25") (pinfunction "PC5_WKUP_25") (pintype "bidirectional"))
    )
    (net (code "196") (name "unconnected-(U0101-PC6-Pad37)") (class "Default")
      (node (ref "U0101") (pin "37") (pinfunction "PC6_37") (pintype "bidirectional"))
    )
    (net (code "197") (name "unconnected-(U0101-PC7-Pad38)") (class "Default")
      (node (ref "U0101") (pin "38") (pinfunction "PC7_38") (pintype "bidirectional"))
    )
    (net (code "198") (name "unconnected-(U0101-PC8-Pad39)") (class "Default")
      (node (ref "U0101") (pin "39") (pinfunction "PC8_39") (pintype "bidirectional"))
    )
    (net (code "199") (name "unconnected-(U0101-PC9-Pad40)") (class "Default")
      (node (ref "U0101") (pin "40") (pinfunction "PC9_40") (pintype "bidirectional"))
    )
    (net (code "200") (name "unconnected-(U0101-PC10-Pad51)") (class "Default")
      (node (ref "U0101") (pin "51") (pinfunction "PC10_51") (pintype "bidirectional"))
    )
    (net (code "201") (name "unconnected-(U0101-PC11-Pad52)") (class "Default")
      (node (ref "U0101") (pin "52") (pinfunction "PC11_52") (pintype "bidirectional"))
    )
    (net (code "202") (name "unconnected-(U0101-PC12-Pad53)") (class "Default")
      (node (ref "U0101") (pin "53") (pinfunction "PC12_53") (pintype "bidirectional"))
    )
    (net (code "203") (name "unconnected-(U0101-PC13_WKUP-Pad2)") (class "Default")
      (node (ref "U0101") (pin "2") (pinfunction "PC13_WKUP_2") (pintype "bidirectional"))
    )
    (net (code "204") (name "unconnected-(U0101-PD2-Pad54)") (class "Default")
      (node (ref "U0101") (pin "54") (pinfunction "PD2_54") (pintype "bidirectional"))
    )
    (net (code "205") (name "unconnected-(U1201-NC-Pad14)") (class "Default")
      (node (ref "U1201") (pin "14") (pinfunction "NC_14") (pintype "no_connect"))
    )
    (net (code "206") (name "unconnected-(U1201-~{RESET}-Pad8)") (class "Default")
      (node (ref "U1201") (pin "8") (pinfunction "~{RESET}_8") (pintype "output"))
    )
    (net (code "207") (name "unconnected-(X0201-Pad6)") (class "Default")
      (node (ref "X0201") (pin "6") (pinfunction "6_6") (pintype "passive"))
    )
    (net (code "208") (name "unconnected-(X0201-Pad7)") (class "Default")
      (node (ref "X0201") (pin "7") (pinfunction "7_7") (pintype "passive"))
    )
    (net (code "209") (name "unconnected-(X0201-Pad8)") (class "Default")
      (node (ref "X0201") (pin "8") (pinfunction "8_8") (pintype "passive"))
    )
  )
)
